# Digitalizador_RPi.net
KiCad netlist of a schematic drawn in Altium Designer
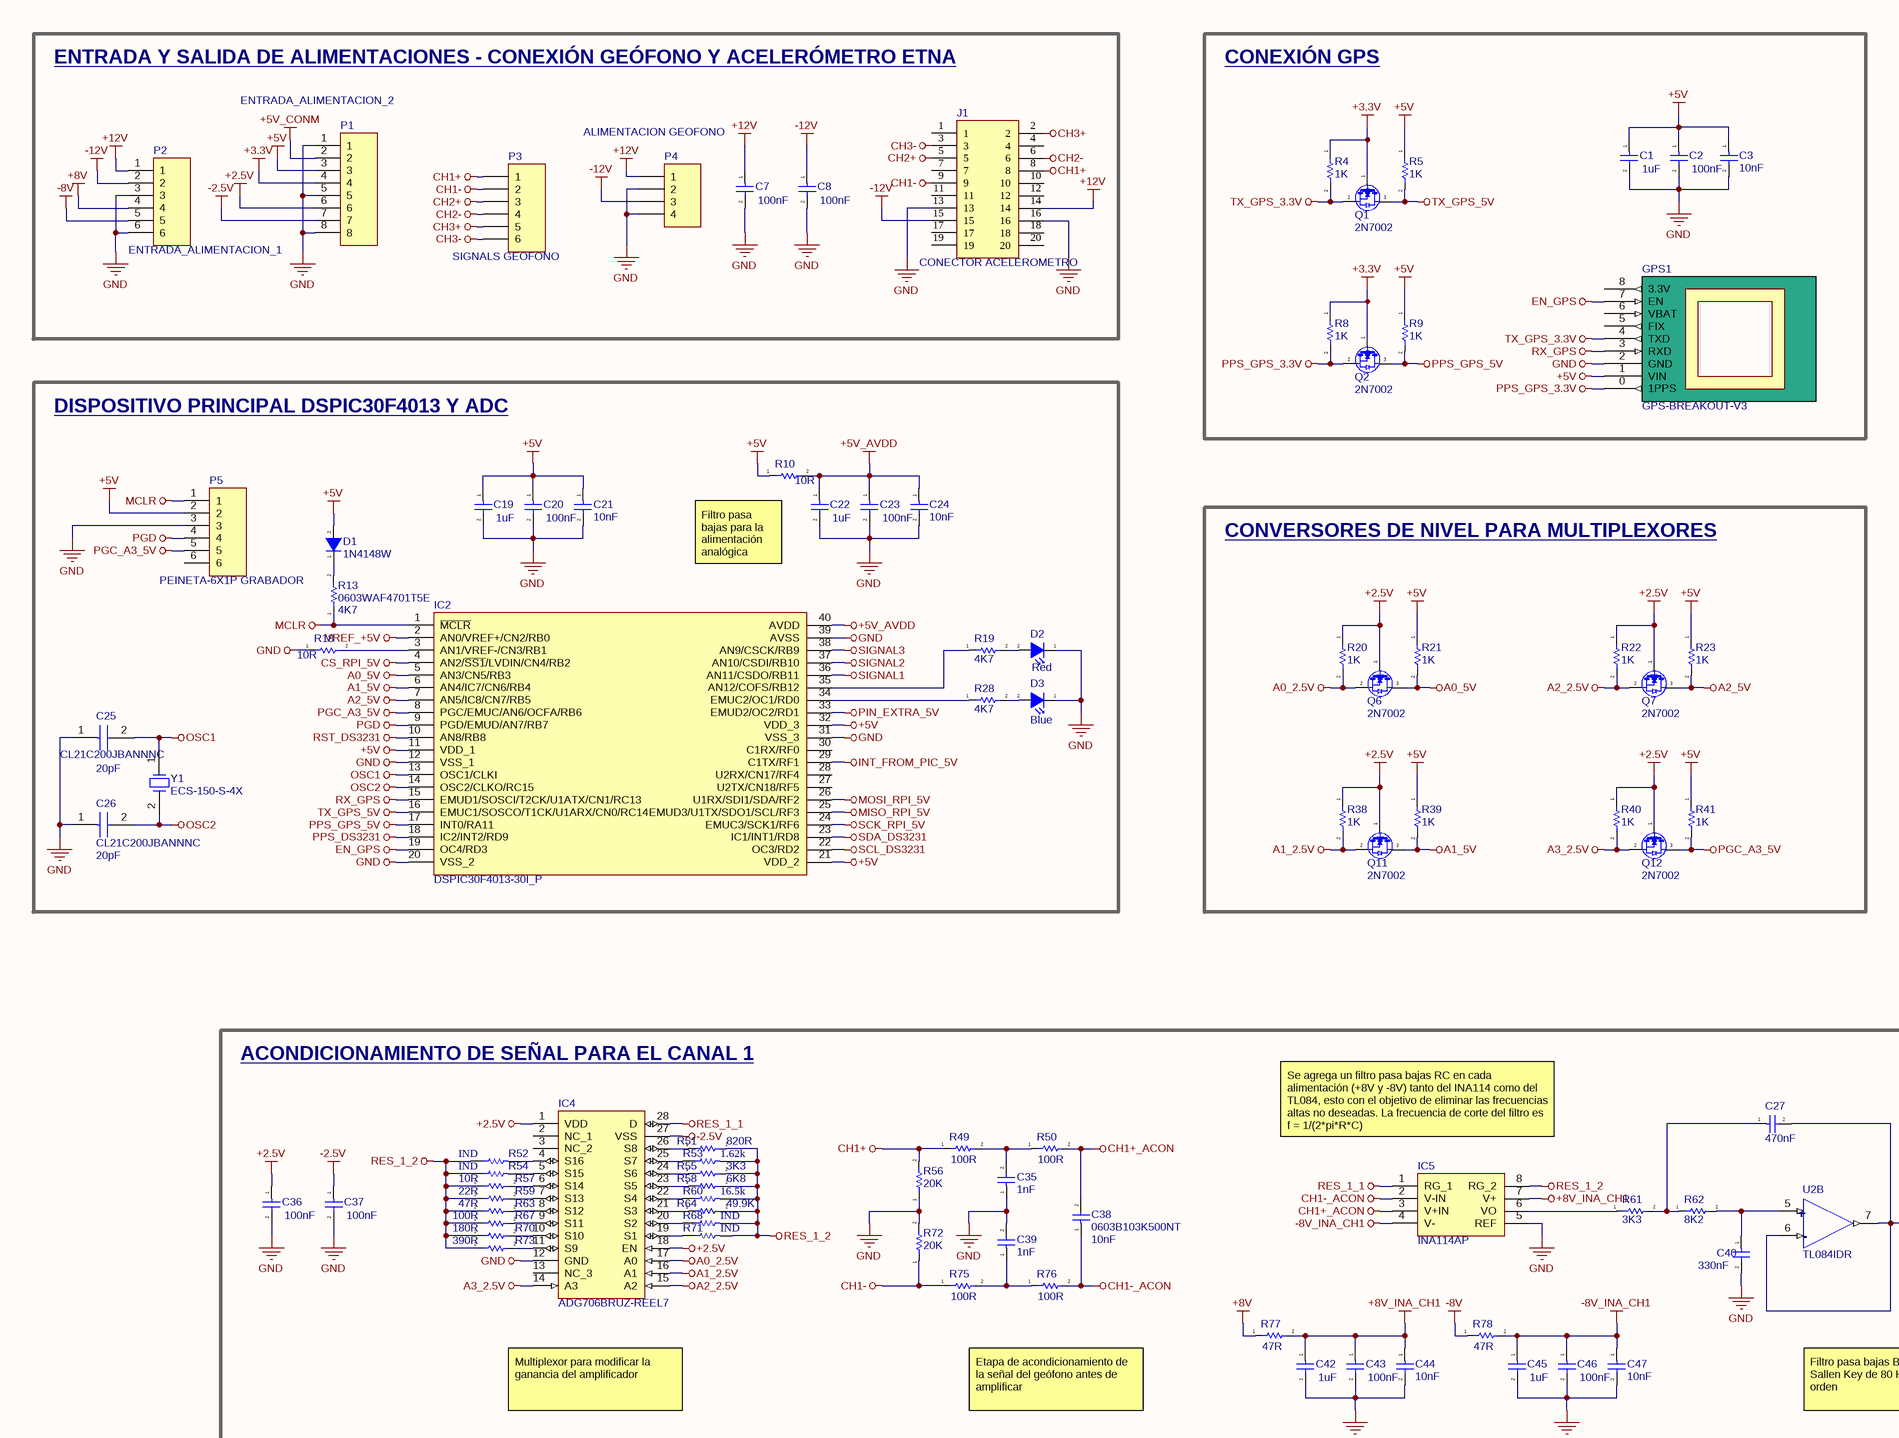
[diagram p0: Digitalizador_RPi.SchDoc, top left]
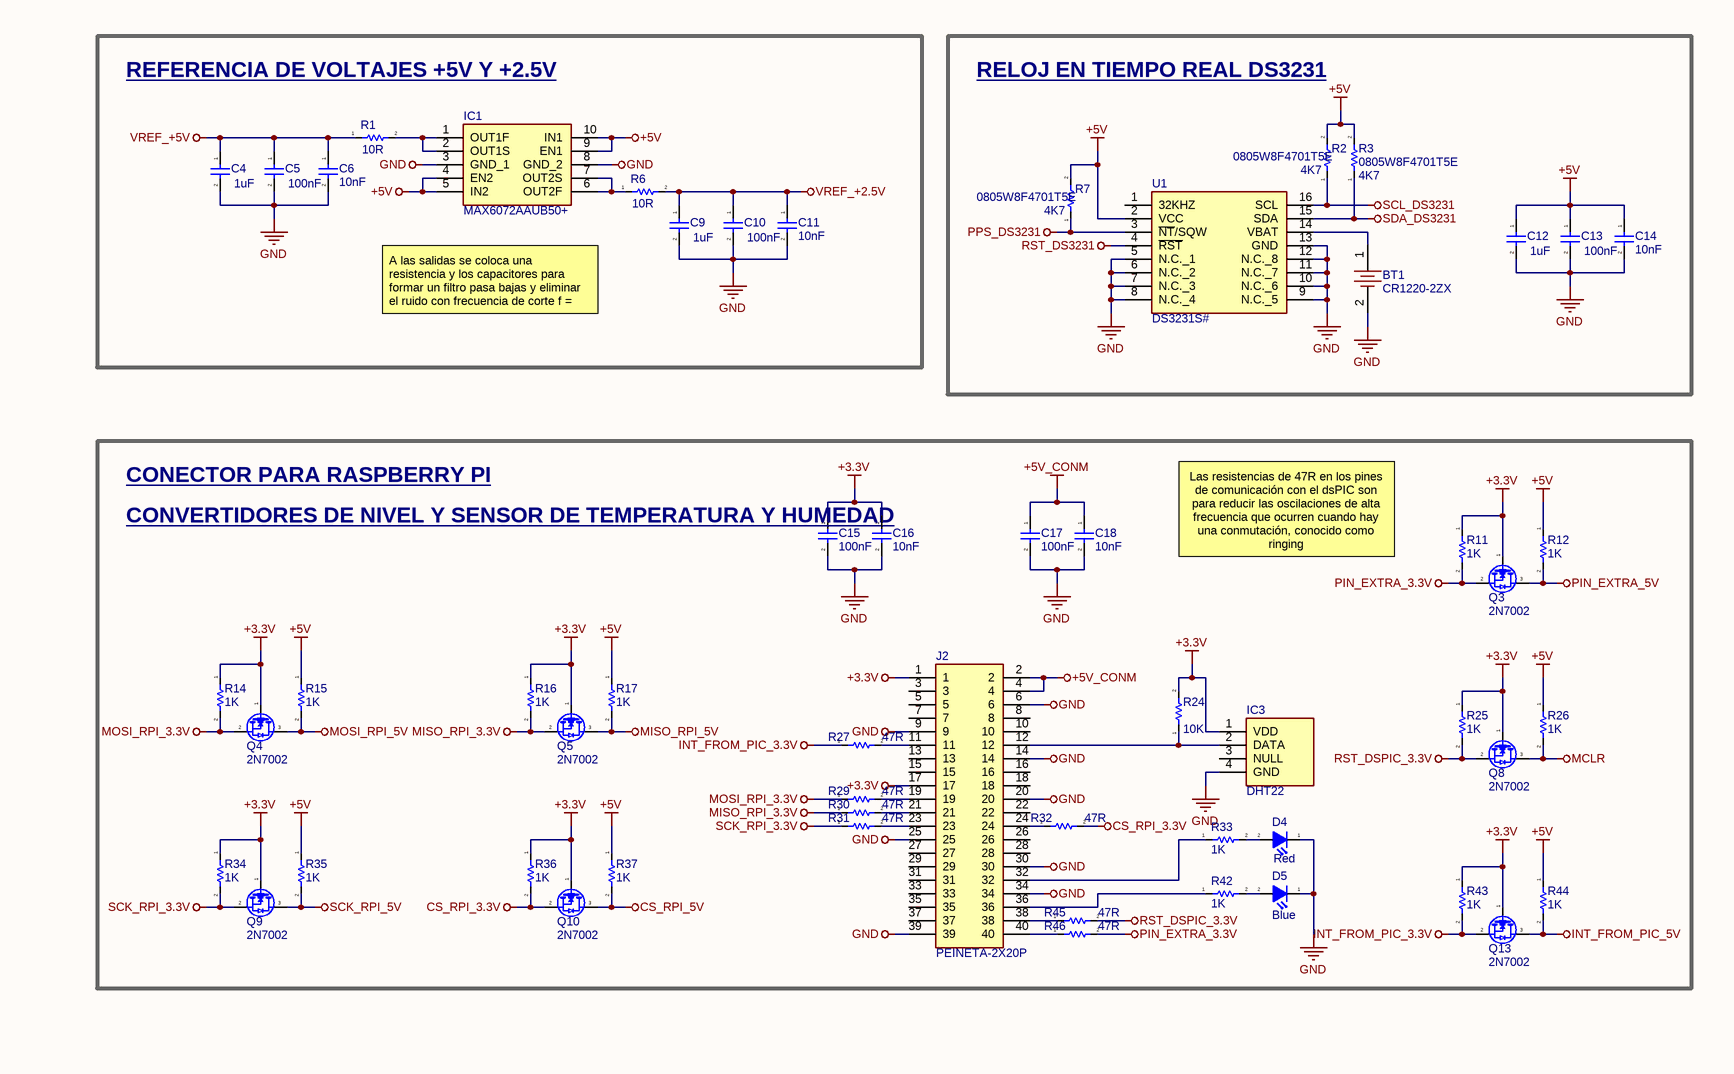
[diagram p1: Digitalizador_RPi.SchDoc, top right]
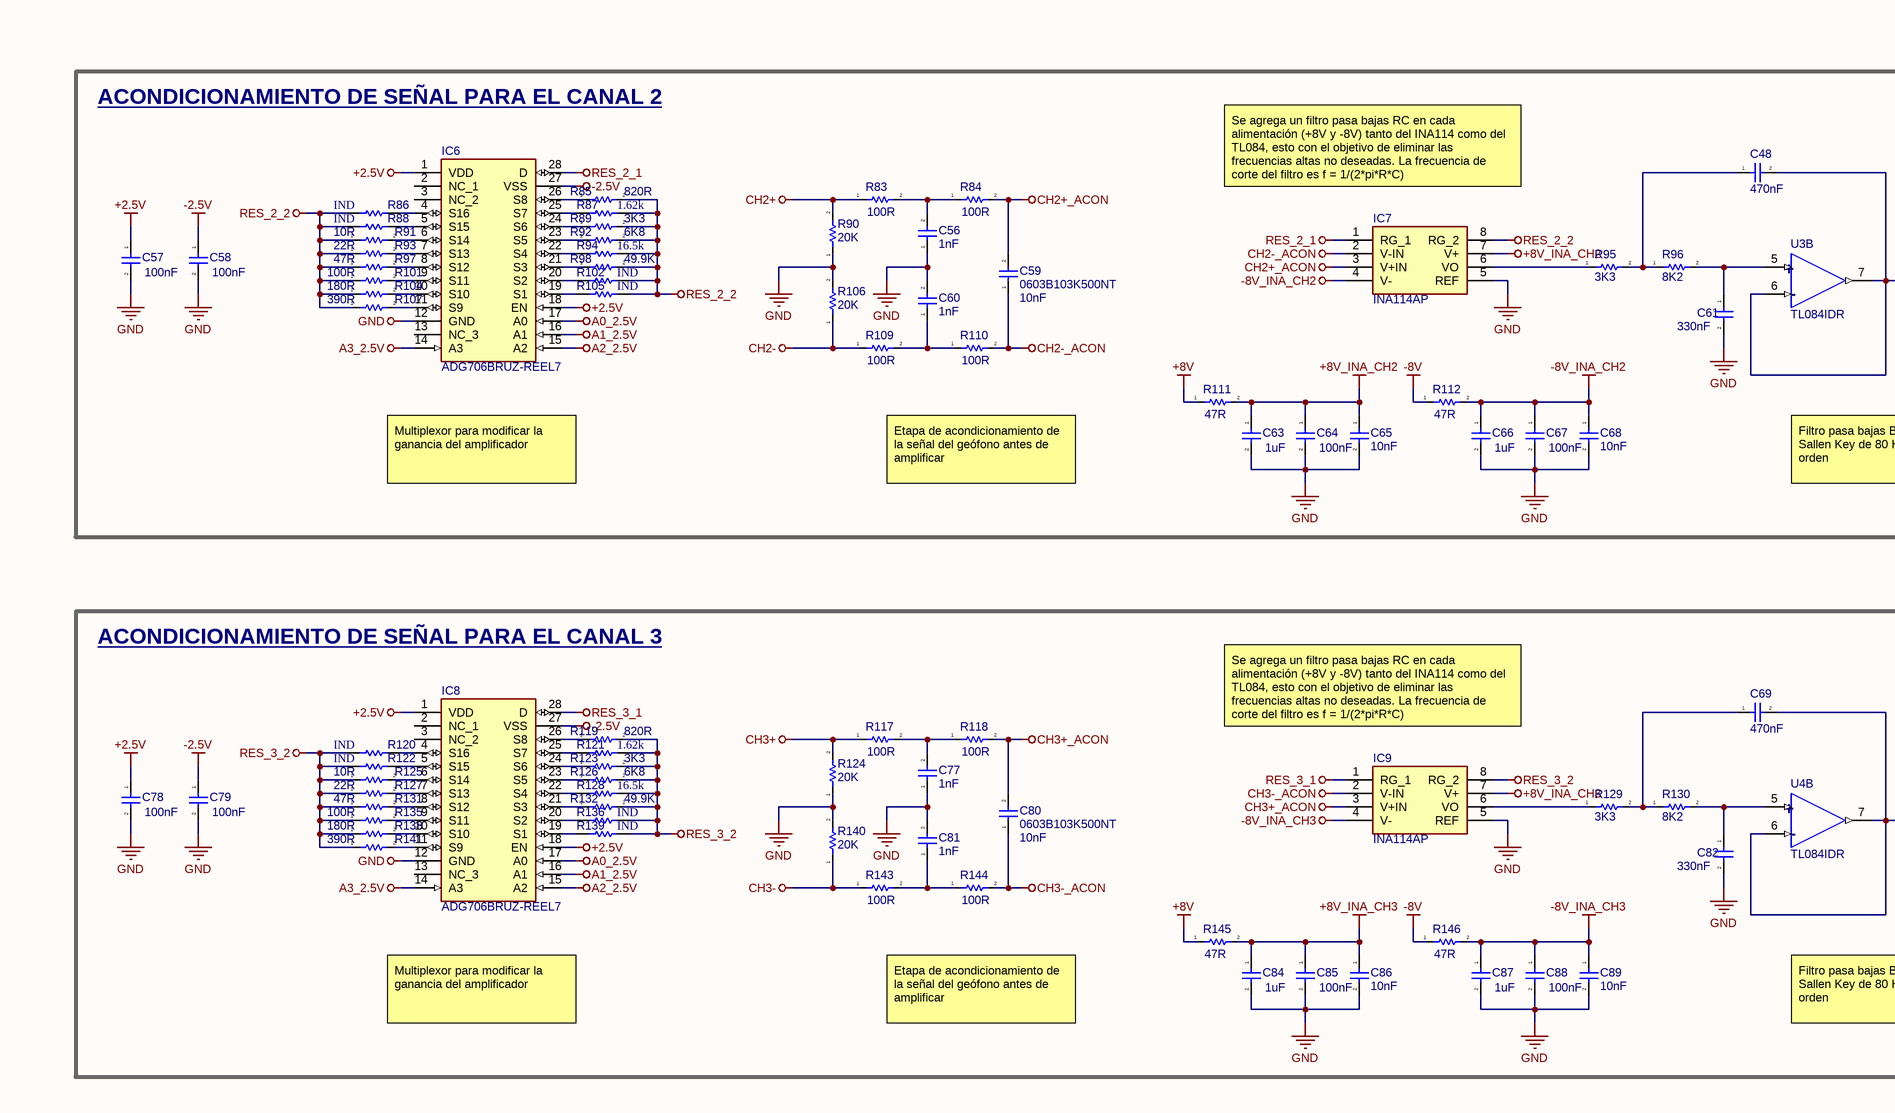
[diagram p2: Digitalizador_RPi.SchDoc, bottom left]
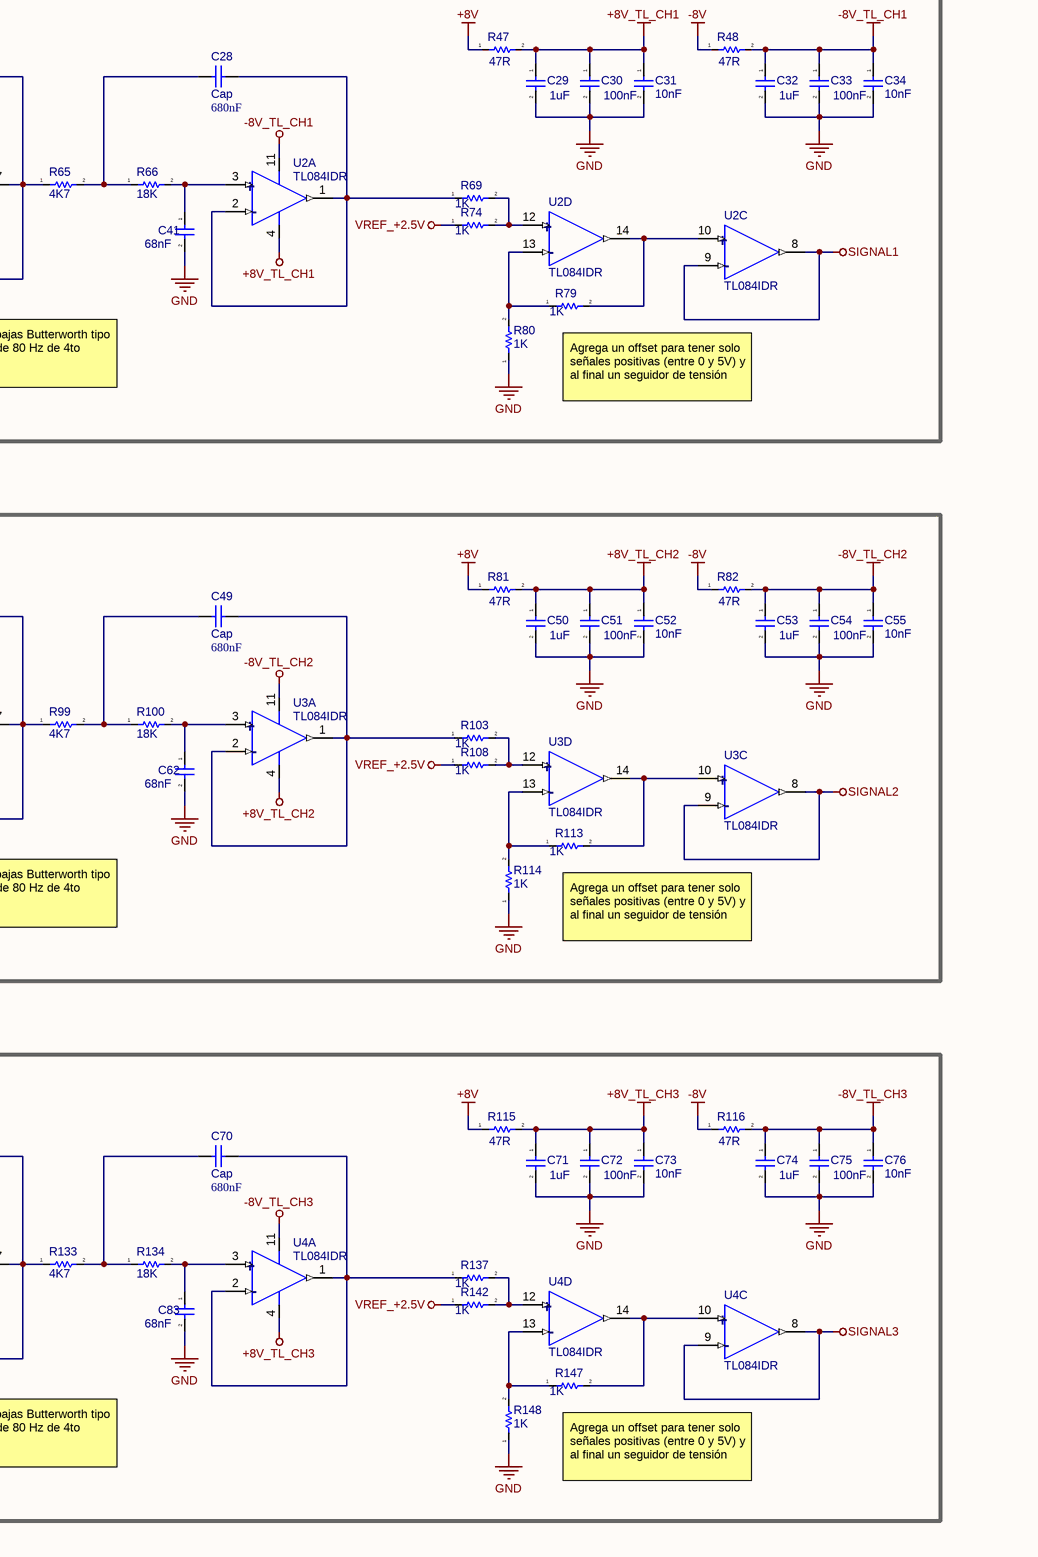
[diagram p3: Digitalizador_RPi.SchDoc, bottom right]

(export (version "E")
  (design (tool "Eeschema 10.0.6"))
  (components
    (comp (ref "BT1")
      (value "CR1220-2ZX")
      (footprint "CR12202ZX")
      (description "Battery Holder")
      (fields (field (name "JLCPCB PART #") "C969906"))
      (libsource (lib "AltiumLL") (part "CR1220-2ZX"))
    )
    (comp (ref "C1")
      (value "1uF")
      (footprint "CAPC1608X90N")
      (description "Capacitor")
      (fields
        (field (name "MANUFACTURER_PART_NUMBER") "CL10A105KB8NNNC")
        (field (name "MOUSER PART NUMBER") "187-CL10A105KB8NNNC")
      )
      (libsource (lib "AltiumLL") (part "CL10A105KB8NNNC"))
    )
    (comp (ref "C2")
      (value "100nF")
      (footprint "CAPC1608X90N")
      (description "Capacitor")
      (fields
        (field (name "MANUFACTURER_PART_NUMBER") "CC0603KRX7R9BB104")
        (field (name "MOUSER PART NUMBER") "603-CC603KRX7R9BB104")
      )
      (libsource (lib "AltiumLL") (part "CC0603KRX7R9BB104"))
    )
    (comp (ref "C3")
      (value "10nF")
      (footprint "CAPC1608X90N")
      (description "Capacitor")
      (fields
        (field (name "MANUFACTURER_PART_NUMBER") "0603B103K500NT")
        (field (name "JLCPCB PART #") "C57112")
      )
      (libsource (lib "AltiumLL") (part "0603B103K500NT"))
    )
    (comp (ref "C4")
      (value "1uF")
      (footprint "CAPC1608X90N")
      (description "Capacitor")
      (fields
        (field (name "MANUFACTURER_PART_NUMBER") "CL10A105KB8NNNC")
        (field (name "MOUSER PART NUMBER") "187-CL10A105KB8NNNC")
      )
      (libsource (lib "AltiumLL") (part "CL10A105KB8NNNC"))
    )
    (comp (ref "C5")
      (value "100nF")
      (footprint "CAPC1608X90N")
      (description "Capacitor")
      (fields
        (field (name "MANUFACTURER_PART_NUMBER") "CC0603KRX7R9BB104")
        (field (name "MOUSER PART NUMBER") "603-CC603KRX7R9BB104")
      )
      (libsource (lib "AltiumLL") (part "CC0603KRX7R9BB104"))
    )
    (comp (ref "C6")
      (value "10nF")
      (footprint "CAPC1608X90N")
      (description "Capacitor")
      (fields
        (field (name "MANUFACTURER_PART_NUMBER") "0603B103K500NT")
        (field (name "JLCPCB PART #") "C57112")
      )
      (libsource (lib "AltiumLL") (part "0603B103K500NT"))
    )
    (comp (ref "C7")
      (value "100nF")
      (footprint "CAPC1608X90N")
      (description "Capacitor")
      (fields
        (field (name "MANUFACTURER_PART_NUMBER") "CC0603KRX7R9BB104")
        (field (name "MOUSER PART NUMBER") "603-CC603KRX7R9BB104")
      )
      (libsource (lib "AltiumLL") (part "CC0603KRX7R9BB104"))
    )
    (comp (ref "C8")
      (value "100nF")
      (footprint "CAPC1608X90N")
      (description "Capacitor")
      (fields
        (field (name "MANUFACTURER_PART_NUMBER") "CC0603KRX7R9BB104")
        (field (name "MOUSER PART NUMBER") "603-CC603KRX7R9BB104")
      )
      (libsource (lib "AltiumLL") (part "CC0603KRX7R9BB104"))
    )
    (comp (ref "C9")
      (value "1uF")
      (footprint "CAPC1608X90N")
      (description "Capacitor")
      (fields
        (field (name "MANUFACTURER_PART_NUMBER") "CL10A105KB8NNNC")
        (field (name "MOUSER PART NUMBER") "187-CL10A105KB8NNNC")
      )
      (libsource (lib "AltiumLL") (part "CL10A105KB8NNNC"))
    )
    (comp (ref "C10")
      (value "100nF")
      (footprint "CAPC1608X90N")
      (description "Capacitor")
      (fields
        (field (name "MANUFACTURER_PART_NUMBER") "CC0603KRX7R9BB104")
        (field (name "MOUSER PART NUMBER") "603-CC603KRX7R9BB104")
      )
      (libsource (lib "AltiumLL") (part "CC0603KRX7R9BB104"))
    )
    (comp (ref "C11")
      (value "10nF")
      (footprint "CAPC1608X90N")
      (description "Capacitor")
      (fields
        (field (name "MANUFACTURER_PART_NUMBER") "0603B103K500NT")
        (field (name "JLCPCB PART #") "C57112")
      )
      (libsource (lib "AltiumLL") (part "0603B103K500NT"))
    )
    (comp (ref "C12")
      (value "1uF")
      (footprint "CAPC1608X90N")
      (description "Capacitor")
      (fields
        (field (name "MANUFACTURER_PART_NUMBER") "CL10A105KB8NNNC")
        (field (name "MOUSER PART NUMBER") "187-CL10A105KB8NNNC")
      )
      (libsource (lib "AltiumLL") (part "CL10A105KB8NNNC"))
    )
    (comp (ref "C13")
      (value "100nF")
      (footprint "CAPC1608X90N")
      (description "Capacitor")
      (fields
        (field (name "MANUFACTURER_PART_NUMBER") "CC0603KRX7R9BB104")
        (field (name "MOUSER PART NUMBER") "603-CC603KRX7R9BB104")
      )
      (libsource (lib "AltiumLL") (part "CC0603KRX7R9BB104"))
    )
    (comp (ref "C14")
      (value "10nF")
      (footprint "CAPC1608X90N")
      (description "Capacitor")
      (fields
        (field (name "MANUFACTURER_PART_NUMBER") "0603B103K500NT")
        (field (name "JLCPCB PART #") "C57112")
      )
      (libsource (lib "AltiumLL") (part "0603B103K500NT"))
    )
    (comp (ref "C15")
      (value "100nF")
      (footprint "CAPC1608X90N")
      (description "Capacitor")
      (fields
        (field (name "MANUFACTURER_PART_NUMBER") "CC0603KRX7R9BB104")
        (field (name "MOUSER PART NUMBER") "603-CC603KRX7R9BB104")
      )
      (libsource (lib "AltiumLL") (part "CC0603KRX7R9BB104"))
    )
    (comp (ref "C16")
      (value "10nF")
      (footprint "CAPC1608X90N")
      (description "Capacitor")
      (fields
        (field (name "MANUFACTURER_PART_NUMBER") "0603B103K500NT")
        (field (name "JLCPCB PART #") "C57112")
      )
      (libsource (lib "AltiumLL") (part "0603B103K500NT"))
    )
    (comp (ref "C17")
      (value "100nF")
      (footprint "CAPC1608X90N")
      (description "Capacitor")
      (fields
        (field (name "MANUFACTURER_PART_NUMBER") "CC0603KRX7R9BB104")
        (field (name "MOUSER PART NUMBER") "603-CC603KRX7R9BB104")
      )
      (libsource (lib "AltiumLL") (part "CC0603KRX7R9BB104"))
    )
    (comp (ref "C18")
      (value "10nF")
      (footprint "CAPC1608X90N")
      (description "Capacitor")
      (fields
        (field (name "MANUFACTURER_PART_NUMBER") "0603B103K500NT")
        (field (name "JLCPCB PART #") "C57112")
      )
      (libsource (lib "AltiumLL") (part "0603B103K500NT"))
    )
    (comp (ref "C19")
      (value "1uF")
      (footprint "CAPC1608X90N")
      (description "Capacitor")
      (fields
        (field (name "MANUFACTURER_PART_NUMBER") "CL10A105KB8NNNC")
        (field (name "MOUSER PART NUMBER") "187-CL10A105KB8NNNC")
      )
      (libsource (lib "AltiumLL") (part "CL10A105KB8NNNC"))
    )
    (comp (ref "C20")
      (value "100nF")
      (footprint "CAPC1608X90N")
      (description "Capacitor")
      (fields
        (field (name "MANUFACTURER_PART_NUMBER") "CC0603KRX7R9BB104")
        (field (name "MOUSER PART NUMBER") "603-CC603KRX7R9BB104")
      )
      (libsource (lib "AltiumLL") (part "CC0603KRX7R9BB104"))
    )
    (comp (ref "C21")
      (value "10nF")
      (footprint "CAPC1608X90N")
      (description "Capacitor")
      (fields
        (field (name "MANUFACTURER_PART_NUMBER") "0603B103K500NT")
        (field (name "JLCPCB PART #") "C57112")
      )
      (libsource (lib "AltiumLL") (part "0603B103K500NT"))
    )
    (comp (ref "C22")
      (value "1uF")
      (footprint "CAPC1608X90N")
      (description "Capacitor")
      (fields
        (field (name "MANUFACTURER_PART_NUMBER") "CL10A105KB8NNNC")
        (field (name "MOUSER PART NUMBER") "187-CL10A105KB8NNNC")
      )
      (libsource (lib "AltiumLL") (part "CL10A105KB8NNNC"))
    )
    (comp (ref "C23")
      (value "100nF")
      (footprint "CAPC1608X90N")
      (description "Capacitor")
      (fields
        (field (name "MANUFACTURER_PART_NUMBER") "CC0603KRX7R9BB104")
        (field (name "MOUSER PART NUMBER") "603-CC603KRX7R9BB104")
      )
      (libsource (lib "AltiumLL") (part "CC0603KRX7R9BB104"))
    )
    (comp (ref "C24")
      (value "10nF")
      (footprint "CAPC1608X90N")
      (description "Capacitor")
      (fields
        (field (name "MANUFACTURER_PART_NUMBER") "0603B103K500NT")
        (field (name "JLCPCB PART #") "C57112")
      )
      (libsource (lib "AltiumLL") (part "0603B103K500NT"))
    )
    (comp (ref "C25")
      (value "CL21C200JBANNNC")
      (footprint "CAPC2012X75N")
      (description "Capacitor")
      (fields (field (name "JLCPCB PART #") "C1798") (field (name "ALTIUM_VALUE") "20pF"))
      (libsource (lib "AltiumLL") (part "CL21C200JBANNNC"))
    )
    (comp (ref "C26")
      (value "CL21C200JBANNNC")
      (footprint "CAPC2012X75N")
      (description "Capacitor")
      (fields (field (name "JLCPCB PART #") "C1798") (field (name "ALTIUM_VALUE") "20pF"))
      (libsource (lib "AltiumLL") (part "CL21C200JBANNNC"))
    )
    (comp (ref "C27")
      (value "470nF")
      (footprint "CAPC1608X90N")
      (description "Capacitor")
      (fields
        (field (name "MANUFACTURER_PART_NUMBER") "CL10B474KA8NNNC")
        (field (name "JLCPCB PART #") "C1623")
      )
      (libsource (lib "AltiumLL") (part "CL10B474KA8NNNC"))
    )
    (comp (ref "C28")
      (value "Cap")
      (footprint "CAPC1608X90N")
      (description "Capacitor")
      (fields (field (name "ALTIUM_VALUE") "680nF") (field (name "PUBLISHER") "Altium Limited"))
      (libsource (lib "Miscellaneous Devices") (part "Cap"))
    )
    (comp (ref "C29")
      (value "1uF")
      (footprint "CAPC1608X90N")
      (description "Capacitor")
      (fields
        (field (name "MANUFACTURER_PART_NUMBER") "CL10A105KB8NNNC")
        (field (name "MOUSER PART NUMBER") "187-CL10A105KB8NNNC")
      )
      (libsource (lib "AltiumLL") (part "CL10A105KB8NNNC"))
    )
    (comp (ref "C30")
      (value "100nF")
      (footprint "CAPC1608X90N")
      (description "Capacitor")
      (fields
        (field (name "MANUFACTURER_PART_NUMBER") "CC0603KRX7R9BB104")
        (field (name "MOUSER PART NUMBER") "603-CC603KRX7R9BB104")
      )
      (libsource (lib "AltiumLL") (part "CC0603KRX7R9BB104"))
    )
    (comp (ref "C31")
      (value "10nF")
      (footprint "CAPC1608X90N")
      (description "Capacitor")
      (fields
        (field (name "MANUFACTURER_PART_NUMBER") "0603B103K500NT")
        (field (name "JLCPCB PART #") "C57112")
      )
      (libsource (lib "AltiumLL") (part "0603B103K500NT"))
    )
    (comp (ref "C32")
      (value "1uF")
      (footprint "CAPC1608X90N")
      (description "Capacitor")
      (fields
        (field (name "MANUFACTURER_PART_NUMBER") "CL10A105KB8NNNC")
        (field (name "MOUSER PART NUMBER") "187-CL10A105KB8NNNC")
      )
      (libsource (lib "AltiumLL") (part "CL10A105KB8NNNC"))
    )
    (comp (ref "C33")
      (value "100nF")
      (footprint "CAPC1608X90N")
      (description "Capacitor")
      (fields
        (field (name "MANUFACTURER_PART_NUMBER") "CC0603KRX7R9BB104")
        (field (name "MOUSER PART NUMBER") "603-CC603KRX7R9BB104")
      )
      (libsource (lib "AltiumLL") (part "CC0603KRX7R9BB104"))
    )
    (comp (ref "C34")
      (value "10nF")
      (footprint "CAPC1608X90N")
      (description "Capacitor")
      (fields
        (field (name "MANUFACTURER_PART_NUMBER") "0603B103K500NT")
        (field (name "JLCPCB PART #") "C57112")
      )
      (libsource (lib "AltiumLL") (part "0603B103K500NT"))
    )
    (comp (ref "C35")
      (value "1nF")
      (footprint "CAPC1608X90N")
      (description "Capacitor")
      (fields
        (field (name "MANUFACTURER_PART_NUMBER") "CL10B102KB8NNNC")
        (field (name "MOUSER PART NUMBER") "187-CL10B102KB8NNNC")
      )
      (libsource (lib "AltiumLL") (part "CL10B102KB8NNNC"))
    )
    (comp (ref "C36")
      (value "100nF")
      (footprint "CAPC1608X90N")
      (description "Capacitor")
      (fields
        (field (name "MANUFACTURER_PART_NUMBER") "CC0603KRX7R9BB104")
        (field (name "MOUSER PART NUMBER") "603-CC603KRX7R9BB104")
      )
      (libsource (lib "AltiumLL") (part "CC0603KRX7R9BB104"))
    )
    (comp (ref "C37")
      (value "100nF")
      (footprint "CAPC1608X90N")
      (description "Capacitor")
      (fields
        (field (name "MANUFACTURER_PART_NUMBER") "CC0603KRX7R9BB104")
        (field (name "MOUSER PART NUMBER") "603-CC603KRX7R9BB104")
      )
      (libsource (lib "AltiumLL") (part "CC0603KRX7R9BB104"))
    )
    (comp (ref "C38")
      (value "0603B103K500NT")
      (footprint "CAPC1608X90N")
      (description "Capacitor")
      (fields (field (name "JLCPCB PART #") "C57112") (field (name "ALTIUM_VALUE") "10nF"))
      (libsource (lib "AltiumLL") (part "0603B103K500NT"))
    )
    (comp (ref "C39")
      (value "1nF")
      (footprint "CAPC1608X90N")
      (description "Capacitor")
      (fields
        (field (name "MANUFACTURER_PART_NUMBER") "CL10B102KB8NNNC")
        (field (name "MOUSER PART NUMBER") "187-CL10B102KB8NNNC")
      )
      (libsource (lib "AltiumLL") (part "CL10B102KB8NNNC"))
    )
    (comp (ref "C40")
      (value "330nF")
      (footprint "CAPC1608X90N")
      (description "Capacitor")
      (fields
        (field (name "MANUFACTURER_PART_NUMBER") "0603B334K250NT")
        (field (name "JLCPCB PART #") "C1615")
      )
      (libsource (lib "AltiumLL") (part "0603B334K250NT"))
    )
    (comp (ref "C41")
      (value "68nF")
      (footprint "CAPC1608X90N")
      (description "Capacitor")
      (fields
        (field (name "MANUFACTURER_PART_NUMBER") "CL10B683KB8NNNC")
        (field (name "JLCPCB PART #") "C31658")
      )
      (libsource (lib "AltiumLL") (part "CL10B683KB8NNNC"))
    )
    (comp (ref "C42")
      (value "1uF")
      (footprint "CAPC1608X90N")
      (description "Capacitor")
      (fields
        (field (name "MANUFACTURER_PART_NUMBER") "CL10A105KB8NNNC")
        (field (name "MOUSER PART NUMBER") "187-CL10A105KB8NNNC")
      )
      (libsource (lib "AltiumLL") (part "CL10A105KB8NNNC"))
    )
    (comp (ref "C43")
      (value "100nF")
      (footprint "CAPC1608X90N")
      (description "Capacitor")
      (fields
        (field (name "MANUFACTURER_PART_NUMBER") "CC0603KRX7R9BB104")
        (field (name "MOUSER PART NUMBER") "603-CC603KRX7R9BB104")
      )
      (libsource (lib "AltiumLL") (part "CC0603KRX7R9BB104"))
    )
    (comp (ref "C44")
      (value "10nF")
      (footprint "CAPC1608X90N")
      (description "Capacitor")
      (fields
        (field (name "MANUFACTURER_PART_NUMBER") "0603B103K500NT")
        (field (name "JLCPCB PART #") "C57112")
      )
      (libsource (lib "AltiumLL") (part "0603B103K500NT"))
    )
    (comp (ref "C45")
      (value "1uF")
      (footprint "CAPC1608X90N")
      (description "Capacitor")
      (fields
        (field (name "MANUFACTURER_PART_NUMBER") "CL10A105KB8NNNC")
        (field (name "MOUSER PART NUMBER") "187-CL10A105KB8NNNC")
      )
      (libsource (lib "AltiumLL") (part "CL10A105KB8NNNC"))
    )
    (comp (ref "C46")
      (value "100nF")
      (footprint "CAPC1608X90N")
      (description "Capacitor")
      (fields
        (field (name "MANUFACTURER_PART_NUMBER") "CC0603KRX7R9BB104")
        (field (name "MOUSER PART NUMBER") "603-CC603KRX7R9BB104")
      )
      (libsource (lib "AltiumLL") (part "CC0603KRX7R9BB104"))
    )
    (comp (ref "C47")
      (value "10nF")
      (footprint "CAPC1608X90N")
      (description "Capacitor")
      (fields
        (field (name "MANUFACTURER_PART_NUMBER") "0603B103K500NT")
        (field (name "JLCPCB PART #") "C57112")
      )
      (libsource (lib "AltiumLL") (part "0603B103K500NT"))
    )
    (comp (ref "C48")
      (value "470nF")
      (footprint "CAPC1608X90N")
      (description "Capacitor")
      (fields
        (field (name "MANUFACTURER_PART_NUMBER") "CL10B474KA8NNNC")
        (field (name "JLCPCB PART #") "C1623")
      )
      (libsource (lib "AltiumLL") (part "CL10B474KA8NNNC"))
    )
    (comp (ref "C49")
      (value "Cap")
      (footprint "CAPC1608X90N")
      (description "Capacitor")
      (fields (field (name "ALTIUM_VALUE") "680nF") (field (name "PUBLISHER") "Altium Limited"))
      (libsource (lib "Miscellaneous Devices") (part "Cap"))
    )
    (comp (ref "C50")
      (value "1uF")
      (footprint "CAPC1608X90N")
      (description "Capacitor")
      (fields
        (field (name "MANUFACTURER_PART_NUMBER") "CL10A105KB8NNNC")
        (field (name "MOUSER PART NUMBER") "187-CL10A105KB8NNNC")
      )
      (libsource (lib "AltiumLL") (part "CL10A105KB8NNNC"))
    )
    (comp (ref "C51")
      (value "100nF")
      (footprint "CAPC1608X90N")
      (description "Capacitor")
      (fields
        (field (name "MANUFACTURER_PART_NUMBER") "CC0603KRX7R9BB104")
        (field (name "MOUSER PART NUMBER") "603-CC603KRX7R9BB104")
      )
      (libsource (lib "AltiumLL") (part "CC0603KRX7R9BB104"))
    )
    (comp (ref "C52")
      (value "10nF")
      (footprint "CAPC1608X90N")
      (description "Capacitor")
      (fields
        (field (name "MANUFACTURER_PART_NUMBER") "0603B103K500NT")
        (field (name "JLCPCB PART #") "C57112")
      )
      (libsource (lib "AltiumLL") (part "0603B103K500NT"))
    )
    (comp (ref "C53")
      (value "1uF")
      (footprint "CAPC1608X90N")
      (description "Capacitor")
      (fields
        (field (name "MANUFACTURER_PART_NUMBER") "CL10A105KB8NNNC")
        (field (name "MOUSER PART NUMBER") "187-CL10A105KB8NNNC")
      )
      (libsource (lib "AltiumLL") (part "CL10A105KB8NNNC"))
    )
    (comp (ref "C54")
      (value "100nF")
      (footprint "CAPC1608X90N")
      (description "Capacitor")
      (fields
        (field (name "MANUFACTURER_PART_NUMBER") "CC0603KRX7R9BB104")
        (field (name "MOUSER PART NUMBER") "603-CC603KRX7R9BB104")
      )
      (libsource (lib "AltiumLL") (part "CC0603KRX7R9BB104"))
    )
    (comp (ref "C55")
      (value "10nF")
      (footprint "CAPC1608X90N")
      (description "Capacitor")
      (fields
        (field (name "MANUFACTURER_PART_NUMBER") "0603B103K500NT")
        (field (name "JLCPCB PART #") "C57112")
      )
      (libsource (lib "AltiumLL") (part "0603B103K500NT"))
    )
    (comp (ref "C56")
      (value "1nF")
      (footprint "CAPC1608X90N")
      (description "Capacitor")
      (fields
        (field (name "MANUFACTURER_PART_NUMBER") "CL10B102KB8NNNC")
        (field (name "MOUSER PART NUMBER") "187-CL10B102KB8NNNC")
      )
      (libsource (lib "AltiumLL") (part "CL10B102KB8NNNC"))
    )
    (comp (ref "C57")
      (value "100nF")
      (footprint "CAPC1608X90N")
      (description "Capacitor")
      (fields
        (field (name "MANUFACTURER_PART_NUMBER") "CC0603KRX7R9BB104")
        (field (name "MOUSER PART NUMBER") "603-CC603KRX7R9BB104")
      )
      (libsource (lib "AltiumLL") (part "CC0603KRX7R9BB104"))
    )
    (comp (ref "C58")
      (value "100nF")
      (footprint "CAPC1608X90N")
      (description "Capacitor")
      (fields
        (field (name "MANUFACTURER_PART_NUMBER") "CC0603KRX7R9BB104")
        (field (name "MOUSER PART NUMBER") "603-CC603KRX7R9BB104")
      )
      (libsource (lib "AltiumLL") (part "CC0603KRX7R9BB104"))
    )
    (comp (ref "C59")
      (value "0603B103K500NT")
      (footprint "CAPC1608X90N")
      (description "Capacitor")
      (fields (field (name "JLCPCB PART #") "C57112") (field (name "ALTIUM_VALUE") "10nF"))
      (libsource (lib "AltiumLL") (part "0603B103K500NT"))
    )
    (comp (ref "C60")
      (value "1nF")
      (footprint "CAPC1608X90N")
      (description "Capacitor")
      (fields
        (field (name "MANUFACTURER_PART_NUMBER") "CL10B102KB8NNNC")
        (field (name "MOUSER PART NUMBER") "187-CL10B102KB8NNNC")
      )
      (libsource (lib "AltiumLL") (part "CL10B102KB8NNNC"))
    )
    (comp (ref "C61")
      (value "330nF")
      (footprint "CAPC1608X90N")
      (description "Capacitor")
      (fields
        (field (name "MANUFACTURER_PART_NUMBER") "0603B334K250NT")
        (field (name "JLCPCB PART #") "C1615")
      )
      (libsource (lib "AltiumLL") (part "0603B334K250NT"))
    )
    (comp (ref "C62")
      (value "68nF")
      (footprint "CAPC1608X90N")
      (description "Capacitor")
      (fields
        (field (name "MANUFACTURER_PART_NUMBER") "CL10B683KB8NNNC")
        (field (name "JLCPCB PART #") "C31658")
      )
      (libsource (lib "AltiumLL") (part "CL10B683KB8NNNC"))
    )
    (comp (ref "C63")
      (value "1uF")
      (footprint "CAPC1608X90N")
      (description "Capacitor")
      (fields
        (field (name "MANUFACTURER_PART_NUMBER") "CL10A105KB8NNNC")
        (field (name "MOUSER PART NUMBER") "187-CL10A105KB8NNNC")
      )
      (libsource (lib "AltiumLL") (part "CL10A105KB8NNNC"))
    )
    (comp (ref "C64")
      (value "100nF")
      (footprint "CAPC1608X90N")
      (description "Capacitor")
      (fields
        (field (name "MANUFACTURER_PART_NUMBER") "CC0603KRX7R9BB104")
        (field (name "MOUSER PART NUMBER") "603-CC603KRX7R9BB104")
      )
      (libsource (lib "AltiumLL") (part "CC0603KRX7R9BB104"))
    )
    (comp (ref "C65")
      (value "10nF")
      (footprint "CAPC1608X90N")
      (description "Capacitor")
      (fields
        (field (name "MANUFACTURER_PART_NUMBER") "0603B103K500NT")
        (field (name "JLCPCB PART #") "C57112")
      )
      (libsource (lib "AltiumLL") (part "0603B103K500NT"))
    )
    (comp (ref "C66")
      (value "1uF")
      (footprint "CAPC1608X90N")
      (description "Capacitor")
      (fields
        (field (name "MANUFACTURER_PART_NUMBER") "CL10A105KB8NNNC")
        (field (name "MOUSER PART NUMBER") "187-CL10A105KB8NNNC")
      )
      (libsource (lib "AltiumLL") (part "CL10A105KB8NNNC"))
    )
    (comp (ref "C67")
      (value "100nF")
      (footprint "CAPC1608X90N")
      (description "Capacitor")
      (fields
        (field (name "MANUFACTURER_PART_NUMBER") "CC0603KRX7R9BB104")
        (field (name "MOUSER PART NUMBER") "603-CC603KRX7R9BB104")
      )
      (libsource (lib "AltiumLL") (part "CC0603KRX7R9BB104"))
    )
    (comp (ref "C68")
      (value "10nF")
      (footprint "CAPC1608X90N")
      (description "Capacitor")
      (fields
        (field (name "MANUFACTURER_PART_NUMBER") "0603B103K500NT")
        (field (name "JLCPCB PART #") "C57112")
      )
      (libsource (lib "AltiumLL") (part "0603B103K500NT"))
    )
    (comp (ref "C69")
      (value "470nF")
      (footprint "CAPC1608X90N")
      (description "Capacitor")
      (fields
        (field (name "MANUFACTURER_PART_NUMBER") "CL10B474KA8NNNC")
        (field (name "JLCPCB PART #") "C1623")
      )
      (libsource (lib "AltiumLL") (part "CL10B474KA8NNNC"))
    )
    (comp (ref "C70")
      (value "Cap")
      (footprint "CAPC1608X90N")
      (description "Capacitor")
      (fields (field (name "ALTIUM_VALUE") "680nF") (field (name "PUBLISHER") "Altium Limited"))
      (libsource (lib "Miscellaneous Devices") (part "Cap"))
    )
    (comp (ref "C71")
      (value "1uF")
      (footprint "CAPC1608X90N")
      (description "Capacitor")
      (fields
        (field (name "MANUFACTURER_PART_NUMBER") "CL10A105KB8NNNC")
        (field (name "MOUSER PART NUMBER") "187-CL10A105KB8NNNC")
      )
      (libsource (lib "AltiumLL") (part "CL10A105KB8NNNC"))
    )
    (comp (ref "C72")
      (value "100nF")
      (footprint "CAPC1608X90N")
      (description "Capacitor")
      (fields
        (field (name "MANUFACTURER_PART_NUMBER") "CC0603KRX7R9BB104")
        (field (name "MOUSER PART NUMBER") "603-CC603KRX7R9BB104")
      )
      (libsource (lib "AltiumLL") (part "CC0603KRX7R9BB104"))
    )
    (comp (ref "C73")
      (value "10nF")
      (footprint "CAPC1608X90N")
      (description "Capacitor")
      (fields
        (field (name "MANUFACTURER_PART_NUMBER") "0603B103K500NT")
        (field (name "JLCPCB PART #") "C57112")
      )
      (libsource (lib "AltiumLL") (part "0603B103K500NT"))
    )
    (comp (ref "C74")
      (value "1uF")
      (footprint "CAPC1608X90N")
      (description "Capacitor")
      (fields
        (field (name "MANUFACTURER_PART_NUMBER") "CL10A105KB8NNNC")
        (field (name "MOUSER PART NUMBER") "187-CL10A105KB8NNNC")
      )
      (libsource (lib "AltiumLL") (part "CL10A105KB8NNNC"))
    )
    (comp (ref "C75")
      (value "100nF")
      (footprint "CAPC1608X90N")
      (description "Capacitor")
      (fields
        (field (name "MANUFACTURER_PART_NUMBER") "CC0603KRX7R9BB104")
        (field (name "MOUSER PART NUMBER") "603-CC603KRX7R9BB104")
      )
      (libsource (lib "AltiumLL") (part "CC0603KRX7R9BB104"))
    )
    (comp (ref "C76")
      (value "10nF")
      (footprint "CAPC1608X90N")
      (description "Capacitor")
      (fields
        (field (name "MANUFACTURER_PART_NUMBER") "0603B103K500NT")
        (field (name "JLCPCB PART #") "C57112")
      )
      (libsource (lib "AltiumLL") (part "0603B103K500NT"))
    )
    (comp (ref "C77")
      (value "1nF")
      (footprint "CAPC1608X90N")
      (description "Capacitor")
      (fields
        (field (name "MANUFACTURER_PART_NUMBER") "CL10B102KB8NNNC")
        (field (name "MOUSER PART NUMBER") "187-CL10B102KB8NNNC")
      )
      (libsource (lib "AltiumLL") (part "CL10B102KB8NNNC"))
    )
    (comp (ref "C78")
      (value "100nF")
      (footprint "CAPC1608X90N")
      (description "Capacitor")
      (fields
        (field (name "MANUFACTURER_PART_NUMBER") "CC0603KRX7R9BB104")
        (field (name "MOUSER PART NUMBER") "603-CC603KRX7R9BB104")
      )
      (libsource (lib "AltiumLL") (part "CC0603KRX7R9BB104"))
    )
    (comp (ref "C79")
      (value "100nF")
      (footprint "CAPC1608X90N")
      (description "Capacitor")
      (fields
        (field (name "MANUFACTURER_PART_NUMBER") "CC0603KRX7R9BB104")
        (field (name "MOUSER PART NUMBER") "603-CC603KRX7R9BB104")
      )
      (libsource (lib "AltiumLL") (part "CC0603KRX7R9BB104"))
    )
    (comp (ref "C80")
      (value "0603B103K500NT")
      (footprint "CAPC1608X90N")
      (description "Capacitor")
      (fields (field (name "JLCPCB PART #") "C57112") (field (name "ALTIUM_VALUE") "10nF"))
      (libsource (lib "AltiumLL") (part "0603B103K500NT"))
    )
    (comp (ref "C81")
      (value "1nF")
      (footprint "CAPC1608X90N")
      (description "Capacitor")
      (fields
        (field (name "MANUFACTURER_PART_NUMBER") "CL10B102KB8NNNC")
        (field (name "MOUSER PART NUMBER") "187-CL10B102KB8NNNC")
      )
      (libsource (lib "AltiumLL") (part "CL10B102KB8NNNC"))
    )
    (comp (ref "C82")
      (value "330nF")
      (footprint "CAPC1608X90N")
      (description "Capacitor")
      (fields
        (field (name "MANUFACTURER_PART_NUMBER") "0603B334K250NT")
        (field (name "JLCPCB PART #") "C1615")
      )
      (libsource (lib "AltiumLL") (part "0603B334K250NT"))
    )
    (comp (ref "C83")
      (value "68nF")
      (footprint "CAPC1608X90N")
      (description "Capacitor")
      (fields
        (field (name "MANUFACTURER_PART_NUMBER") "CL10B683KB8NNNC")
        (field (name "JLCPCB PART #") "C31658")
      )
      (libsource (lib "AltiumLL") (part "CL10B683KB8NNNC"))
    )
    (comp (ref "C84")
      (value "1uF")
      (footprint "CAPC1608X90N")
      (description "Capacitor")
      (fields
        (field (name "MANUFACTURER_PART_NUMBER") "CL10A105KB8NNNC")
        (field (name "MOUSER PART NUMBER") "187-CL10A105KB8NNNC")
      )
      (libsource (lib "AltiumLL") (part "CL10A105KB8NNNC"))
    )
    (comp (ref "C85")
      (value "100nF")
      (footprint "CAPC1608X90N")
      (description "Capacitor")
      (fields
        (field (name "MANUFACTURER_PART_NUMBER") "CC0603KRX7R9BB104")
        (field (name "MOUSER PART NUMBER") "603-CC603KRX7R9BB104")
      )
      (libsource (lib "AltiumLL") (part "CC0603KRX7R9BB104"))
    )
    (comp (ref "C86")
      (value "10nF")
      (footprint "CAPC1608X90N")
      (description "Capacitor")
      (fields
        (field (name "MANUFACTURER_PART_NUMBER") "0603B103K500NT")
        (field (name "JLCPCB PART #") "C57112")
      )
      (libsource (lib "AltiumLL") (part "0603B103K500NT"))
    )
    (comp (ref "C87")
      (value "1uF")
      (footprint "CAPC1608X90N")
      (description "Capacitor")
      (fields
        (field (name "MANUFACTURER_PART_NUMBER") "CL10A105KB8NNNC")
        (field (name "MOUSER PART NUMBER") "187-CL10A105KB8NNNC")
      )
      (libsource (lib "AltiumLL") (part "CL10A105KB8NNNC"))
    )
    (comp (ref "C88")
      (value "100nF")
      (footprint "CAPC1608X90N")
      (description "Capacitor")
      (fields
        (field (name "MANUFACTURER_PART_NUMBER") "CC0603KRX7R9BB104")
        (field (name "MOUSER PART NUMBER") "603-CC603KRX7R9BB104")
      )
      (libsource (lib "AltiumLL") (part "CC0603KRX7R9BB104"))
    )
    (comp (ref "C89")
      (value "10nF")
      (footprint "CAPC1608X90N")
      (description "Capacitor")
      (fields
        (field (name "MANUFACTURER_PART_NUMBER") "0603B103K500NT")
        (field (name "JLCPCB PART #") "C57112")
      )
      (libsource (lib "AltiumLL") (part "0603B103K500NT"))
    )
    (comp (ref "D1")
      (value "1N4148W")
      (footprint "SOD3716X135N")
      (description "Diode")
      (fields
        (field (name "MANUFACTURER_PART_NUMBER") "MMSD4148T1G")
        (field (name "MOUSER PART NUMBER") "863-MMSD4148T1G")
      )
      (libsource (lib "AltiumLL") (part "1N4148W"))
    )
    (comp (ref "D2")
      (value "Red")
      (footprint "LED-0805-R-RFS")
      (description "LED")
      (fields
        (field (name "JLCPCB PART #") "C84256")
        (field (name "MANUFACTURER") "Foshan NationStar Optoelectronics")
      )
      (libsource (lib "AltiumLL") (part "NCD0805R1"))
    )
    (comp (ref "D3")
      (value "Blue")
      (footprint "LED-0805-B-RFS")
      (description "LED")
      (fields (field (name "JLCPCB PART #") "C2293") (field (name "MANUFACTURER") "Hubei KENTO Elec"))
      (libsource (lib "AltiumLL") (part "XL-0805QBC"))
    )
    (comp (ref "D4")
      (value "Red")
      (footprint "LED-0805-R-RFS")
      (description "LED")
      (fields
        (field (name "JLCPCB PART #") "C84256")
        (field (name "MANUFACTURER") "Foshan NationStar Optoelectronics")
      )
      (libsource (lib "AltiumLL") (part "NCD0805R1"))
    )
    (comp (ref "D5")
      (value "Blue")
      (footprint "LED-0805-B-RFS")
      (description "LED")
      (fields (field (name "JLCPCB PART #") "C2293") (field (name "MANUFACTURER") "Hubei KENTO Elec"))
      (libsource (lib "AltiumLL") (part "XL-0805QBC"))
    )
    (comp (ref "GPS1")
      (value "GPS-BREAKOUT-V3")
      (footprint "GPS-BREAKOUT-V3")
      (description "GPS")
      (libsource (lib "AltiumLL") (part "GPS-BREAKOUT-V3"))
    )
    (comp (ref "IC1")
      (value "MAX6072AAUB50+")
      (footprint "SOP50P490X110-10N")
      (description "Integrated Circuit")
      (fields (field (name "MOUSER PART NUMBER") "700-MAX6072AAUB50+"))
      (libsource (lib "AltiumLL") (part "MAX6072AAUB50+"))
    )
    (comp (ref "IC2")
      (value "DSPIC30F4013-30I_P")
      (footprint "DIP1543W58P254L5175H635Q40N")
      (description "Integrated Circuit")
      (fields
        (field (name "MANUFACTURER_PART_NUMBER") "DSPIC30F4013-30I/P")
        (field (name "MOUSER PART NUMBER") "579-DSPF401330IP")
      )
      (libsource (lib "AltiumLL") (part "DSPIC30F4013-30I_P"))
    )
    (comp (ref "IC3")
      (value "DHT22")
      (footprint "DHT22")
      (description "Integrated Circuit")
      (libsource (lib "AltiumLL") (part "DHT22"))
    )
    (comp (ref "IC4")
      (value "ADG706BRUZ-REEL7")
      (footprint "SOP65P640X120-28N")
      (description "Integrated Circuit")
      (fields
        (field (name "MOUSER PART NUMBER") "584-ADG706BRUZ-R7")
        (field (name "JLCPCB PART #") "C408400")
      )
      (libsource (lib "AltiumLL") (part "ADG706BRUZ-REEL7"))
    )
    (comp (ref "IC5")
      (value "INA114AP")
      (footprint "DIP794W53P254L959H508Q8N")
      (description "Integrated Circuit")
      (fields (field (name "MOUSER PART NUMBER") "595-INA114AP") (field (name "JLCPCB PART #") "C38890"))
      (libsource (lib "AltiumLL") (part "INA114AP"))
    )
    (comp (ref "IC6")
      (value "ADG706BRUZ-REEL7")
      (footprint "SOP65P640X120-28N")
      (description "Integrated Circuit")
      (fields
        (field (name "MOUSER PART NUMBER") "584-ADG706BRUZ-R7")
        (field (name "JLCPCB PART #") "C408400")
      )
      (libsource (lib "AltiumLL") (part "ADG706BRUZ-REEL7"))
    )
    (comp (ref "IC7")
      (value "INA114AP")
      (footprint "DIP794W53P254L959H508Q8N")
      (description "Integrated Circuit")
      (fields (field (name "MOUSER PART NUMBER") "595-INA114AP") (field (name "JLCPCB PART #") "C38890"))
      (libsource (lib "AltiumLL") (part "INA114AP"))
    )
    (comp (ref "IC8")
      (value "ADG706BRUZ-REEL7")
      (footprint "SOP65P640X120-28N")
      (description "Integrated Circuit")
      (fields
        (field (name "MOUSER PART NUMBER") "584-ADG706BRUZ-R7")
        (field (name "JLCPCB PART #") "C408400")
      )
      (libsource (lib "AltiumLL") (part "ADG706BRUZ-REEL7"))
    )
    (comp (ref "IC9")
      (value "INA114AP")
      (footprint "DIP794W53P254L959H508Q8N")
      (description "Integrated Circuit")
      (fields (field (name "MOUSER PART NUMBER") "595-INA114AP") (field (name "JLCPCB PART #") "C38890"))
      (libsource (lib "AltiumLL") (part "INA114AP"))
    )
    (comp (ref "J1")
      (value "CONECTOR ACELEROMETRO")
      (footprint "HDRV20W87P254_2X10_2553X508X864P")
      (description "Conector")
      (fields (field (name "MANUFACTURER_PART_NUMBER") "0010897200"))
      (libsource (lib "AltiumLL") (part "PEINETA-2x10P"))
    )
    (comp (ref "J2")
      (value "PEINETA-2X20P")
      (footprint "HDRV40W85P254_2X20_5080X500X860P")
      (description "Connector")
      (fields
        (field (name "MANUFACTURER_PART_NUMBER") "2-826656-0")
        (field (name "MOUSER PART NUMBER") "571-2-826656-0")
      )
      (libsource (lib "AltiumLL") (part "PEINETA-2X20P"))
    )
    (comp (ref "P1")
      (value "ENTRADA_ALIMENTACION_2")
      (footprint "SIP-8X1P-F-V")
      (description "Conector")
      (libsource (lib "AltiumLL") (part "PEINETA-8X1P"))
    )
    (comp (ref "P2")
      (value "ENTRADA_ALIMENTACION_1")
      (footprint "SIP-6X1P-F-V")
      (description "Conector")
      (libsource (lib "AltiumLL") (part "PEINETA-6X1P"))
    )
    (comp (ref "P3")
      (value "SIGNALS GEOFONO")
      (footprint "MOLEX-6P")
      (description "Conector")
      (libsource (lib "AltiumLL") (part "MOLEX-6P"))
    )
    (comp (ref "P4")
      (value "ALIMENTACION GEOFONO")
      (footprint "MOLEX-4P")
      (description "Conector")
      (libsource (lib "AltiumLL") (part "MOLEX-4P"))
    )
    (comp (ref "P5")
      (value "PEINETA-6X1P GRABADOR")
      (footprint "SIP-6X1P-M-V")
      (description "Conector")
      (libsource (lib "AltiumLL") (part "PEINETA-6X1P"))
    )
    (comp (ref "Q1")
      (value "2N7002")
      (footprint "SOT96P240X120-3N")
      (description "MOSFET (N-Channel)")
      (fields (field (name "MOUSER PART NUMBER") "781-2N7002") (field (name "JLCPCB PART #") "C8545"))
      (libsource (lib "AltiumLL") (part "2N7002"))
    )
    (comp (ref "Q2")
      (value "2N7002")
      (footprint "SOT96P240X120-3N")
      (description "MOSFET (N-Channel)")
      (fields (field (name "MOUSER PART NUMBER") "781-2N7002") (field (name "JLCPCB PART #") "C8545"))
      (libsource (lib "AltiumLL") (part "2N7002"))
    )
    (comp (ref "Q3")
      (value "2N7002")
      (footprint "SOT96P240X120-3N")
      (description "MOSFET (N-Channel)")
      (fields (field (name "MOUSER PART NUMBER") "781-2N7002") (field (name "JLCPCB PART #") "C8545"))
      (libsource (lib "AltiumLL") (part "2N7002"))
    )
    (comp (ref "Q4")
      (value "2N7002")
      (footprint "SOT96P240X120-3N")
      (description "MOSFET (N-Channel)")
      (fields (field (name "MOUSER PART NUMBER") "781-2N7002") (field (name "JLCPCB PART #") "C8545"))
      (libsource (lib "AltiumLL") (part "2N7002"))
    )
    (comp (ref "Q5")
      (value "2N7002")
      (footprint "SOT96P240X120-3N")
      (description "MOSFET (N-Channel)")
      (fields (field (name "MOUSER PART NUMBER") "781-2N7002") (field (name "JLCPCB PART #") "C8545"))
      (libsource (lib "AltiumLL") (part "2N7002"))
    )
    (comp (ref "Q6")
      (value "2N7002")
      (footprint "SOT96P240X120-3N")
      (description "MOSFET (N-Channel)")
      (fields (field (name "MOUSER PART NUMBER") "781-2N7002") (field (name "JLCPCB PART #") "C8545"))
      (libsource (lib "AltiumLL") (part "2N7002"))
    )
    (comp (ref "Q7")
      (value "2N7002")
      (footprint "SOT96P240X120-3N")
      (description "MOSFET (N-Channel)")
      (fields (field (name "MOUSER PART NUMBER") "781-2N7002") (field (name "JLCPCB PART #") "C8545"))
      (libsource (lib "AltiumLL") (part "2N7002"))
    )
    (comp (ref "Q8")
      (value "2N7002")
      (footprint "SOT96P240X120-3N")
      (description "MOSFET (N-Channel)")
      (fields (field (name "MOUSER PART NUMBER") "781-2N7002") (field (name "JLCPCB PART #") "C8545"))
      (libsource (lib "AltiumLL") (part "2N7002"))
    )
    (comp (ref "Q9")
      (value "2N7002")
      (footprint "SOT96P240X120-3N")
      (description "MOSFET (N-Channel)")
      (fields (field (name "MOUSER PART NUMBER") "781-2N7002") (field (name "JLCPCB PART #") "C8545"))
      (libsource (lib "AltiumLL") (part "2N7002"))
    )
    (comp (ref "Q10")
      (value "2N7002")
      (footprint "SOT96P240X120-3N")
      (description "MOSFET (N-Channel)")
      (fields (field (name "MOUSER PART NUMBER") "781-2N7002") (field (name "JLCPCB PART #") "C8545"))
      (libsource (lib "AltiumLL") (part "2N7002"))
    )
    (comp (ref "Q11")
      (value "2N7002")
      (footprint "SOT96P240X120-3N")
      (description "MOSFET (N-Channel)")
      (fields (field (name "MOUSER PART NUMBER") "781-2N7002") (field (name "JLCPCB PART #") "C8545"))
      (libsource (lib "AltiumLL") (part "2N7002"))
    )
    (comp (ref "Q12")
      (value "2N7002")
      (footprint "SOT96P240X120-3N")
      (description "MOSFET (N-Channel)")
      (fields (field (name "MOUSER PART NUMBER") "781-2N7002") (field (name "JLCPCB PART #") "C8545"))
      (libsource (lib "AltiumLL") (part "2N7002"))
    )
    (comp (ref "Q13")
      (value "2N7002")
      (footprint "SOT96P240X120-3N")
      (description "MOSFET (N-Channel)")
      (fields (field (name "MOUSER PART NUMBER") "781-2N7002") (field (name "JLCPCB PART #") "C8545"))
      (libsource (lib "AltiumLL") (part "2N7002"))
    )
    (comp (ref "R1")
      (value "10R")
      (footprint "RESC2013X65N")
      (description "Resistor")
      (fields
        (field (name "MANUFACTURER_PART_NUMBER") "0805W8F100JT5E")
        (field (name "JLCPCB PART #") "C17415")
      )
      (libsource (lib "AltiumLL") (part "0805W8F100JT5E"))
    )
    (comp (ref "R2")
      (value "0805W8F4701T5E")
      (footprint "RESC2012X50N")
      (description "Resistor")
      (fields (field (name "JLCPCB PART #") "C17673") (field (name "ALTIUM_VALUE") "4K7"))
      (libsource (lib "AltiumLL") (part "0805W8F4701T5E"))
    )
    (comp (ref "R3")
      (value "0805W8F4701T5E")
      (footprint "RESC2012X50N")
      (description "Resistor")
      (fields (field (name "JLCPCB PART #") "C17673") (field (name "ALTIUM_VALUE") "4K7"))
      (libsource (lib "AltiumLL") (part "0805W8F4701T5E"))
    )
    (comp (ref "R4")
      (value "1K")
      (footprint "RESC2012X50N")
      (description "Resistor")
      (fields
        (field (name "MANUFACTURER_PART_NUMBER") "0805W8F1001T5E")
        (field (name "JLCPCB PART #") "C17513")
      )
      (libsource (lib "AltiumLL") (part "0805W8F1001T5E"))
    )
    (comp (ref "R5")
      (value "1K")
      (footprint "RESC2012X50N")
      (description "Resistor")
      (fields
        (field (name "MANUFACTURER_PART_NUMBER") "0805W8F1001T5E")
        (field (name "JLCPCB PART #") "C17513")
      )
      (libsource (lib "AltiumLL") (part "0805W8F1001T5E"))
    )
    (comp (ref "R6")
      (value "10R")
      (footprint "RESC2013X65N")
      (description "Resistor")
      (fields
        (field (name "MANUFACTURER_PART_NUMBER") "0805W8F100JT5E")
        (field (name "JLCPCB PART #") "C17415")
      )
      (libsource (lib "AltiumLL") (part "0805W8F100JT5E"))
    )
    (comp (ref "R7")
      (value "0805W8F4701T5E")
      (footprint "RESC2012X50N")
      (description "Resistor")
      (fields (field (name "JLCPCB PART #") "C17673") (field (name "ALTIUM_VALUE") "4K7"))
      (libsource (lib "AltiumLL") (part "0805W8F4701T5E"))
    )
    (comp (ref "R8")
      (value "1K")
      (footprint "RESC2012X50N")
      (description "Resistor")
      (fields
        (field (name "MANUFACTURER_PART_NUMBER") "0805W8F1001T5E")
        (field (name "JLCPCB PART #") "C17513")
      )
      (libsource (lib "AltiumLL") (part "0805W8F1001T5E"))
    )
    (comp (ref "R9")
      (value "1K")
      (footprint "RESC2012X50N")
      (description "Resistor")
      (fields
        (field (name "MANUFACTURER_PART_NUMBER") "0805W8F1001T5E")
        (field (name "JLCPCB PART #") "C17513")
      )
      (libsource (lib "AltiumLL") (part "0805W8F1001T5E"))
    )
    (comp (ref "R10")
      (value "10R")
      (footprint "RESC2013X65N")
      (description "Resistor")
      (fields
        (field (name "MANUFACTURER_PART_NUMBER") "0805W8F100JT5E")
        (field (name "JLCPCB PART #") "C17415")
      )
      (libsource (lib "AltiumLL") (part "0805W8F100JT5E"))
    )
    (comp (ref "R11")
      (value "1K")
      (footprint "RESC2012X50N")
      (description "Resistor")
      (fields
        (field (name "MANUFACTURER_PART_NUMBER") "0805W8F1001T5E")
        (field (name "JLCPCB PART #") "C17513")
      )
      (libsource (lib "AltiumLL") (part "0805W8F1001T5E"))
    )
    (comp (ref "R12")
      (value "1K")
      (footprint "RESC2012X50N")
      (description "Resistor")
      (fields
        (field (name "MANUFACTURER_PART_NUMBER") "0805W8F1001T5E")
        (field (name "JLCPCB PART #") "C17513")
      )
      (libsource (lib "AltiumLL") (part "0805W8F1001T5E"))
    )
    (comp (ref "R13")
      (value "0603WAF4701T5E")
      (footprint "RES-0603-RFS")
      (description "Resistor")
      (fields
        (field (name "MANUFACTURER") "UNI-ROYAL(Uniroyal Elec)")
        (field (name "JLCPCB PART #") "C23162")
        (field (name "ALTIUM_VALUE") "4K7")
      )
      (libsource (lib "AltiumLL") (part "0603WAF4701T5E"))
    )
    (comp (ref "R14")
      (value "1K")
      (footprint "RESC2012X50N")
      (description "Resistor")
      (fields
        (field (name "MANUFACTURER_PART_NUMBER") "0805W8F1001T5E")
        (field (name "JLCPCB PART #") "C17513")
      )
      (libsource (lib "AltiumLL") (part "0805W8F1001T5E"))
    )
    (comp (ref "R15")
      (value "1K")
      (footprint "RESC2012X50N")
      (description "Resistor")
      (fields
        (field (name "MANUFACTURER_PART_NUMBER") "0805W8F1001T5E")
        (field (name "JLCPCB PART #") "C17513")
      )
      (libsource (lib "AltiumLL") (part "0805W8F1001T5E"))
    )
    (comp (ref "R16")
      (value "1K")
      (footprint "RESC2012X50N")
      (description "Resistor")
      (fields
        (field (name "MANUFACTURER_PART_NUMBER") "0805W8F1001T5E")
        (field (name "JLCPCB PART #") "C17513")
      )
      (libsource (lib "AltiumLL") (part "0805W8F1001T5E"))
    )
    (comp (ref "R17")
      (value "1K")
      (footprint "RESC2012X50N")
      (description "Resistor")
      (fields
        (field (name "MANUFACTURER_PART_NUMBER") "0805W8F1001T5E")
        (field (name "JLCPCB PART #") "C17513")
      )
      (libsource (lib "AltiumLL") (part "0805W8F1001T5E"))
    )
    (comp (ref "R18")
      (value "10R")
      (footprint "RESC2013X65N")
      (description "Resistor")
      (fields
        (field (name "MANUFACTURER_PART_NUMBER") "0805W8F100JT5E")
        (field (name "JLCPCB PART #") "C17415")
      )
      (libsource (lib "AltiumLL") (part "0805W8F100JT5E"))
    )
    (comp (ref "R19")
      (value "4K7")
      (footprint "RESC2012X50N")
      (description "Resistor")
      (fields
        (field (name "MANUFACTURER_PART_NUMBER") "0805W8F4701T5E")
        (field (name "JLCPCB PART #") "C17673")
      )
      (libsource (lib "AltiumLL") (part "0805W8F4701T5E"))
    )
    (comp (ref "R20")
      (value "1K")
      (footprint "RESC2012X50N")
      (description "Resistor")
      (fields
        (field (name "MANUFACTURER_PART_NUMBER") "0805W8F1001T5E")
        (field (name "JLCPCB PART #") "C17513")
      )
      (libsource (lib "AltiumLL") (part "0805W8F1001T5E"))
    )
    (comp (ref "R21")
      (value "1K")
      (footprint "RESC2012X50N")
      (description "Resistor")
      (fields
        (field (name "MANUFACTURER_PART_NUMBER") "0805W8F1001T5E")
        (field (name "JLCPCB PART #") "C17513")
      )
      (libsource (lib "AltiumLL") (part "0805W8F1001T5E"))
    )
    (comp (ref "R22")
      (value "1K")
      (footprint "RESC2012X50N")
      (description "Resistor")
      (fields
        (field (name "MANUFACTURER_PART_NUMBER") "0805W8F1001T5E")
        (field (name "JLCPCB PART #") "C17513")
      )
      (libsource (lib "AltiumLL") (part "0805W8F1001T5E"))
    )
    (comp (ref "R23")
      (value "1K")
      (footprint "RESC2012X50N")
      (description "Resistor")
      (fields
        (field (name "MANUFACTURER_PART_NUMBER") "0805W8F1001T5E")
        (field (name "JLCPCB PART #") "C17513")
      )
      (libsource (lib "AltiumLL") (part "0805W8F1001T5E"))
    )
    (comp (ref "R24")
      (value "10K")
      (footprint "RESC2012X50N")
      (description "Resistor")
      (fields
        (field (name "JLCPCB PART #") "C17414")
        (field (name "MANUFACTURER") "UNI-ROYAL(Uniroyal Elec)")
      )
      (libsource (lib "AltiumLL") (part "0805W8F1002T5E"))
    )
    (comp (ref "R25")
      (value "1K")
      (footprint "RESC2012X50N")
      (description "Resistor")
      (fields
        (field (name "MANUFACTURER_PART_NUMBER") "0805W8F1001T5E")
        (field (name "JLCPCB PART #") "C17513")
      )
      (libsource (lib "AltiumLL") (part "0805W8F1001T5E"))
    )
    (comp (ref "R26")
      (value "1K")
      (footprint "RESC2012X50N")
      (description "Resistor")
      (fields
        (field (name "MANUFACTURER_PART_NUMBER") "0805W8F1001T5E")
        (field (name "JLCPCB PART #") "C17513")
      )
      (libsource (lib "AltiumLL") (part "0805W8F1001T5E"))
    )
    (comp (ref "R27")
      (value "47R")
      (footprint "RESC2013X65N")
      (description "Resistor")
      (fields
        (field (name "MANUFACTURER_PART_NUMBER") "0805W8F470JT5E")
        (field (name "JLCPCB PART #") "C17714")
      )
      (libsource (lib "AltiumLL") (part "0805W8F470JT5E"))
    )
    (comp (ref "R28")
      (value "4K7")
      (footprint "RESC2012X50N")
      (description "Resistor")
      (fields
        (field (name "MANUFACTURER_PART_NUMBER") "0805W8F4701T5E")
        (field (name "JLCPCB PART #") "C17673")
      )
      (libsource (lib "AltiumLL") (part "0805W8F4701T5E"))
    )
    (comp (ref "R29")
      (value "47R")
      (footprint "RESC2013X65N")
      (description "Resistor")
      (fields
        (field (name "MANUFACTURER_PART_NUMBER") "0805W8F470JT5E")
        (field (name "JLCPCB PART #") "C17714")
      )
      (libsource (lib "AltiumLL") (part "0805W8F470JT5E"))
    )
    (comp (ref "R30")
      (value "47R")
      (footprint "RESC2013X65N")
      (description "Resistor")
      (fields
        (field (name "MANUFACTURER_PART_NUMBER") "0805W8F470JT5E")
        (field (name "JLCPCB PART #") "C17714")
      )
      (libsource (lib "AltiumLL") (part "0805W8F470JT5E"))
    )
    (comp (ref "R31")
      (value "47R")
      (footprint "RESC2013X65N")
      (description "Resistor")
      (fields
        (field (name "MANUFACTURER_PART_NUMBER") "0805W8F470JT5E")
        (field (name "JLCPCB PART #") "C17714")
      )
      (libsource (lib "AltiumLL") (part "0805W8F470JT5E"))
    )
    (comp (ref "R32")
      (value "47R")
      (footprint "RESC2013X65N")
      (description "Resistor")
      (fields
        (field (name "MANUFACTURER_PART_NUMBER") "0805W8F470JT5E")
        (field (name "JLCPCB PART #") "C17714")
      )
      (libsource (lib "AltiumLL") (part "0805W8F470JT5E"))
    )
    (comp (ref "R33")
      (value "1K")
      (footprint "RESC2012X50N")
      (description "Resistor")
      (fields
        (field (name "MANUFACTURER_PART_NUMBER") "0805W8F1001T5E")
        (field (name "JLCPCB PART #") "C17513")
      )
      (libsource (lib "") (part "0805W8F1001T5E_1"))
    )
    (comp (ref "R34")
      (value "1K")
      (footprint "RESC2012X50N")
      (description "Resistor")
      (fields
        (field (name "MANUFACTURER_PART_NUMBER") "0805W8F1001T5E")
        (field (name "JLCPCB PART #") "C17513")
      )
      (libsource (lib "AltiumLL") (part "0805W8F1001T5E"))
    )
    (comp (ref "R35")
      (value "1K")
      (footprint "RESC2012X50N")
      (description "Resistor")
      (fields
        (field (name "MANUFACTURER_PART_NUMBER") "0805W8F1001T5E")
        (field (name "JLCPCB PART #") "C17513")
      )
      (libsource (lib "AltiumLL") (part "0805W8F1001T5E"))
    )
    (comp (ref "R36")
      (value "1K")
      (footprint "RESC2012X50N")
      (description "Resistor")
      (fields
        (field (name "MANUFACTURER_PART_NUMBER") "0805W8F1001T5E")
        (field (name "JLCPCB PART #") "C17513")
      )
      (libsource (lib "AltiumLL") (part "0805W8F1001T5E"))
    )
    (comp (ref "R37")
      (value "1K")
      (footprint "RESC2012X50N")
      (description "Resistor")
      (fields
        (field (name "MANUFACTURER_PART_NUMBER") "0805W8F1001T5E")
        (field (name "JLCPCB PART #") "C17513")
      )
      (libsource (lib "AltiumLL") (part "0805W8F1001T5E"))
    )
    (comp (ref "R38")
      (value "1K")
      (footprint "RESC2012X50N")
      (description "Resistor")
      (fields
        (field (name "MANUFACTURER_PART_NUMBER") "0805W8F1001T5E")
        (field (name "JLCPCB PART #") "C17513")
      )
      (libsource (lib "AltiumLL") (part "0805W8F1001T5E"))
    )
    (comp (ref "R39")
      (value "1K")
      (footprint "RESC2012X50N")
      (description "Resistor")
      (fields
        (field (name "MANUFACTURER_PART_NUMBER") "0805W8F1001T5E")
        (field (name "JLCPCB PART #") "C17513")
      )
      (libsource (lib "AltiumLL") (part "0805W8F1001T5E"))
    )
    (comp (ref "R40")
      (value "1K")
      (footprint "RESC2012X50N")
      (description "Resistor")
      (fields
        (field (name "MANUFACTURER_PART_NUMBER") "0805W8F1001T5E")
        (field (name "JLCPCB PART #") "C17513")
      )
      (libsource (lib "AltiumLL") (part "0805W8F1001T5E"))
    )
    (comp (ref "R41")
      (value "1K")
      (footprint "RESC2012X50N")
      (description "Resistor")
      (fields
        (field (name "MANUFACTURER_PART_NUMBER") "0805W8F1001T5E")
        (field (name "JLCPCB PART #") "C17513")
      )
      (libsource (lib "AltiumLL") (part "0805W8F1001T5E"))
    )
    (comp (ref "R42")
      (value "1K")
      (footprint "RESC2012X50N")
      (description "Resistor")
      (fields
        (field (name "MANUFACTURER_PART_NUMBER") "0805W8F1001T5E")
        (field (name "JLCPCB PART #") "C17513")
      )
      (libsource (lib "") (part "0805W8F1001T5E_1"))
    )
    (comp (ref "R43")
      (value "1K")
      (footprint "RESC2012X50N")
      (description "Resistor")
      (fields
        (field (name "MANUFACTURER_PART_NUMBER") "0805W8F1001T5E")
        (field (name "JLCPCB PART #") "C17513")
      )
      (libsource (lib "AltiumLL") (part "0805W8F1001T5E"))
    )
    (comp (ref "R44")
      (value "1K")
      (footprint "RESC2012X50N")
      (description "Resistor")
      (fields
        (field (name "MANUFACTURER_PART_NUMBER") "0805W8F1001T5E")
        (field (name "JLCPCB PART #") "C17513")
      )
      (libsource (lib "AltiumLL") (part "0805W8F1001T5E"))
    )
    (comp (ref "R45")
      (value "47R")
      (footprint "RESC2013X65N")
      (description "Resistor")
      (fields
        (field (name "MANUFACTURER_PART_NUMBER") "0805W8F470JT5E")
        (field (name "JLCPCB PART #") "C17714")
      )
      (libsource (lib "AltiumLL") (part "0805W8F470JT5E"))
    )
    (comp (ref "R46")
      (value "47R")
      (footprint "RESC2013X65N")
      (description "Resistor")
      (fields
        (field (name "MANUFACTURER_PART_NUMBER") "0805W8F470JT5E")
        (field (name "JLCPCB PART #") "C17714")
      )
      (libsource (lib "AltiumLL") (part "0805W8F470JT5E"))
    )
    (comp (ref "R47")
      (value "47R")
      (footprint "RESC2013X65N")
      (description "Resistor")
      (fields
        (field (name "MANUFACTURER_PART_NUMBER") "0805W8F470JT5E")
        (field (name "JLCPCB PART #") "C17714")
      )
      (libsource (lib "AltiumLL") (part "0805W8F470JT5E"))
    )
    (comp (ref "R48")
      (value "47R")
      (footprint "RESC2013X65N")
      (description "Resistor")
      (fields
        (field (name "MANUFACTURER_PART_NUMBER") "0805W8F470JT5E")
        (field (name "JLCPCB PART #") "C17714")
      )
      (libsource (lib "AltiumLL") (part "0805W8F470JT5E"))
    )
    (comp (ref "R49")
      (value "100R")
      (footprint "RESC2013X65N")
      (description "Resistor")
      (fields
        (field (name "MANUFACTURER_PART_NUMBER") "0805W8F1000T5E")
        (field (name "JLCPCB PART #") "C17408")
      )
      (libsource (lib "AltiumLL") (part "0805W8F1000T5E"))
    )
    (comp (ref "R50")
      (value "100R")
      (footprint "RESC2013X65N")
      (description "Resistor")
      (fields
        (field (name "MANUFACTURER_PART_NUMBER") "0805W8F1000T5E")
        (field (name "JLCPCB PART #") "C17408")
      )
      (libsource (lib "AltiumLL") (part "0805W8F1000T5E"))
    )
    (comp (ref "R51")
      (value "820R")
      (footprint "RESC2013X65N")
      (description "Resistor")
      (fields
        (field (name "MANUFACTURER_PART_NUMBER") "0805W8F8200T5E")
        (field (name "JLCPCB PART #") "C17837")
      )
      (libsource (lib "AltiumLL") (part "0805W8F8200T5E"))
    )
    (comp (ref "R52")
      (value "IND")
      (footprint "6-0805_N")
      (description "Resistor")
      (fields (field (name "Comment") "Res1") (field (name "PUBLISHER") "Altium Limited"))
      (libsource (lib "Miscellaneous Devices") (part "Res1"))
    )
    (comp (ref "R53")
      (value "1.62k")
      (footprint "6-0805_N")
      (description "Resistor")
      (fields (field (name "Comment") "Res1") (field (name "PUBLISHER") "Altium Limited"))
      (libsource (lib "Miscellaneous Devices") (part "Res1"))
    )
    (comp (ref "R54")
      (value "IND")
      (footprint "6-0805_N")
      (description "Resistor")
      (fields (field (name "Comment") "Res1") (field (name "PUBLISHER") "Altium Limited"))
      (libsource (lib "Miscellaneous Devices") (part "Res1"))
    )
    (comp (ref "R55")
      (value "3K3")
      (footprint "RESC2013X65N")
      (description "Resistor")
      (fields
        (field (name "MANUFACTURER_PART_NUMBER") "0805W8F3301T5E")
        (field (name "JLCPCB PART #") "C26010")
      )
      (libsource (lib "AltiumLL") (part "0805W8F3301T5E"))
    )
    (comp (ref "R56")
      (value "20K")
      (footprint "RESC2012X50N")
      (description "Resistor")
      (fields
        (field (name "MANUFACTURER_PART_NUMBER") "0805W8F2002T5E")
        (field (name "JLCPCB PART #") "C4328")
      )
      (libsource (lib "AltiumLL") (part "0805W8F2002T5E"))
    )
    (comp (ref "R57")
      (value "10R")
      (footprint "RESC2013X65N")
      (description "Resistor")
      (fields
        (field (name "MANUFACTURER_PART_NUMBER") "0805W8F100JT5E")
        (field (name "JLCPCB PART #") "C17415")
      )
      (libsource (lib "AltiumLL") (part "0805W8F100JT5E"))
    )
    (comp (ref "R58")
      (value "6K8")
      (footprint "RESC2013X65N")
      (description "Resistor")
      (fields
        (field (name "MANUFACTURER_PART_NUMBER") "0805W8F6801T5E")
        (field (name "JLCPCB PART #") "C17772")
      )
      (libsource (lib "AltiumLL") (part "0805W8F6801T5E"))
    )
    (comp (ref "R59")
      (value "22R")
      (footprint "RESC2013X65N")
      (description "Resistor")
      (fields
        (field (name "MANUFACTURER_PART_NUMBER") "0805W8F220JT5E")
        (field (name "JLCPCB PART #") "C17561")
      )
      (libsource (lib "AltiumLL") (part "0805W8F220JT5E"))
    )
    (comp (ref "R60")
      (value "16.5k")
      (footprint "6-0805_N")
      (description "Resistor")
      (fields (field (name "Comment") "Res1") (field (name "PUBLISHER") "Altium Limited"))
      (libsource (lib "Miscellaneous Devices") (part "Res1"))
    )
    (comp (ref "R61")
      (value "3K3")
      (footprint "RESC2013X65N")
      (description "Resistor")
      (fields
        (field (name "MANUFACTURER_PART_NUMBER") "0805W8F3301T5E")
        (field (name "JLCPCB PART #") "C26010")
      )
      (libsource (lib "AltiumLL") (part "0805W8F3301T5E"))
    )
    (comp (ref "R62")
      (value "8K2")
      (footprint "RESC2013X65N")
      (description "Resistor")
      (fields
        (field (name "MANUFACTURER_PART_NUMBER") "0805W8F8201T5E")
        (field (name "JLCPCB PART #") "C17828")
      )
      (libsource (lib "AltiumLL") (part "0805W8F8201T5E"))
    )
    (comp (ref "R63")
      (value "47R")
      (footprint "RESC2013X65N")
      (description "Resistor")
      (fields
        (field (name "MANUFACTURER_PART_NUMBER") "0805W8F470JT5E")
        (field (name "JLCPCB PART #") "C17714")
      )
      (libsource (lib "AltiumLL") (part "0805W8F470JT5E"))
    )
    (comp (ref "R64")
      (value "49.9K")
      (footprint "RESC2013X65N")
      (description "Resistor")
      (fields
        (field (name "MANUFACTURER_PART_NUMBER") "0805W8F4992T5E")
        (field (name "JLCPCB PART #") "C17719")
      )
      (libsource (lib "AltiumLL") (part "0805W8F4992T5E"))
    )
    (comp (ref "R65")
      (value "4K7")
      (footprint "RESC2012X50N")
      (description "Resistor")
      (fields
        (field (name "MANUFACTURER_PART_NUMBER") "0805W8F4701T5E")
        (field (name "JLCPCB PART #") "C17673")
      )
      (libsource (lib "AltiumLL") (part "0805W8F4701T5E"))
    )
    (comp (ref "R66")
      (value "18K")
      (footprint "RESC2013X65N")
      (description "Resistor")
      (fields
        (field (name "MANUFACTURER_PART_NUMBER") "0805W8F1802T5E")
        (field (name "JLCPCB PART #") "C17506")
      )
      (libsource (lib "AltiumLL") (part "0805W8F1802T5E"))
    )
    (comp (ref "R67")
      (value "100R")
      (footprint "RESC2013X65N")
      (description "Resistor")
      (fields
        (field (name "MANUFACTURER_PART_NUMBER") "0805W8F1000T5E")
        (field (name "JLCPCB PART #") "C17408")
      )
      (libsource (lib "AltiumLL") (part "0805W8F1000T5E"))
    )
    (comp (ref "R68")
      (value "IND")
      (footprint "6-0805_N")
      (description "Resistor")
      (fields (field (name "Comment") "Res1") (field (name "PUBLISHER") "Altium Limited"))
      (libsource (lib "Miscellaneous Devices") (part "Res1"))
    )
    (comp (ref "R69")
      (value "1K")
      (footprint "RESC2012X50N")
      (description "Resistor")
      (fields
        (field (name "MANUFACTURER_PART_NUMBER") "0805W8F1001T5E")
        (field (name "JLCPCB PART #") "C17513")
      )
      (libsource (lib "") (part "0805W8F1001T5E_1"))
    )
    (comp (ref "R70")
      (value "180R")
      (footprint "RESC2013X65N")
      (description "Resistor")
      (fields
        (field (name "MANUFACTURER_PART_NUMBER") "0805W8F1800T5E")
        (field (name "JLCPCB PART #") "C25270")
      )
      (libsource (lib "AltiumLL") (part "0805W8F1800T5E"))
    )
    (comp (ref "R71")
      (value "IND")
      (footprint "6-0805_N")
      (description "Resistor")
      (fields (field (name "Comment") "Res1") (field (name "PUBLISHER") "Altium Limited"))
      (libsource (lib "Miscellaneous Devices") (part "Res1"))
    )
    (comp (ref "R72")
      (value "20K")
      (footprint "RESC2012X50N")
      (description "Resistor")
      (fields
        (field (name "MANUFACTURER_PART_NUMBER") "0805W8F2002T5E")
        (field (name "JLCPCB PART #") "C4328")
      )
      (libsource (lib "AltiumLL") (part "0805W8F2002T5E"))
    )
    (comp (ref "R73")
      (value "390R")
      (footprint "RESC2013X65N")
      (description "Resistor")
      (fields
        (field (name "MANUFACTURER_PART_NUMBER") "0805W8F3900T5E")
        (field (name "JLCPCB PART #") "C17655")
      )
      (libsource (lib "AltiumLL") (part "0805W8F3900T5E"))
    )
    (comp (ref "R74")
      (value "1K")
      (footprint "RESC2012X50N")
      (description "Resistor")
      (fields
        (field (name "MANUFACTURER_PART_NUMBER") "0805W8F1001T5E")
        (field (name "JLCPCB PART #") "C17513")
      )
      (libsource (lib "") (part "0805W8F1001T5E_1"))
    )
    (comp (ref "R75")
      (value "100R")
      (footprint "RESC2013X65N")
      (description "Resistor")
      (fields
        (field (name "MANUFACTURER_PART_NUMBER") "0805W8F1000T5E")
        (field (name "JLCPCB PART #") "C17408")
      )
      (libsource (lib "AltiumLL") (part "0805W8F1000T5E"))
    )
    (comp (ref "R76")
      (value "100R")
      (footprint "RESC2013X65N")
      (description "Resistor")
      (fields
        (field (name "MANUFACTURER_PART_NUMBER") "0805W8F1000T5E")
        (field (name "JLCPCB PART #") "C17408")
      )
      (libsource (lib "AltiumLL") (part "0805W8F1000T5E"))
    )
    (comp (ref "R77")
      (value "47R")
      (footprint "RESC2013X65N")
      (description "Resistor")
      (fields
        (field (name "MANUFACTURER_PART_NUMBER") "0805W8F470JT5E")
        (field (name "JLCPCB PART #") "C17714")
      )
      (libsource (lib "AltiumLL") (part "0805W8F470JT5E"))
    )
    (comp (ref "R78")
      (value "47R")
      (footprint "RESC2013X65N")
      (description "Resistor")
      (fields
        (field (name "MANUFACTURER_PART_NUMBER") "0805W8F470JT5E")
        (field (name "JLCPCB PART #") "C17714")
      )
      (libsource (lib "AltiumLL") (part "0805W8F470JT5E"))
    )
    (comp (ref "R79")
      (value "1K")
      (footprint "RESC2012X50N")
      (description "Resistor")
      (fields
        (field (name "MANUFACTURER_PART_NUMBER") "0805W8F1001T5E")
        (field (name "JLCPCB PART #") "C17513")
      )
      (libsource (lib "") (part "0805W8F1001T5E_1"))
    )
    (comp (ref "R80")
      (value "1K")
      (footprint "RESC2012X50N")
      (description "Resistor")
      (fields
        (field (name "MANUFACTURER_PART_NUMBER") "0805W8F1001T5E")
        (field (name "JLCPCB PART #") "C17513")
      )
      (libsource (lib "") (part "0805W8F1001T5E_2"))
    )
    (comp (ref "R81")
      (value "47R")
      (footprint "RESC2013X65N")
      (description "Resistor")
      (fields
        (field (name "MANUFACTURER_PART_NUMBER") "0805W8F470JT5E")
        (field (name "JLCPCB PART #") "C17714")
      )
      (libsource (lib "AltiumLL") (part "0805W8F470JT5E"))
    )
    (comp (ref "R82")
      (value "47R")
      (footprint "RESC2013X65N")
      (description "Resistor")
      (fields
        (field (name "MANUFACTURER_PART_NUMBER") "0805W8F470JT5E")
        (field (name "JLCPCB PART #") "C17714")
      )
      (libsource (lib "AltiumLL") (part "0805W8F470JT5E"))
    )
    (comp (ref "R83")
      (value "100R")
      (footprint "RESC2013X65N")
      (description "Resistor")
      (fields
        (field (name "MANUFACTURER_PART_NUMBER") "0805W8F1000T5E")
        (field (name "JLCPCB PART #") "C17408")
      )
      (libsource (lib "AltiumLL") (part "0805W8F1000T5E"))
    )
    (comp (ref "R84")
      (value "100R")
      (footprint "RESC2013X65N")
      (description "Resistor")
      (fields
        (field (name "MANUFACTURER_PART_NUMBER") "0805W8F1000T5E")
        (field (name "JLCPCB PART #") "C17408")
      )
      (libsource (lib "AltiumLL") (part "0805W8F1000T5E"))
    )
    (comp (ref "R85")
      (value "820R")
      (footprint "RESC2013X65N")
      (description "Resistor")
      (fields
        (field (name "MANUFACTURER_PART_NUMBER") "0805W8F8200T5E")
        (field (name "JLCPCB PART #") "C17837")
      )
      (libsource (lib "AltiumLL") (part "0805W8F8200T5E"))
    )
    (comp (ref "R86")
      (value "IND")
      (footprint "6-0805_N")
      (description "Resistor")
      (fields (field (name "Comment") "Res1") (field (name "PUBLISHER") "Altium Limited"))
      (libsource (lib "Miscellaneous Devices") (part "Res1"))
    )
    (comp (ref "R87")
      (value "1.62k")
      (footprint "6-0805_N")
      (description "Resistor")
      (fields (field (name "Comment") "Res1") (field (name "PUBLISHER") "Altium Limited"))
      (libsource (lib "Miscellaneous Devices") (part "Res1"))
    )
    (comp (ref "R88")
      (value "IND")
      (footprint "6-0805_N")
      (description "Resistor")
      (fields (field (name "Comment") "Res1") (field (name "PUBLISHER") "Altium Limited"))
      (libsource (lib "Miscellaneous Devices") (part "Res1"))
    )
    (comp (ref "R89")
      (value "3K3")
      (footprint "RESC2013X65N")
      (description "Resistor")
      (fields
        (field (name "MANUFACTURER_PART_NUMBER") "0805W8F3301T5E")
        (field (name "JLCPCB PART #") "C26010")
      )
      (libsource (lib "AltiumLL") (part "0805W8F3301T5E"))
    )
    (comp (ref "R90")
      (value "20K")
      (footprint "RESC2012X50N")
      (description "Resistor")
      (fields
        (field (name "MANUFACTURER_PART_NUMBER") "0805W8F2002T5E")
        (field (name "JLCPCB PART #") "C4328")
      )
      (libsource (lib "AltiumLL") (part "0805W8F2002T5E"))
    )
    (comp (ref "R91")
      (value "10R")
      (footprint "RESC2013X65N")
      (description "Resistor")
      (fields
        (field (name "MANUFACTURER_PART_NUMBER") "0805W8F100JT5E")
        (field (name "JLCPCB PART #") "C17415")
      )
      (libsource (lib "AltiumLL") (part "0805W8F100JT5E"))
    )
    (comp (ref "R92")
      (value "6K8")
      (footprint "RESC2013X65N")
      (description "Resistor")
      (fields
        (field (name "MANUFACTURER_PART_NUMBER") "0805W8F6801T5E")
        (field (name "JLCPCB PART #") "C17772")
      )
      (libsource (lib "AltiumLL") (part "0805W8F6801T5E"))
    )
    (comp (ref "R93")
      (value "22R")
      (footprint "RESC2013X65N")
      (description "Resistor")
      (fields
        (field (name "MANUFACTURER_PART_NUMBER") "0805W8F220JT5E")
        (field (name "JLCPCB PART #") "C17561")
      )
      (libsource (lib "AltiumLL") (part "0805W8F220JT5E"))
    )
    (comp (ref "R94")
      (value "16.5k")
      (footprint "6-0805_N")
      (description "Resistor")
      (fields (field (name "Comment") "Res1") (field (name "PUBLISHER") "Altium Limited"))
      (libsource (lib "Miscellaneous Devices") (part "Res1"))
    )
    (comp (ref "R95")
      (value "3K3")
      (footprint "RESC2013X65N")
      (description "Resistor")
      (fields
        (field (name "MANUFACTURER_PART_NUMBER") "0805W8F3301T5E")
        (field (name "JLCPCB PART #") "C26010")
      )
      (libsource (lib "AltiumLL") (part "0805W8F3301T5E"))
    )
    (comp (ref "R96")
      (value "8K2")
      (footprint "RESC2013X65N")
      (description "Resistor")
      (fields
        (field (name "MANUFACTURER_PART_NUMBER") "0805W8F8201T5E")
        (field (name "JLCPCB PART #") "C17828")
      )
      (libsource (lib "AltiumLL") (part "0805W8F8201T5E"))
    )
    (comp (ref "R97")
      (value "47R")
      (footprint "RESC2013X65N")
      (description "Resistor")
      (fields
        (field (name "MANUFACTURER_PART_NUMBER") "0805W8F470JT5E")
        (field (name "JLCPCB PART #") "C17714")
      )
      (libsource (lib "AltiumLL") (part "0805W8F470JT5E"))
    )
    (comp (ref "R98")
      (value "49.9K")
      (footprint "RESC2013X65N")
      (description "Resistor")
      (fields
        (field (name "MANUFACTURER_PART_NUMBER") "0805W8F4992T5E")
        (field (name "JLCPCB PART #") "C17719")
      )
      (libsource (lib "AltiumLL") (part "0805W8F4992T5E"))
    )
    (comp (ref "R99")
      (value "4K7")
      (footprint "RESC2012X50N")
      (description "Resistor")
      (fields
        (field (name "MANUFACTURER_PART_NUMBER") "0805W8F4701T5E")
        (field (name "JLCPCB PART #") "C17673")
      )
      (libsource (lib "AltiumLL") (part "0805W8F4701T5E"))
    )
    (comp (ref "R100")
      (value "18K")
      (footprint "RESC2013X65N")
      (description "Resistor")
      (fields
        (field (name "MANUFACTURER_PART_NUMBER") "0805W8F1802T5E")
        (field (name "JLCPCB PART #") "C17506")
      )
      (libsource (lib "AltiumLL") (part "0805W8F1802T5E"))
    )
    (comp (ref "R101")
      (value "100R")
      (footprint "RESC2013X65N")
      (description "Resistor")
      (fields
        (field (name "MANUFACTURER_PART_NUMBER") "0805W8F1000T5E")
        (field (name "JLCPCB PART #") "C17408")
      )
      (libsource (lib "AltiumLL") (part "0805W8F1000T5E"))
    )
    (comp (ref "R102")
      (value "IND")
      (footprint "6-0805_N")
      (description "Resistor")
      (fields (field (name "Comment") "Res1") (field (name "PUBLISHER") "Altium Limited"))
      (libsource (lib "Miscellaneous Devices") (part "Res1"))
    )
    (comp (ref "R103")
      (value "1K")
      (footprint "RESC2012X50N")
      (description "Resistor")
      (fields
        (field (name "MANUFACTURER_PART_NUMBER") "0805W8F1001T5E")
        (field (name "JLCPCB PART #") "C17513")
      )
      (libsource (lib "") (part "0805W8F1001T5E_1"))
    )
    (comp (ref "R104")
      (value "180R")
      (footprint "RESC2013X65N")
      (description "Resistor")
      (fields
        (field (name "MANUFACTURER_PART_NUMBER") "0805W8F1800T5E")
        (field (name "JLCPCB PART #") "C25270")
      )
      (libsource (lib "AltiumLL") (part "0805W8F1800T5E"))
    )
    (comp (ref "R105")
      (value "IND")
      (footprint "6-0805_N")
      (description "Resistor")
      (fields (field (name "Comment") "Res1") (field (name "PUBLISHER") "Altium Limited"))
      (libsource (lib "Miscellaneous Devices") (part "Res1"))
    )
    (comp (ref "R106")
      (value "20K")
      (footprint "RESC2012X50N")
      (description "Resistor")
      (fields
        (field (name "MANUFACTURER_PART_NUMBER") "0805W8F2002T5E")
        (field (name "JLCPCB PART #") "C4328")
      )
      (libsource (lib "AltiumLL") (part "0805W8F2002T5E"))
    )
    (comp (ref "R107")
      (value "390R")
      (footprint "RESC2013X65N")
      (description "Resistor")
      (fields
        (field (name "MANUFACTURER_PART_NUMBER") "0805W8F3900T5E")
        (field (name "JLCPCB PART #") "C17655")
      )
      (libsource (lib "AltiumLL") (part "0805W8F3900T5E"))
    )
    (comp (ref "R108")
      (value "1K")
      (footprint "RESC2012X50N")
      (description "Resistor")
      (fields
        (field (name "MANUFACTURER_PART_NUMBER") "0805W8F1001T5E")
        (field (name "JLCPCB PART #") "C17513")
      )
      (libsource (lib "") (part "0805W8F1001T5E_1"))
    )
    (comp (ref "R109")
      (value "100R")
      (footprint "RESC2013X65N")
      (description "Resistor")
      (fields
        (field (name "MANUFACTURER_PART_NUMBER") "0805W8F1000T5E")
        (field (name "JLCPCB PART #") "C17408")
      )
      (libsource (lib "AltiumLL") (part "0805W8F1000T5E"))
    )
    (comp (ref "R110")
      (value "100R")
      (footprint "RESC2013X65N")
      (description "Resistor")
      (fields
        (field (name "MANUFACTURER_PART_NUMBER") "0805W8F1000T5E")
        (field (name "JLCPCB PART #") "C17408")
      )
      (libsource (lib "AltiumLL") (part "0805W8F1000T5E"))
    )
    (comp (ref "R111")
      (value "47R")
      (footprint "RESC2013X65N")
      (description "Resistor")
      (fields
        (field (name "MANUFACTURER_PART_NUMBER") "0805W8F470JT5E")
        (field (name "JLCPCB PART #") "C17714")
      )
      (libsource (lib "AltiumLL") (part "0805W8F470JT5E"))
    )
    (comp (ref "R112")
      (value "47R")
      (footprint "RESC2013X65N")
      (description "Resistor")
      (fields
        (field (name "MANUFACTURER_PART_NUMBER") "0805W8F470JT5E")
        (field (name "JLCPCB PART #") "C17714")
      )
      (libsource (lib "AltiumLL") (part "0805W8F470JT5E"))
    )
    (comp (ref "R113")
      (value "1K")
      (footprint "RESC2012X50N")
      (description "Resistor")
      (fields
        (field (name "MANUFACTURER_PART_NUMBER") "0805W8F1001T5E")
        (field (name "JLCPCB PART #") "C17513")
      )
      (libsource (lib "") (part "0805W8F1001T5E_1"))
    )
    (comp (ref "R114")
      (value "1K")
      (footprint "RESC2012X50N")
      (description "Resistor")
      (fields
        (field (name "MANUFACTURER_PART_NUMBER") "0805W8F1001T5E")
        (field (name "JLCPCB PART #") "C17513")
      )
      (libsource (lib "") (part "0805W8F1001T5E_2"))
    )
    (comp (ref "R115")
      (value "47R")
      (footprint "RESC2013X65N")
      (description "Resistor")
      (fields
        (field (name "MANUFACTURER_PART_NUMBER") "0805W8F470JT5E")
        (field (name "JLCPCB PART #") "C17714")
      )
      (libsource (lib "AltiumLL") (part "0805W8F470JT5E"))
    )
    (comp (ref "R116")
      (value "47R")
      (footprint "RESC2013X65N")
      (description "Resistor")
      (fields
        (field (name "MANUFACTURER_PART_NUMBER") "0805W8F470JT5E")
        (field (name "JLCPCB PART #") "C17714")
      )
      (libsource (lib "AltiumLL") (part "0805W8F470JT5E"))
    )
    (comp (ref "R117")
      (value "100R")
      (footprint "RESC2013X65N")
      (description "Resistor")
      (fields
        (field (name "MANUFACTURER_PART_NUMBER") "0805W8F1000T5E")
        (field (name "JLCPCB PART #") "C17408")
      )
      (libsource (lib "AltiumLL") (part "0805W8F1000T5E"))
    )
    (comp (ref "R118")
      (value "100R")
      (footprint "RESC2013X65N")
      (description "Resistor")
      (fields
        (field (name "MANUFACTURER_PART_NUMBER") "0805W8F1000T5E")
        (field (name "JLCPCB PART #") "C17408")
      )
      (libsource (lib "AltiumLL") (part "0805W8F1000T5E"))
    )
    (comp (ref "R119")
      (value "820R")
      (footprint "RESC2013X65N")
      (description "Resistor")
      (fields
        (field (name "MANUFACTURER_PART_NUMBER") "0805W8F8200T5E")
        (field (name "JLCPCB PART #") "C17837")
      )
      (libsource (lib "AltiumLL") (part "0805W8F8200T5E"))
    )
    (comp (ref "R120")
      (value "IND")
      (footprint "6-0805_N")
      (description "Resistor")
      (fields (field (name "Comment") "Res1") (field (name "PUBLISHER") "Altium Limited"))
      (libsource (lib "Miscellaneous Devices") (part "Res1"))
    )
    (comp (ref "R121")
      (value "1.62k")
      (footprint "6-0805_N")
      (description "Resistor")
      (fields (field (name "Comment") "Res1") (field (name "PUBLISHER") "Altium Limited"))
      (libsource (lib "Miscellaneous Devices") (part "Res1"))
    )
    (comp (ref "R122")
      (value "IND")
      (footprint "6-0805_N")
      (description "Resistor")
      (fields (field (name "Comment") "Res1") (field (name "PUBLISHER") "Altium Limited"))
      (libsource (lib "Miscellaneous Devices") (part "Res1"))
    )
    (comp (ref "R123")
      (value "3K3")
      (footprint "RESC2013X65N")
      (description "Resistor")
      (fields
        (field (name "MANUFACTURER_PART_NUMBER") "0805W8F3301T5E")
        (field (name "JLCPCB PART #") "C26010")
      )
      (libsource (lib "AltiumLL") (part "0805W8F3301T5E"))
    )
    (comp (ref "R124")
      (value "20K")
      (footprint "RESC2012X50N")
      (description "Resistor")
      (fields
        (field (name "MANUFACTURER_PART_NUMBER") "0805W8F2002T5E")
        (field (name "JLCPCB PART #") "C4328")
      )
      (libsource (lib "AltiumLL") (part "0805W8F2002T5E"))
    )
    (comp (ref "R125")
      (value "10R")
      (footprint "RESC2013X65N")
      (description "Resistor")
      (fields
        (field (name "MANUFACTURER_PART_NUMBER") "0805W8F100JT5E")
        (field (name "JLCPCB PART #") "C17415")
      )
      (libsource (lib "AltiumLL") (part "0805W8F100JT5E"))
    )
    (comp (ref "R126")
      (value "6K8")
      (footprint "RESC2013X65N")
      (description "Resistor")
      (fields
        (field (name "MANUFACTURER_PART_NUMBER") "0805W8F6801T5E")
        (field (name "JLCPCB PART #") "C17772")
      )
      (libsource (lib "AltiumLL") (part "0805W8F6801T5E"))
    )
    (comp (ref "R127")
      (value "22R")
      (footprint "RESC2013X65N")
      (description "Resistor")
      (fields
        (field (name "MANUFACTURER_PART_NUMBER") "0805W8F220JT5E")
        (field (name "JLCPCB PART #") "C17561")
      )
      (libsource (lib "AltiumLL") (part "0805W8F220JT5E"))
    )
    (comp (ref "R128")
      (value "16.5k")
      (footprint "6-0805_N")
      (description "Resistor")
      (fields (field (name "Comment") "Res1") (field (name "PUBLISHER") "Altium Limited"))
      (libsource (lib "Miscellaneous Devices") (part "Res1"))
    )
    (comp (ref "R129")
      (value "3K3")
      (footprint "RESC2013X65N")
      (description "Resistor")
      (fields
        (field (name "MANUFACTURER_PART_NUMBER") "0805W8F3301T5E")
        (field (name "JLCPCB PART #") "C26010")
      )
      (libsource (lib "AltiumLL") (part "0805W8F3301T5E"))
    )
    (comp (ref "R130")
      (value "8K2")
      (footprint "RESC2013X65N")
      (description "Resistor")
      (fields
        (field (name "MANUFACTURER_PART_NUMBER") "0805W8F8201T5E")
        (field (name "JLCPCB PART #") "C17828")
      )
      (libsource (lib "AltiumLL") (part "0805W8F8201T5E"))
    )
    (comp (ref "R131")
      (value "47R")
      (footprint "RESC2013X65N")
      (description "Resistor")
      (fields
        (field (name "MANUFACTURER_PART_NUMBER") "0805W8F470JT5E")
        (field (name "JLCPCB PART #") "C17714")
      )
      (libsource (lib "AltiumLL") (part "0805W8F470JT5E"))
    )
    (comp (ref "R132")
      (value "49.9K")
      (footprint "RESC2013X65N")
      (description "Resistor")
      (fields
        (field (name "MANUFACTURER_PART_NUMBER") "0805W8F4992T5E")
        (field (name "JLCPCB PART #") "C17719")
      )
      (libsource (lib "AltiumLL") (part "0805W8F4992T5E"))
    )
    (comp (ref "R133")
      (value "4K7")
      (footprint "RESC2012X50N")
      (description "Resistor")
      (fields
        (field (name "MANUFACTURER_PART_NUMBER") "0805W8F4701T5E")
        (field (name "JLCPCB PART #") "C17673")
      )
      (libsource (lib "AltiumLL") (part "0805W8F4701T5E"))
    )
    (comp (ref "R134")
      (value "18K")
      (footprint "RESC2013X65N")
      (description "Resistor")
      (fields
        (field (name "MANUFACTURER_PART_NUMBER") "0805W8F1802T5E")
        (field (name "JLCPCB PART #") "C17506")
      )
      (libsource (lib "AltiumLL") (part "0805W8F1802T5E"))
    )
    (comp (ref "R135")
      (value "100R")
      (footprint "RESC2013X65N")
      (description "Resistor")
      (fields
        (field (name "MANUFACTURER_PART_NUMBER") "0805W8F1000T5E")
        (field (name "JLCPCB PART #") "C17408")
      )
      (libsource (lib "AltiumLL") (part "0805W8F1000T5E"))
    )
    (comp (ref "R136")
      (value "IND")
      (footprint "6-0805_N")
      (description "Resistor")
      (fields (field (name "Comment") "Res1") (field (name "PUBLISHER") "Altium Limited"))
      (libsource (lib "Miscellaneous Devices") (part "Res1"))
    )
    (comp (ref "R137")
      (value "1K")
      (footprint "RESC2012X50N")
      (description "Resistor")
      (fields
        (field (name "MANUFACTURER_PART_NUMBER") "0805W8F1001T5E")
        (field (name "JLCPCB PART #") "C17513")
      )
      (libsource (lib "") (part "0805W8F1001T5E_1"))
    )
    (comp (ref "R138")
      (value "180R")
      (footprint "RESC2013X65N")
      (description "Resistor")
      (fields
        (field (name "MANUFACTURER_PART_NUMBER") "0805W8F1800T5E")
        (field (name "JLCPCB PART #") "C25270")
      )
      (libsource (lib "AltiumLL") (part "0805W8F1800T5E"))
    )
    (comp (ref "R139")
      (value "IND")
      (footprint "6-0805_N")
      (description "Resistor")
      (fields (field (name "Comment") "Res1") (field (name "PUBLISHER") "Altium Limited"))
      (libsource (lib "Miscellaneous Devices") (part "Res1"))
    )
    (comp (ref "R140")
      (value "20K")
      (footprint "RESC2012X50N")
      (description "Resistor")
      (fields
        (field (name "MANUFACTURER_PART_NUMBER") "0805W8F2002T5E")
        (field (name "JLCPCB PART #") "C4328")
      )
      (libsource (lib "AltiumLL") (part "0805W8F2002T5E"))
    )
    (comp (ref "R141")
      (value "390R")
      (footprint "RESC2013X65N")
      (description "Resistor")
      (fields
        (field (name "MANUFACTURER_PART_NUMBER") "0805W8F3900T5E")
        (field (name "JLCPCB PART #") "C17655")
      )
      (libsource (lib "AltiumLL") (part "0805W8F3900T5E"))
    )
    (comp (ref "R142")
      (value "1K")
      (footprint "RESC2012X50N")
      (description "Resistor")
      (fields
        (field (name "MANUFACTURER_PART_NUMBER") "0805W8F1001T5E")
        (field (name "JLCPCB PART #") "C17513")
      )
      (libsource (lib "") (part "0805W8F1001T5E_1"))
    )
    (comp (ref "R143")
      (value "100R")
      (footprint "RESC2013X65N")
      (description "Resistor")
      (fields
        (field (name "MANUFACTURER_PART_NUMBER") "0805W8F1000T5E")
        (field (name "JLCPCB PART #") "C17408")
      )
      (libsource (lib "AltiumLL") (part "0805W8F1000T5E"))
    )
    (comp (ref "R144")
      (value "100R")
      (footprint "RESC2013X65N")
      (description "Resistor")
      (fields
        (field (name "MANUFACTURER_PART_NUMBER") "0805W8F1000T5E")
        (field (name "JLCPCB PART #") "C17408")
      )
      (libsource (lib "AltiumLL") (part "0805W8F1000T5E"))
    )
    (comp (ref "R145")
      (value "47R")
      (footprint "RESC2013X65N")
      (description "Resistor")
      (fields
        (field (name "MANUFACTURER_PART_NUMBER") "0805W8F470JT5E")
        (field (name "JLCPCB PART #") "C17714")
      )
      (libsource (lib "AltiumLL") (part "0805W8F470JT5E"))
    )
    (comp (ref "R146")
      (value "47R")
      (footprint "RESC2013X65N")
      (description "Resistor")
      (fields
        (field (name "MANUFACTURER_PART_NUMBER") "0805W8F470JT5E")
        (field (name "JLCPCB PART #") "C17714")
      )
      (libsource (lib "AltiumLL") (part "0805W8F470JT5E"))
    )
    (comp (ref "R147")
      (value "1K")
      (footprint "RESC2012X50N")
      (description "Resistor")
      (fields
        (field (name "MANUFACTURER_PART_NUMBER") "0805W8F1001T5E")
        (field (name "JLCPCB PART #") "C17513")
      )
      (libsource (lib "") (part "0805W8F1001T5E_1"))
    )
    (comp (ref "R148")
      (value "1K")
      (footprint "RESC2012X50N")
      (description "Resistor")
      (fields
        (field (name "MANUFACTURER_PART_NUMBER") "0805W8F1001T5E")
        (field (name "JLCPCB PART #") "C17513")
      )
      (libsource (lib "") (part "0805W8F1001T5E_2"))
    )
    (comp (ref "U1")
      (value "DS3231S#")
      (footprint "SOIC127P1032X265-16N")
      (description "Undefined or Miscellaneous")
      (fields (field (name "MOUSER PART NUMBER") "700-DS3231S#") (field (name "JLCPCB PART #") "C2651514"))
      (libsource (lib "AltiumLL") (part "DS3231S#"))
    )
    (comp (ref "U2")
      (value "TL084IDR")
      (footprint "SOIC127P600X175-14N")
      (description "Integrated Circuit Operational Amplifier")
      (fields (field (name "MOUSER PART NUMBER") "595-TL084IDR") (field (name "JLCPCB PART #") "C12601"))
      (libsource (lib "AltiumLL") (part "TL084IDR"))
    )
    (comp (ref "U3")
      (value "TL084IDR")
      (footprint "SOIC127P600X175-14N")
      (description "Integrated Circuit Operational Amplifier")
      (fields (field (name "MOUSER PART NUMBER") "595-TL084IDR") (field (name "JLCPCB PART #") "C12601"))
      (libsource (lib "AltiumLL") (part "TL084IDR"))
    )
    (comp (ref "U4")
      (value "TL084IDR")
      (footprint "SOIC127P600X175-14N")
      (description "Integrated Circuit Operational Amplifier")
      (fields (field (name "MOUSER PART NUMBER") "595-TL084IDR") (field (name "JLCPCB PART #") "C12601"))
      (libsource (lib "AltiumLL") (part "TL084IDR"))
    )
    (comp (ref "Y1")
      (value "ECS-150-S-4X")
      (footprint "ECS150S4X")
      (description "Crystal or Oscillator")
      (fields (field (name "MOUSER PART NUMBER") "520-HCU1500-SX"))
      (libsource (lib "AltiumLL") (part "ECS-150-S-4X"))
    )
  )
  (nets
    (net (code "1") (name "+2.5V") (class "Default")
      (node (ref "C36") (pin "1") (pinfunction "1_1") (pintype "passive"))
      (node (ref "C57") (pin "1") (pinfunction "1_1") (pintype "passive"))
      (node (ref "C78") (pin "1") (pinfunction "1_1") (pintype "passive"))
      (node (ref "IC4") (pin "1") (pinfunction "VDD_1") (pintype "power_in"))
      (node (ref "IC4") (pin "18") (pinfunction "EN_18") (pintype "input"))
      (node (ref "IC6") (pin "1") (pinfunction "VDD_1") (pintype "power_in"))
      (node (ref "IC6") (pin "18") (pinfunction "EN_18") (pintype "input"))
      (node (ref "IC8") (pin "1") (pinfunction "VDD_1") (pintype "power_in"))
      (node (ref "IC8") (pin "18") (pinfunction "EN_18") (pintype "input"))
      (node (ref "P1") (pin "6") (pinfunction "6_6") (pintype "passive"))
      (node (ref "Q11") (pin "1") (pinfunction "G_1") (pintype "passive"))
      (node (ref "Q12") (pin "1") (pinfunction "G_1") (pintype "passive"))
      (node (ref "Q6") (pin "1") (pinfunction "G_1") (pintype "passive"))
      (node (ref "Q7") (pin "1") (pinfunction "G_1") (pintype "passive"))
      (node (ref "R20") (pin "1") (pinfunction "1_1") (pintype "passive"))
      (node (ref "R22") (pin "1") (pinfunction "1_1") (pintype "passive"))
      (node (ref "R38") (pin "1") (pinfunction "1_1") (pintype "passive"))
      (node (ref "R40") (pin "1") (pinfunction "1_1") (pintype "passive"))
    )
    (net (code "2") (name "+3.3V") (class "Default")
      (node (ref "C15") (pin "1") (pinfunction "1_1") (pintype "passive"))
      (node (ref "C16") (pin "1") (pinfunction "1_1") (pintype "passive"))
      (node (ref "IC3") (pin "1") (pinfunction "VDD_1") (pintype "passive"))
      (node (ref "J2") (pin "1") (pinfunction "1_1") (pintype "passive"))
      (node (ref "J2") (pin "17") (pinfunction "17_17") (pintype "passive"))
      (node (ref "P1") (pin "4") (pinfunction "4_4") (pintype "passive"))
      (node (ref "Q1") (pin "1") (pinfunction "G_1") (pintype "passive"))
      (node (ref "Q10") (pin "1") (pinfunction "G_1") (pintype "passive"))
      (node (ref "Q13") (pin "1") (pinfunction "G_1") (pintype "passive"))
      (node (ref "Q2") (pin "1") (pinfunction "G_1") (pintype "passive"))
      (node (ref "Q3") (pin "1") (pinfunction "G_1") (pintype "passive"))
      (node (ref "Q4") (pin "1") (pinfunction "G_1") (pintype "passive"))
      (node (ref "Q5") (pin "1") (pinfunction "G_1") (pintype "passive"))
      (node (ref "Q8") (pin "1") (pinfunction "G_1") (pintype "passive"))
      (node (ref "Q9") (pin "1") (pinfunction "G_1") (pintype "passive"))
      (node (ref "R11") (pin "1") (pinfunction "1_1") (pintype "passive"))
      (node (ref "R14") (pin "1") (pinfunction "1_1") (pintype "passive"))
      (node (ref "R16") (pin "1") (pinfunction "1_1") (pintype "passive"))
      (node (ref "R24") (pin "2") (pinfunction "2_2") (pintype "passive"))
      (node (ref "R25") (pin "1") (pinfunction "1_1") (pintype "passive"))
      (node (ref "R34") (pin "1") (pinfunction "1_1") (pintype "passive"))
      (node (ref "R36") (pin "1") (pinfunction "1_1") (pintype "passive"))
      (node (ref "R4") (pin "1") (pinfunction "1_1") (pintype "passive"))
      (node (ref "R43") (pin "1") (pinfunction "1_1") (pintype "passive"))
      (node (ref "R8") (pin "1") (pinfunction "1_1") (pintype "passive"))
    )
    (net (code "3") (name "+5V") (class "Default")
      (node (ref "C1") (pin "1") (pinfunction "1_1") (pintype "passive"))
      (node (ref "C12") (pin "1") (pinfunction "1_1") (pintype "passive"))
      (node (ref "C13") (pin "1") (pinfunction "1_1") (pintype "passive"))
      (node (ref "C14") (pin "1") (pinfunction "1_1") (pintype "passive"))
      (node (ref "C19") (pin "1") (pinfunction "1_1") (pintype "passive"))
      (node (ref "C2") (pin "1") (pinfunction "1_1") (pintype "passive"))
      (node (ref "C20") (pin "1") (pinfunction "1_1") (pintype "passive"))
      (node (ref "C21") (pin "1") (pinfunction "1_1") (pintype "passive"))
      (node (ref "C3") (pin "1") (pinfunction "1_1") (pintype "passive"))
      (node (ref "D1") (pin "2") (pinfunction "A_2") (pintype "passive"))
      (node (ref "GPS1") (pin "1") (pinfunction "VIN_1") (pintype "power_in"))
      (node (ref "IC1") (pin "10") (pinfunction "IN1_10") (pintype "passive"))
      (node (ref "IC1") (pin "4") (pinfunction "EN2_4") (pintype "passive"))
      (node (ref "IC1") (pin "5") (pinfunction "IN2_5") (pintype "passive"))
      (node (ref "IC1") (pin "9") (pinfunction "EN1_9") (pintype "passive"))
      (node (ref "IC2") (pin "11") (pinfunction "VDD_1_11") (pintype "passive"))
      (node (ref "IC2") (pin "21") (pinfunction "VDD_2_21") (pintype "passive"))
      (node (ref "IC2") (pin "32") (pinfunction "VDD_3_32") (pintype "passive"))
      (node (ref "P1") (pin "3") (pinfunction "3_3") (pintype "passive"))
      (node (ref "P5") (pin "2") (pinfunction "2_2") (pintype "passive"))
      (node (ref "R10") (pin "1") (pinfunction "1_1") (pintype "passive"))
      (node (ref "R12") (pin "1") (pinfunction "1_1") (pintype "passive"))
      (node (ref "R15") (pin "1") (pinfunction "1_1") (pintype "passive"))
      (node (ref "R17") (pin "1") (pinfunction "1_1") (pintype "passive"))
      (node (ref "R2") (pin "2") (pinfunction "2_2") (pintype "passive"))
      (node (ref "R21") (pin "1") (pinfunction "1_1") (pintype "passive"))
      (node (ref "R23") (pin "1") (pinfunction "1_1") (pintype "passive"))
      (node (ref "R26") (pin "1") (pinfunction "1_1") (pintype "passive"))
      (node (ref "R3") (pin "2") (pinfunction "2_2") (pintype "passive"))
      (node (ref "R35") (pin "1") (pinfunction "1_1") (pintype "passive"))
      (node (ref "R37") (pin "1") (pinfunction "1_1") (pintype "passive"))
      (node (ref "R39") (pin "1") (pinfunction "1_1") (pintype "passive"))
      (node (ref "R41") (pin "1") (pinfunction "1_1") (pintype "passive"))
      (node (ref "R44") (pin "1") (pinfunction "1_1") (pintype "passive"))
      (node (ref "R5") (pin "1") (pinfunction "1_1") (pintype "passive"))
      (node (ref "R7") (pin "2") (pinfunction "2_2") (pintype "passive"))
      (node (ref "R9") (pin "1") (pinfunction "1_1") (pintype "passive"))
      (node (ref "U1") (pin "2") (pinfunction "VCC_2") (pintype "passive"))
    )
    (net (code "4") (name "+5V_AVDD") (class "Default")
      (node (ref "C22") (pin "1") (pinfunction "1_1") (pintype "passive"))
      (node (ref "C23") (pin "1") (pinfunction "1_1") (pintype "passive"))
      (node (ref "C24") (pin "1") (pinfunction "1_1") (pintype "passive"))
      (node (ref "IC2") (pin "40") (pinfunction "AVDD_40") (pintype "passive"))
      (node (ref "R10") (pin "2") (pinfunction "2_2") (pintype "passive"))
    )
    (net (code "5") (name "+5V_CONM") (class "Default")
      (node (ref "C17") (pin "1") (pinfunction "1_1") (pintype "passive"))
      (node (ref "C18") (pin "1") (pinfunction "1_1") (pintype "passive"))
      (node (ref "J2") (pin "2") (pinfunction "2_2") (pintype "passive"))
      (node (ref "J2") (pin "4") (pinfunction "4_4") (pintype "passive"))
      (node (ref "P1") (pin "2") (pinfunction "2_2") (pintype "passive"))
    )
    (net (code "6") (name "+8V") (class "Default")
      (node (ref "P2") (pin "4") (pinfunction "4_4") (pintype "passive"))
      (node (ref "R111") (pin "1") (pinfunction "1_1") (pintype "passive"))
      (node (ref "R115") (pin "1") (pinfunction "1_1") (pintype "passive"))
      (node (ref "R145") (pin "1") (pinfunction "1_1") (pintype "passive"))
      (node (ref "R47") (pin "1") (pinfunction "1_1") (pintype "passive"))
      (node (ref "R77") (pin "1") (pinfunction "1_1") (pintype "passive"))
      (node (ref "R81") (pin "1") (pinfunction "1_1") (pintype "passive"))
    )
    (net (code "7") (name "+8V_INA_CH1") (class "Default")
      (node (ref "C42") (pin "1") (pinfunction "1_1") (pintype "passive"))
      (node (ref "C43") (pin "1") (pinfunction "1_1") (pintype "passive"))
      (node (ref "C44") (pin "1") (pinfunction "1_1") (pintype "passive"))
      (node (ref "IC5") (pin "7") (pinfunction "V+_7") (pintype "passive"))
      (node (ref "R77") (pin "2") (pinfunction "2_2") (pintype "passive"))
    )
    (net (code "8") (name "+8V_INA_CH2") (class "Default")
      (node (ref "C63") (pin "1") (pinfunction "1_1") (pintype "passive"))
      (node (ref "C64") (pin "1") (pinfunction "1_1") (pintype "passive"))
      (node (ref "C65") (pin "1") (pinfunction "1_1") (pintype "passive"))
      (node (ref "IC7") (pin "7") (pinfunction "V+_7") (pintype "passive"))
      (node (ref "R111") (pin "2") (pinfunction "2_2") (pintype "passive"))
    )
    (net (code "9") (name "+8V_INA_CH3") (class "Default")
      (node (ref "C84") (pin "1") (pinfunction "1_1") (pintype "passive"))
      (node (ref "C85") (pin "1") (pinfunction "1_1") (pintype "passive"))
      (node (ref "C86") (pin "1") (pinfunction "1_1") (pintype "passive"))
      (node (ref "IC9") (pin "7") (pinfunction "V+_7") (pintype "passive"))
      (node (ref "R145") (pin "2") (pinfunction "2_2") (pintype "passive"))
    )
    (net (code "10") (name "+8V_TL_CH1") (class "Default")
      (node (ref "C29") (pin "1") (pinfunction "1_1") (pintype "passive"))
      (node (ref "C30") (pin "1") (pinfunction "1_1") (pintype "passive"))
      (node (ref "C31") (pin "1") (pinfunction "1_1") (pintype "passive"))
      (node (ref "R47") (pin "2") (pinfunction "2_2") (pintype "passive"))
      (node (ref "U2") (pin "4") (pinfunction "VCC+_4") (pintype "power_in"))
    )
    (net (code "11") (name "+8V_TL_CH2") (class "Default")
      (node (ref "C50") (pin "1") (pinfunction "1_1") (pintype "passive"))
      (node (ref "C51") (pin "1") (pinfunction "1_1") (pintype "passive"))
      (node (ref "C52") (pin "1") (pinfunction "1_1") (pintype "passive"))
      (node (ref "R81") (pin "2") (pinfunction "2_2") (pintype "passive"))
      (node (ref "U3") (pin "4") (pinfunction "VCC+_4") (pintype "power_in"))
    )
    (net (code "12") (name "+8V_TL_CH3") (class "Default")
      (node (ref "C71") (pin "1") (pinfunction "1_1") (pintype "passive"))
      (node (ref "C72") (pin "1") (pinfunction "1_1") (pintype "passive"))
      (node (ref "C73") (pin "1") (pinfunction "1_1") (pintype "passive"))
      (node (ref "R115") (pin "2") (pinfunction "2_2") (pintype "passive"))
      (node (ref "U4") (pin "4") (pinfunction "VCC+_4") (pintype "power_in"))
    )
    (net (code "13") (name "+12V") (class "Default")
      (node (ref "C7") (pin "1") (pinfunction "1_1") (pintype "passive"))
      (node (ref "J1") (pin "14") (pinfunction "14_14") (pintype "passive"))
      (node (ref "P2") (pin "1") (pinfunction "1_1") (pintype "passive"))
      (node (ref "P4") (pin "1") (pinfunction "1_1") (pintype "passive"))
    )
    (net (code "14") (name "-2.5V") (class "Default")
      (node (ref "C37") (pin "1") (pinfunction "1_1") (pintype "passive"))
      (node (ref "C58") (pin "1") (pinfunction "1_1") (pintype "passive"))
      (node (ref "C79") (pin "1") (pinfunction "1_1") (pintype "passive"))
      (node (ref "IC4") (pin "27") (pinfunction "VSS_27") (pintype "power_in"))
      (node (ref "IC6") (pin "27") (pinfunction "VSS_27") (pintype "power_in"))
      (node (ref "IC8") (pin "27") (pinfunction "VSS_27") (pintype "power_in"))
      (node (ref "P1") (pin "7") (pinfunction "7_7") (pintype "passive"))
    )
    (net (code "15") (name "-8V") (class "Default")
      (node (ref "P2") (pin "5") (pinfunction "5_5") (pintype "passive"))
      (node (ref "R112") (pin "1") (pinfunction "1_1") (pintype "passive"))
      (node (ref "R116") (pin "1") (pinfunction "1_1") (pintype "passive"))
      (node (ref "R146") (pin "1") (pinfunction "1_1") (pintype "passive"))
      (node (ref "R48") (pin "1") (pinfunction "1_1") (pintype "passive"))
      (node (ref "R78") (pin "1") (pinfunction "1_1") (pintype "passive"))
      (node (ref "R82") (pin "1") (pinfunction "1_1") (pintype "passive"))
    )
    (net (code "16") (name "-8V_INA_CH1") (class "Default")
      (node (ref "C45") (pin "1") (pinfunction "1_1") (pintype "passive"))
      (node (ref "C46") (pin "1") (pinfunction "1_1") (pintype "passive"))
      (node (ref "C47") (pin "1") (pinfunction "1_1") (pintype "passive"))
      (node (ref "IC5") (pin "4") (pinfunction "V-_4") (pintype "passive"))
      (node (ref "R78") (pin "2") (pinfunction "2_2") (pintype "passive"))
    )
    (net (code "17") (name "-8V_INA_CH2") (class "Default")
      (node (ref "C66") (pin "1") (pinfunction "1_1") (pintype "passive"))
      (node (ref "C67") (pin "1") (pinfunction "1_1") (pintype "passive"))
      (node (ref "C68") (pin "1") (pinfunction "1_1") (pintype "passive"))
      (node (ref "IC7") (pin "4") (pinfunction "V-_4") (pintype "passive"))
      (node (ref "R112") (pin "2") (pinfunction "2_2") (pintype "passive"))
    )
    (net (code "18") (name "-8V_INA_CH3") (class "Default")
      (node (ref "C87") (pin "1") (pinfunction "1_1") (pintype "passive"))
      (node (ref "C88") (pin "1") (pinfunction "1_1") (pintype "passive"))
      (node (ref "C89") (pin "1") (pinfunction "1_1") (pintype "passive"))
      (node (ref "IC9") (pin "4") (pinfunction "V-_4") (pintype "passive"))
      (node (ref "R146") (pin "2") (pinfunction "2_2") (pintype "passive"))
    )
    (net (code "19") (name "-8V_TL_CH1") (class "Default")
      (node (ref "C32") (pin "1") (pinfunction "1_1") (pintype "passive"))
      (node (ref "C33") (pin "1") (pinfunction "1_1") (pintype "passive"))
      (node (ref "C34") (pin "1") (pinfunction "1_1") (pintype "passive"))
      (node (ref "R48") (pin "2") (pinfunction "2_2") (pintype "passive"))
      (node (ref "U2") (pin "11") (pinfunction "VCC-_11") (pintype "power_in"))
    )
    (net (code "20") (name "-8V_TL_CH2") (class "Default")
      (node (ref "C53") (pin "1") (pinfunction "1_1") (pintype "passive"))
      (node (ref "C54") (pin "1") (pinfunction "1_1") (pintype "passive"))
      (node (ref "C55") (pin "1") (pinfunction "1_1") (pintype "passive"))
      (node (ref "R82") (pin "2") (pinfunction "2_2") (pintype "passive"))
      (node (ref "U3") (pin "11") (pinfunction "VCC-_11") (pintype "power_in"))
    )
    (net (code "21") (name "-8V_TL_CH3") (class "Default")
      (node (ref "C74") (pin "1") (pinfunction "1_1") (pintype "passive"))
      (node (ref "C75") (pin "1") (pinfunction "1_1") (pintype "passive"))
      (node (ref "C76") (pin "1") (pinfunction "1_1") (pintype "passive"))
      (node (ref "R116") (pin "2") (pinfunction "2_2") (pintype "passive"))
      (node (ref "U4") (pin "11") (pinfunction "VCC-_11") (pintype "power_in"))
    )
    (net (code "22") (name "-12V") (class "Default")
      (node (ref "C8") (pin "1") (pinfunction "1_1") (pintype "passive"))
      (node (ref "J1") (pin "15") (pinfunction "15_15") (pintype "passive"))
      (node (ref "P2") (pin "2") (pinfunction "2_2") (pintype "passive"))
      (node (ref "P4") (pin "3") (pinfunction "3_3") (pintype "passive"))
    )
    (net (code "23") (name "A0_2.5V") (class "Default")
      (node (ref "IC4") (pin "17") (pinfunction "A0_17") (pintype "input"))
      (node (ref "IC6") (pin "17") (pinfunction "A0_17") (pintype "input"))
      (node (ref "IC8") (pin "17") (pinfunction "A0_17") (pintype "input"))
      (node (ref "Q6") (pin "2") (pinfunction "S_2") (pintype "passive"))
      (node (ref "R20") (pin "2") (pinfunction "2_2") (pintype "passive"))
    )
    (net (code "24") (name "A0_5V") (class "Default")
      (node (ref "IC2") (pin "5") (pinfunction "AN3/CN5/RB3_5") (pintype "passive"))
      (node (ref "Q6") (pin "3") (pinfunction "D_3") (pintype "passive"))
      (node (ref "R21") (pin "2") (pinfunction "2_2") (pintype "passive"))
    )
    (net (code "25") (name "A1_2.5V") (class "Default")
      (node (ref "IC4") (pin "16") (pinfunction "A1_16") (pintype "input"))
      (node (ref "IC6") (pin "16") (pinfunction "A1_16") (pintype "input"))
      (node (ref "IC8") (pin "16") (pinfunction "A1_16") (pintype "input"))
      (node (ref "Q11") (pin "2") (pinfunction "S_2") (pintype "passive"))
      (node (ref "R38") (pin "2") (pinfunction "2_2") (pintype "passive"))
    )
    (net (code "26") (name "A1_5V") (class "Default")
      (node (ref "IC2") (pin "6") (pinfunction "AN4/IC7/CN6/RB4_6") (pintype "passive"))
      (node (ref "Q11") (pin "3") (pinfunction "D_3") (pintype "passive"))
      (node (ref "R39") (pin "2") (pinfunction "2_2") (pintype "passive"))
    )
    (net (code "27") (name "A2_2.5V") (class "Default")
      (node (ref "IC4") (pin "15") (pinfunction "A2_15") (pintype "input"))
      (node (ref "IC6") (pin "15") (pinfunction "A2_15") (pintype "input"))
      (node (ref "IC8") (pin "15") (pinfunction "A2_15") (pintype "input"))
      (node (ref "Q7") (pin "2") (pinfunction "S_2") (pintype "passive"))
      (node (ref "R22") (pin "2") (pinfunction "2_2") (pintype "passive"))
    )
    (net (code "28") (name "A2_5V") (class "Default")
      (node (ref "IC2") (pin "7") (pinfunction "AN5/IC8/CN7/RB5_7") (pintype "passive"))
      (node (ref "Q7") (pin "3") (pinfunction "D_3") (pintype "passive"))
      (node (ref "R23") (pin "2") (pinfunction "2_2") (pintype "passive"))
    )
    (net (code "29") (name "A3_2.5V") (class "Default")
      (node (ref "IC4") (pin "14") (pinfunction "A3_14") (pintype "input"))
      (node (ref "IC6") (pin "14") (pinfunction "A3_14") (pintype "input"))
      (node (ref "IC8") (pin "14") (pinfunction "A3_14") (pintype "input"))
      (node (ref "Q12") (pin "2") (pinfunction "S_2") (pintype "passive"))
      (node (ref "R40") (pin "2") (pinfunction "2_2") (pintype "passive"))
    )
    (net (code "30") (name "CH1+") (class "Default")
      (node (ref "J1") (pin "8") (pinfunction "8_8") (pintype "passive"))
      (node (ref "P3") (pin "1") (pinfunction "1_1") (pintype "passive"))
      (node (ref "R49") (pin "1") (pinfunction "1_1") (pintype "passive"))
      (node (ref "R56") (pin "2") (pinfunction "2_2") (pintype "passive"))
    )
    (net (code "31") (name "CH1+_ACON") (class "Default")
      (node (ref "C38") (pin "2") (pinfunction "2_2") (pintype "passive"))
      (node (ref "IC5") (pin "3") (pinfunction "V+IN_3") (pintype "passive"))
      (node (ref "R50") (pin "2") (pinfunction "2_2") (pintype "passive"))
    )
    (net (code "32") (name "CH1-") (class "Default")
      (node (ref "J1") (pin "9") (pinfunction "9_9") (pintype "passive"))
      (node (ref "P3") (pin "2") (pinfunction "2_2") (pintype "passive"))
      (node (ref "R72") (pin "1") (pinfunction "1_1") (pintype "passive"))
      (node (ref "R75") (pin "1") (pinfunction "1_1") (pintype "passive"))
    )
    (net (code "33") (name "CH1-_ACON") (class "Default")
      (node (ref "C38") (pin "1") (pinfunction "1_1") (pintype "passive"))
      (node (ref "IC5") (pin "2") (pinfunction "V-IN_2") (pintype "passive"))
      (node (ref "R76") (pin "2") (pinfunction "2_2") (pintype "passive"))
    )
    (net (code "34") (name "CH2+") (class "Default")
      (node (ref "J1") (pin "5") (pinfunction "5_5") (pintype "passive"))
      (node (ref "P3") (pin "3") (pinfunction "3_3") (pintype "passive"))
      (node (ref "R83") (pin "1") (pinfunction "1_1") (pintype "passive"))
      (node (ref "R90") (pin "2") (pinfunction "2_2") (pintype "passive"))
    )
    (net (code "35") (name "CH2+_ACON") (class "Default")
      (node (ref "C59") (pin "2") (pinfunction "2_2") (pintype "passive"))
      (node (ref "IC7") (pin "3") (pinfunction "V+IN_3") (pintype "passive"))
      (node (ref "R84") (pin "2") (pinfunction "2_2") (pintype "passive"))
    )
    (net (code "36") (name "CH2-") (class "Default")
      (node (ref "J1") (pin "6") (pinfunction "6_6") (pintype "passive"))
      (node (ref "P3") (pin "4") (pinfunction "4_4") (pintype "passive"))
      (node (ref "R106") (pin "1") (pinfunction "1_1") (pintype "passive"))
      (node (ref "R109") (pin "1") (pinfunction "1_1") (pintype "passive"))
    )
    (net (code "37") (name "CH2-_ACON") (class "Default")
      (node (ref "C59") (pin "1") (pinfunction "1_1") (pintype "passive"))
      (node (ref "IC7") (pin "2") (pinfunction "V-IN_2") (pintype "passive"))
      (node (ref "R110") (pin "2") (pinfunction "2_2") (pintype "passive"))
    )
    (net (code "38") (name "CH3+") (class "Default")
      (node (ref "J1") (pin "2") (pinfunction "2_2") (pintype "passive"))
      (node (ref "P3") (pin "5") (pinfunction "5_5") (pintype "passive"))
      (node (ref "R117") (pin "1") (pinfunction "1_1") (pintype "passive"))
      (node (ref "R124") (pin "2") (pinfunction "2_2") (pintype "passive"))
    )
    (net (code "39") (name "CH3+_ACON") (class "Default")
      (node (ref "C80") (pin "2") (pinfunction "2_2") (pintype "passive"))
      (node (ref "IC9") (pin "3") (pinfunction "V+IN_3") (pintype "passive"))
      (node (ref "R118") (pin "2") (pinfunction "2_2") (pintype "passive"))
    )
    (net (code "40") (name "CH3-") (class "Default")
      (node (ref "J1") (pin "3") (pinfunction "3_3") (pintype "passive"))
      (node (ref "P3") (pin "6") (pinfunction "6_6") (pintype "passive"))
      (node (ref "R140") (pin "1") (pinfunction "1_1") (pintype "passive"))
      (node (ref "R143") (pin "1") (pinfunction "1_1") (pintype "passive"))
    )
    (net (code "41") (name "CH3-_ACON") (class "Default")
      (node (ref "C80") (pin "1") (pinfunction "1_1") (pintype "passive"))
      (node (ref "IC9") (pin "2") (pinfunction "V-IN_2") (pintype "passive"))
      (node (ref "R144") (pin "2") (pinfunction "2_2") (pintype "passive"))
    )
    (net (code "42") (name "CS_RPI_3.3V") (class "Default")
      (node (ref "Q10") (pin "2") (pinfunction "S_2") (pintype "passive"))
      (node (ref "R32") (pin "2") (pinfunction "2_2") (pintype "passive"))
      (node (ref "R36") (pin "2") (pinfunction "2_2") (pintype "passive"))
    )
    (net (code "43") (name "CS_RPI_5V") (class "Default")
      (node (ref "IC2") (pin "4") (pinfunction "AN2/~{SS1}/LVDIN/CN4/RB2_4") (pintype "passive"))
      (node (ref "Q10") (pin "3") (pinfunction "D_3") (pintype "passive"))
      (node (ref "R37") (pin "2") (pinfunction "2_2") (pintype "passive"))
    )
    (net (code "44") (name "EN_GPS") (class "Default")
      (node (ref "GPS1") (pin "7") (pinfunction "EN_7") (pintype "input"))
      (node (ref "IC2") (pin "19") (pinfunction "OC4/RD3_19") (pintype "passive"))
    )
    (net (code "45") (name "GND") (class "Default")
      (node (ref "BT1") (pin "2") (pinfunction "2_2") (pintype "passive"))
      (node (ref "C1") (pin "2") (pinfunction "2_2") (pintype "passive"))
      (node (ref "C10") (pin "2") (pinfunction "2_2") (pintype "passive"))
      (node (ref "C11") (pin "2") (pinfunction "2_2") (pintype "passive"))
      (node (ref "C12") (pin "2") (pinfunction "2_2") (pintype "passive"))
      (node (ref "C13") (pin "2") (pinfunction "2_2") (pintype "passive"))
      (node (ref "C14") (pin "2") (pinfunction "2_2") (pintype "passive"))
      (node (ref "C15") (pin "2") (pinfunction "2_2") (pintype "passive"))
      (node (ref "C16") (pin "2") (pinfunction "2_2") (pintype "passive"))
      (node (ref "C17") (pin "2") (pinfunction "2_2") (pintype "passive"))
      (node (ref "C18") (pin "2") (pinfunction "2_2") (pintype "passive"))
      (node (ref "C19") (pin "2") (pinfunction "2_2") (pintype "passive"))
      (node (ref "C2") (pin "2") (pinfunction "2_2") (pintype "passive"))
      (node (ref "C20") (pin "2") (pinfunction "2_2") (pintype "passive"))
      (node (ref "C21") (pin "2") (pinfunction "2_2") (pintype "passive"))
      (node (ref "C22") (pin "2") (pinfunction "2_2") (pintype "passive"))
      (node (ref "C23") (pin "2") (pinfunction "2_2") (pintype "passive"))
      (node (ref "C24") (pin "2") (pinfunction "2_2") (pintype "passive"))
      (node (ref "C25") (pin "1") (pinfunction "1_1") (pintype "passive"))
      (node (ref "C26") (pin "1") (pinfunction "1_1") (pintype "passive"))
      (node (ref "C29") (pin "2") (pinfunction "2_2") (pintype "passive"))
      (node (ref "C3") (pin "2") (pinfunction "2_2") (pintype "passive"))
      (node (ref "C30") (pin "2") (pinfunction "2_2") (pintype "passive"))
      (node (ref "C31") (pin "2") (pinfunction "2_2") (pintype "passive"))
      (node (ref "C32") (pin "2") (pinfunction "2_2") (pintype "passive"))
      (node (ref "C33") (pin "2") (pinfunction "2_2") (pintype "passive"))
      (node (ref "C34") (pin "2") (pinfunction "2_2") (pintype "passive"))
      (node (ref "C35") (pin "1") (pinfunction "1_1") (pintype "passive"))
      (node (ref "C36") (pin "2") (pinfunction "2_2") (pintype "passive"))
      (node (ref "C37") (pin "2") (pinfunction "2_2") (pintype "passive"))
      (node (ref "C39") (pin "2") (pinfunction "2_2") (pintype "passive"))
      (node (ref "C4") (pin "2") (pinfunction "2_2") (pintype "passive"))
      (node (ref "C40") (pin "2") (pinfunction "2_2") (pintype "passive"))
      (node (ref "C41") (pin "2") (pinfunction "2_2") (pintype "passive"))
      (node (ref "C42") (pin "2") (pinfunction "2_2") (pintype "passive"))
      (node (ref "C43") (pin "2") (pinfunction "2_2") (pintype "passive"))
      (node (ref "C44") (pin "2") (pinfunction "2_2") (pintype "passive"))
      (node (ref "C45") (pin "2") (pinfunction "2_2") (pintype "passive"))
      (node (ref "C46") (pin "2") (pinfunction "2_2") (pintype "passive"))
      (node (ref "C47") (pin "2") (pinfunction "2_2") (pintype "passive"))
      (node (ref "C5") (pin "2") (pinfunction "2_2") (pintype "passive"))
      (node (ref "C50") (pin "2") (pinfunction "2_2") (pintype "passive"))
      (node (ref "C51") (pin "2") (pinfunction "2_2") (pintype "passive"))
      (node (ref "C52") (pin "2") (pinfunction "2_2") (pintype "passive"))
      (node (ref "C53") (pin "2") (pinfunction "2_2") (pintype "passive"))
      (node (ref "C54") (pin "2") (pinfunction "2_2") (pintype "passive"))
      (node (ref "C55") (pin "2") (pinfunction "2_2") (pintype "passive"))
      (node (ref "C56") (pin "1") (pinfunction "1_1") (pintype "passive"))
      (node (ref "C57") (pin "2") (pinfunction "2_2") (pintype "passive"))
      (node (ref "C58") (pin "2") (pinfunction "2_2") (pintype "passive"))
      (node (ref "C6") (pin "2") (pinfunction "2_2") (pintype "passive"))
      (node (ref "C60") (pin "2") (pinfunction "2_2") (pintype "passive"))
      (node (ref "C61") (pin "2") (pinfunction "2_2") (pintype "passive"))
      (node (ref "C62") (pin "2") (pinfunction "2_2") (pintype "passive"))
      (node (ref "C63") (pin "2") (pinfunction "2_2") (pintype "passive"))
      (node (ref "C64") (pin "2") (pinfunction "2_2") (pintype "passive"))
      (node (ref "C65") (pin "2") (pinfunction "2_2") (pintype "passive"))
      (node (ref "C66") (pin "2") (pinfunction "2_2") (pintype "passive"))
      (node (ref "C67") (pin "2") (pinfunction "2_2") (pintype "passive"))
      (node (ref "C68") (pin "2") (pinfunction "2_2") (pintype "passive"))
      (node (ref "C7") (pin "2") (pinfunction "2_2") (pintype "passive"))
      (node (ref "C71") (pin "2") (pinfunction "2_2") (pintype "passive"))
      (node (ref "C72") (pin "2") (pinfunction "2_2") (pintype "passive"))
      (node (ref "C73") (pin "2") (pinfunction "2_2") (pintype "passive"))
      (node (ref "C74") (pin "2") (pinfunction "2_2") (pintype "passive"))
      (node (ref "C75") (pin "2") (pinfunction "2_2") (pintype "passive"))
      (node (ref "C76") (pin "2") (pinfunction "2_2") (pintype "passive"))
      (node (ref "C77") (pin "1") (pinfunction "1_1") (pintype "passive"))
      (node (ref "C78") (pin "2") (pinfunction "2_2") (pintype "passive"))
      (node (ref "C79") (pin "2") (pinfunction "2_2") (pintype "passive"))
      (node (ref "C8") (pin "2") (pinfunction "2_2") (pintype "passive"))
      (node (ref "C81") (pin "2") (pinfunction "2_2") (pintype "passive"))
      (node (ref "C82") (pin "2") (pinfunction "2_2") (pintype "passive"))
      (node (ref "C83") (pin "2") (pinfunction "2_2") (pintype "passive"))
      (node (ref "C84") (pin "2") (pinfunction "2_2") (pintype "passive"))
      (node (ref "C85") (pin "2") (pinfunction "2_2") (pintype "passive"))
      (node (ref "C86") (pin "2") (pinfunction "2_2") (pintype "passive"))
      (node (ref "C87") (pin "2") (pinfunction "2_2") (pintype "passive"))
      (node (ref "C88") (pin "2") (pinfunction "2_2") (pintype "passive"))
      (node (ref "C89") (pin "2") (pinfunction "2_2") (pintype "passive"))
      (node (ref "C9") (pin "2") (pinfunction "2_2") (pintype "passive"))
      (node (ref "D2") (pin "1") (pinfunction "K_1") (pintype "passive"))
      (node (ref "D3") (pin "1") (pinfunction "K_1") (pintype "passive"))
      (node (ref "D4") (pin "1") (pinfunction "K_1") (pintype "passive"))
      (node (ref "D5") (pin "1") (pinfunction "K_1") (pintype "passive"))
      (node (ref "GPS1") (pin "2") (pinfunction "GND_2") (pintype "power_in"))
      (node (ref "IC1") (pin "3") (pinfunction "GND_1_3") (pintype "passive"))
      (node (ref "IC1") (pin "8") (pinfunction "GND_2_8") (pintype "passive"))
      (node (ref "IC2") (pin "12") (pinfunction "VSS_1_12") (pintype "passive"))
      (node (ref "IC2") (pin "20") (pinfunction "VSS_2_20") (pintype "passive"))
      (node (ref "IC2") (pin "31") (pinfunction "VSS_3_31") (pintype "passive"))
      (node (ref "IC2") (pin "39") (pinfunction "AVSS_39") (pintype "passive"))
      (node (ref "IC3") (pin "4") (pinfunction "GND_4") (pintype "passive"))
      (node (ref "IC4") (pin "12") (pinfunction "GND_12") (pintype "power_in"))
      (node (ref "IC5") (pin "5") (pinfunction "REF_5") (pintype "passive"))
      (node (ref "IC6") (pin "12") (pinfunction "GND_12") (pintype "power_in"))
      (node (ref "IC7") (pin "5") (pinfunction "REF_5") (pintype "passive"))
      (node (ref "IC8") (pin "12") (pinfunction "GND_12") (pintype "power_in"))
      (node (ref "IC9") (pin "5") (pinfunction "REF_5") (pintype "passive"))
      (node (ref "J1") (pin "13") (pinfunction "13_13") (pintype "passive"))
      (node (ref "J1") (pin "16") (pinfunction "16_16") (pintype "passive"))
      (node (ref "J2") (pin "14") (pinfunction "14_14") (pintype "passive"))
      (node (ref "J2") (pin "20") (pinfunction "20_20") (pintype "passive"))
      (node (ref "J2") (pin "25") (pinfunction "25_25") (pintype "passive"))
      (node (ref "J2") (pin "30") (pinfunction "30_30") (pintype "passive"))
      (node (ref "J2") (pin "34") (pinfunction "34_34") (pintype "passive"))
      (node (ref "J2") (pin "39") (pinfunction "39_39") (pintype "passive"))
      (node (ref "J2") (pin "6") (pinfunction "6_6") (pintype "passive"))
      (node (ref "J2") (pin "9") (pinfunction "9_9") (pintype "passive"))
      (node (ref "P1") (pin "1") (pinfunction "1_1") (pintype "passive"))
      (node (ref "P1") (pin "5") (pinfunction "5_5") (pintype "passive"))
      (node (ref "P1") (pin "8") (pinfunction "8_8") (pintype "passive"))
      (node (ref "P2") (pin "3") (pinfunction "3_3") (pintype "passive"))
      (node (ref "P2") (pin "6") (pinfunction "6_6") (pintype "passive"))
      (node (ref "P4") (pin "2") (pinfunction "2_2") (pintype "passive"))
      (node (ref "P4") (pin "4") (pinfunction "4_4") (pintype "passive"))
      (node (ref "P5") (pin "3") (pinfunction "3_3") (pintype "passive"))
      (node (ref "R106") (pin "2") (pinfunction "2_2") (pintype "passive"))
      (node (ref "R114") (pin "1") (pinfunction "1_1") (pintype "passive"))
      (node (ref "R124") (pin "1") (pinfunction "1_1") (pintype "passive"))
      (node (ref "R140") (pin "2") (pinfunction "2_2") (pintype "passive"))
      (node (ref "R148") (pin "1") (pinfunction "1_1") (pintype "passive"))
      (node (ref "R18") (pin "1") (pinfunction "1_1") (pintype "passive"))
      (node (ref "R56") (pin "1") (pinfunction "1_1") (pintype "passive"))
      (node (ref "R72") (pin "2") (pinfunction "2_2") (pintype "passive"))
      (node (ref "R80") (pin "1") (pinfunction "1_1") (pintype "passive"))
      (node (ref "R90") (pin "1") (pinfunction "1_1") (pintype "passive"))
      (node (ref "U1") (pin "10") (pinfunction "N.C._6_10") (pintype "passive"))
      (node (ref "U1") (pin "11") (pinfunction "N.C._7_11") (pintype "passive"))
      (node (ref "U1") (pin "12") (pinfunction "N.C._8_12") (pintype "passive"))
      (node (ref "U1") (pin "13") (pinfunction "GND_13") (pintype "passive"))
      (node (ref "U1") (pin "5") (pinfunction "N.C._1_5") (pintype "passive"))
      (node (ref "U1") (pin "6") (pinfunction "N.C._2_6") (pintype "passive"))
      (node (ref "U1") (pin "7") (pinfunction "N.C._3_7") (pintype "passive"))
      (node (ref "U1") (pin "8") (pinfunction "N.C._4_8") (pintype "passive"))
      (node (ref "U1") (pin "9") (pinfunction "N.C._5_9") (pintype "passive"))
    )
    (net (code "46") (name "INT_FROM_PIC_3.3V") (class "Default")
      (node (ref "Q13") (pin "2") (pinfunction "S_2") (pintype "passive"))
      (node (ref "R27") (pin "1") (pinfunction "1_1") (pintype "passive"))
      (node (ref "R43") (pin "2") (pinfunction "2_2") (pintype "passive"))
    )
    (net (code "47") (name "INT_FROM_PIC_5V") (class "Default")
      (node (ref "IC2") (pin "29") (pinfunction "C1TX/RF1_29") (pintype "passive"))
      (node (ref "Q13") (pin "3") (pinfunction "D_3") (pintype "passive"))
      (node (ref "R44") (pin "2") (pinfunction "2_2") (pintype "passive"))
    )
    (net (code "48") (name "MCLR") (class "Default")
      (node (ref "IC2") (pin "1") (pinfunction "~{MCLR}_1") (pintype "passive"))
      (node (ref "P5") (pin "1") (pinfunction "1_1") (pintype "passive"))
      (node (ref "Q8") (pin "3") (pinfunction "D_3") (pintype "passive"))
      (node (ref "R13") (pin "1") (pinfunction "1_1") (pintype "passive"))
      (node (ref "R26") (pin "2") (pinfunction "2_2") (pintype "passive"))
    )
    (net (code "49") (name "MISO_RPI_3.3V") (class "Default")
      (node (ref "Q5") (pin "2") (pinfunction "S_2") (pintype "passive"))
      (node (ref "R16") (pin "2") (pinfunction "2_2") (pintype "passive"))
      (node (ref "R30") (pin "1") (pinfunction "1_1") (pintype "passive"))
    )
    (net (code "50") (name "MISO_RPI_5V") (class "Default")
      (node (ref "IC2") (pin "25") (pinfunction "EMUD3/U1TX/SDO1/SCL/RF3_25") (pintype "passive"))
      (node (ref "Q5") (pin "3") (pinfunction "D_3") (pintype "passive"))
      (node (ref "R17") (pin "2") (pinfunction "2_2") (pintype "passive"))
    )
    (net (code "51") (name "MOSI_RPI_3.3V") (class "Default")
      (node (ref "Q4") (pin "2") (pinfunction "S_2") (pintype "passive"))
      (node (ref "R14") (pin "2") (pinfunction "2_2") (pintype "passive"))
      (node (ref "R29") (pin "1") (pinfunction "1_1") (pintype "passive"))
    )
    (net (code "52") (name "MOSI_RPI_5V") (class "Default")
      (node (ref "IC2") (pin "26") (pinfunction "U1RX/SDI1/SDA/RF2_26") (pintype "passive"))
      (node (ref "Q4") (pin "3") (pinfunction "D_3") (pintype "passive"))
      (node (ref "R15") (pin "2") (pinfunction "2_2") (pintype "passive"))
    )
    (net (code "53") (name "Net-(C27-Pad1)") (class "Default")
      (node (ref "C27") (pin "1") (pinfunction "1_1") (pintype "passive"))
      (node (ref "R61") (pin "2") (pinfunction "2_2") (pintype "passive"))
      (node (ref "R62") (pin "1") (pinfunction "1_1") (pintype "passive"))
    )
    (net (code "54") (name "Net-(C28-Pad1)") (class "Default")
      (node (ref "C28") (pin "1") (pinfunction "1_1") (pintype "passive"))
      (node (ref "R65") (pin "2") (pinfunction "2_2") (pintype "passive"))
      (node (ref "R66") (pin "1") (pinfunction "1_1") (pintype "passive"))
    )
    (net (code "55") (name "Net-(C35-Pad2)") (class "Default")
      (node (ref "C35") (pin "2") (pinfunction "2_2") (pintype "passive"))
      (node (ref "R49") (pin "2") (pinfunction "2_2") (pintype "passive"))
      (node (ref "R50") (pin "1") (pinfunction "1_1") (pintype "passive"))
    )
    (net (code "56") (name "Net-(C39-Pad1)") (class "Default")
      (node (ref "C39") (pin "1") (pinfunction "1_1") (pintype "passive"))
      (node (ref "R75") (pin "2") (pinfunction "2_2") (pintype "passive"))
      (node (ref "R76") (pin "1") (pinfunction "1_1") (pintype "passive"))
    )
    (net (code "57") (name "Net-(C48-Pad1)") (class "Default")
      (node (ref "C48") (pin "1") (pinfunction "1_1") (pintype "passive"))
      (node (ref "R95") (pin "2") (pinfunction "2_2") (pintype "passive"))
      (node (ref "R96") (pin "1") (pinfunction "1_1") (pintype "passive"))
    )
    (net (code "58") (name "Net-(C49-Pad1)") (class "Default")
      (node (ref "C49") (pin "1") (pinfunction "1_1") (pintype "passive"))
      (node (ref "R100") (pin "1") (pinfunction "1_1") (pintype "passive"))
      (node (ref "R99") (pin "2") (pinfunction "2_2") (pintype "passive"))
    )
    (net (code "59") (name "Net-(C56-Pad2)") (class "Default")
      (node (ref "C56") (pin "2") (pinfunction "2_2") (pintype "passive"))
      (node (ref "R83") (pin "2") (pinfunction "2_2") (pintype "passive"))
      (node (ref "R84") (pin "1") (pinfunction "1_1") (pintype "passive"))
    )
    (net (code "60") (name "Net-(C60-Pad1)") (class "Default")
      (node (ref "C60") (pin "1") (pinfunction "1_1") (pintype "passive"))
      (node (ref "R109") (pin "2") (pinfunction "2_2") (pintype "passive"))
      (node (ref "R110") (pin "1") (pinfunction "1_1") (pintype "passive"))
    )
    (net (code "61") (name "Net-(C69-Pad1)") (class "Default")
      (node (ref "C69") (pin "1") (pinfunction "1_1") (pintype "passive"))
      (node (ref "R129") (pin "2") (pinfunction "2_2") (pintype "passive"))
      (node (ref "R130") (pin "1") (pinfunction "1_1") (pintype "passive"))
    )
    (net (code "62") (name "Net-(C70-Pad1)") (class "Default")
      (node (ref "C70") (pin "1") (pinfunction "1_1") (pintype "passive"))
      (node (ref "R133") (pin "2") (pinfunction "2_2") (pintype "passive"))
      (node (ref "R134") (pin "1") (pinfunction "1_1") (pintype "passive"))
    )
    (net (code "63") (name "Net-(C77-Pad2)") (class "Default")
      (node (ref "C77") (pin "2") (pinfunction "2_2") (pintype "passive"))
      (node (ref "R117") (pin "2") (pinfunction "2_2") (pintype "passive"))
      (node (ref "R118") (pin "1") (pinfunction "1_1") (pintype "passive"))
    )
    (net (code "64") (name "Net-(C81-Pad1)") (class "Default")
      (node (ref "C81") (pin "1") (pinfunction "1_1") (pintype "passive"))
      (node (ref "R143") (pin "2") (pinfunction "2_2") (pintype "passive"))
      (node (ref "R144") (pin "1") (pinfunction "1_1") (pintype "passive"))
    )
    (net (code "65") (name "Net-(D1-K)") (class "Default")
      (node (ref "D1") (pin "1") (pinfunction "K_1") (pintype "passive"))
      (node (ref "R13") (pin "2") (pinfunction "2_2") (pintype "passive"))
    )
    (net (code "66") (name "Net-(D2-A)") (class "Default")
      (node (ref "D2") (pin "2") (pinfunction "A_2") (pintype "passive"))
      (node (ref "R19") (pin "2") (pinfunction "2_2") (pintype "passive"))
    )
    (net (code "67") (name "Net-(D3-A)") (class "Default")
      (node (ref "D3") (pin "2") (pinfunction "A_2") (pintype "passive"))
      (node (ref "R28") (pin "2") (pinfunction "2_2") (pintype "passive"))
    )
    (net (code "68") (name "Net-(D4-A)") (class "Default")
      (node (ref "D4") (pin "2") (pinfunction "A_2") (pintype "passive"))
      (node (ref "R33") (pin "2") (pinfunction "2_2") (pintype "passive"))
    )
    (net (code "69") (name "Net-(D5-A)") (class "Default")
      (node (ref "D5") (pin "2") (pinfunction "A_2") (pintype "passive"))
      (node (ref "R42") (pin "2") (pinfunction "2_2") (pintype "passive"))
    )
    (net (code "70") (name "Net-(IC1-OUT1F)") (class "Default")
      (node (ref "IC1") (pin "1") (pinfunction "OUT1F_1") (pintype "passive"))
      (node (ref "IC1") (pin "2") (pinfunction "OUT1S_2") (pintype "passive"))
      (node (ref "R1") (pin "2") (pinfunction "2_2") (pintype "passive"))
    )
    (net (code "71") (name "Net-(IC1-OUT2F)") (class "Default")
      (node (ref "IC1") (pin "6") (pinfunction "OUT2F_6") (pintype "passive"))
      (node (ref "IC1") (pin "7") (pinfunction "OUT2S_7") (pintype "passive"))
      (node (ref "R6") (pin "1") (pinfunction "1_1") (pintype "passive"))
    )
    (net (code "72") (name "Net-(IC2-AN1{slash}VREF-{slash}CN3{slash}RB1)") (class "Default")
      (node (ref "IC2") (pin "3") (pinfunction "AN1/VREF-/CN3/RB1_3") (pintype "passive"))
      (node (ref "R18") (pin "2") (pinfunction "2_2") (pintype "passive"))
    )
    (net (code "73") (name "Net-(IC2-AN12{slash}COFS{slash}RB12)") (class "Default")
      (node (ref "IC2") (pin "35") (pinfunction "AN12/COFS/RB12_35") (pintype "passive"))
      (node (ref "R19") (pin "1") (pinfunction "1_1") (pintype "passive"))
    )
    (net (code "74") (name "Net-(IC2-EMUC2{slash}OC1{slash}RD0)") (class "Default")
      (node (ref "IC2") (pin "34") (pinfunction "EMUC2/OC1/RD0_34") (pintype "passive"))
      (node (ref "R28") (pin "1") (pinfunction "1_1") (pintype "passive"))
    )
    (net (code "75") (name "Net-(IC3-DATA)") (class "Default")
      (node (ref "IC3") (pin "2") (pinfunction "DATA_2") (pintype "passive"))
      (node (ref "J2") (pin "12") (pinfunction "12_12") (pintype "passive"))
      (node (ref "R24") (pin "1") (pinfunction "1_1") (pintype "passive"))
    )
    (net (code "76") (name "Net-(IC4-S1)") (class "Default")
      (node (ref "IC4") (pin "19") (pinfunction "S1_19") (pintype "bidirectional"))
      (node (ref "R71") (pin "1") (pinfunction "1_1") (pintype "passive"))
    )
    (net (code "77") (name "Net-(IC4-S2)") (class "Default")
      (node (ref "IC4") (pin "20") (pinfunction "S2_20") (pintype "bidirectional"))
      (node (ref "R68") (pin "1") (pinfunction "1_1") (pintype "passive"))
    )
    (net (code "78") (name "Net-(IC4-S3)") (class "Default")
      (node (ref "IC4") (pin "21") (pinfunction "S3_21") (pintype "bidirectional"))
      (node (ref "R64") (pin "1") (pinfunction "1_1") (pintype "passive"))
    )
    (net (code "79") (name "Net-(IC4-S4)") (class "Default")
      (node (ref "IC4") (pin "22") (pinfunction "S4_22") (pintype "bidirectional"))
      (node (ref "R60") (pin "1") (pinfunction "1_1") (pintype "passive"))
    )
    (net (code "80") (name "Net-(IC4-S5)") (class "Default")
      (node (ref "IC4") (pin "23") (pinfunction "S5_23") (pintype "bidirectional"))
      (node (ref "R58") (pin "1") (pinfunction "1_1") (pintype "passive"))
    )
    (net (code "81") (name "Net-(IC4-S6)") (class "Default")
      (node (ref "IC4") (pin "24") (pinfunction "S6_24") (pintype "bidirectional"))
      (node (ref "R55") (pin "1") (pinfunction "1_1") (pintype "passive"))
    )
    (net (code "82") (name "Net-(IC4-S7)") (class "Default")
      (node (ref "IC4") (pin "25") (pinfunction "S7_25") (pintype "bidirectional"))
      (node (ref "R53") (pin "1") (pinfunction "1_1") (pintype "passive"))
    )
    (net (code "83") (name "Net-(IC4-S8)") (class "Default")
      (node (ref "IC4") (pin "26") (pinfunction "S8_26") (pintype "bidirectional"))
      (node (ref "R51") (pin "1") (pinfunction "1_1") (pintype "passive"))
    )
    (net (code "84") (name "Net-(IC4-S9)") (class "Default")
      (node (ref "IC4") (pin "11") (pinfunction "S9_11") (pintype "bidirectional"))
      (node (ref "R73") (pin "2") (pinfunction "2_2") (pintype "passive"))
    )
    (net (code "85") (name "Net-(IC4-S10)") (class "Default")
      (node (ref "IC4") (pin "10") (pinfunction "S10_10") (pintype "bidirectional"))
      (node (ref "R70") (pin "2") (pinfunction "2_2") (pintype "passive"))
    )
    (net (code "86") (name "Net-(IC4-S11)") (class "Default")
      (node (ref "IC4") (pin "9") (pinfunction "S11_9") (pintype "bidirectional"))
      (node (ref "R67") (pin "2") (pinfunction "2_2") (pintype "passive"))
    )
    (net (code "87") (name "Net-(IC4-S12)") (class "Default")
      (node (ref "IC4") (pin "8") (pinfunction "S12_8") (pintype "bidirectional"))
      (node (ref "R63") (pin "2") (pinfunction "2_2") (pintype "passive"))
    )
    (net (code "88") (name "Net-(IC4-S13)") (class "Default")
      (node (ref "IC4") (pin "7") (pinfunction "S13_7") (pintype "bidirectional"))
      (node (ref "R59") (pin "2") (pinfunction "2_2") (pintype "passive"))
    )
    (net (code "89") (name "Net-(IC4-S14)") (class "Default")
      (node (ref "IC4") (pin "6") (pinfunction "S14_6") (pintype "bidirectional"))
      (node (ref "R57") (pin "2") (pinfunction "2_2") (pintype "passive"))
    )
    (net (code "90") (name "Net-(IC4-S15)") (class "Default")
      (node (ref "IC4") (pin "5") (pinfunction "S15_5") (pintype "bidirectional"))
      (node (ref "R54") (pin "2") (pinfunction "2_2") (pintype "passive"))
    )
    (net (code "91") (name "Net-(IC4-S16)") (class "Default")
      (node (ref "IC4") (pin "4") (pinfunction "S16_4") (pintype "bidirectional"))
      (node (ref "R52") (pin "2") (pinfunction "2_2") (pintype "passive"))
    )
    (net (code "92") (name "Net-(IC5-VO)") (class "Default")
      (node (ref "IC5") (pin "6") (pinfunction "VO_6") (pintype "passive"))
      (node (ref "R61") (pin "1") (pinfunction "1_1") (pintype "passive"))
    )
    (net (code "93") (name "Net-(IC6-S1)") (class "Default")
      (node (ref "IC6") (pin "19") (pinfunction "S1_19") (pintype "bidirectional"))
      (node (ref "R105") (pin "1") (pinfunction "1_1") (pintype "passive"))
    )
    (net (code "94") (name "Net-(IC6-S2)") (class "Default")
      (node (ref "IC6") (pin "20") (pinfunction "S2_20") (pintype "bidirectional"))
      (node (ref "R102") (pin "1") (pinfunction "1_1") (pintype "passive"))
    )
    (net (code "95") (name "Net-(IC6-S3)") (class "Default")
      (node (ref "IC6") (pin "21") (pinfunction "S3_21") (pintype "bidirectional"))
      (node (ref "R98") (pin "1") (pinfunction "1_1") (pintype "passive"))
    )
    (net (code "96") (name "Net-(IC6-S4)") (class "Default")
      (node (ref "IC6") (pin "22") (pinfunction "S4_22") (pintype "bidirectional"))
      (node (ref "R94") (pin "1") (pinfunction "1_1") (pintype "passive"))
    )
    (net (code "97") (name "Net-(IC6-S5)") (class "Default")
      (node (ref "IC6") (pin "23") (pinfunction "S5_23") (pintype "bidirectional"))
      (node (ref "R92") (pin "1") (pinfunction "1_1") (pintype "passive"))
    )
    (net (code "98") (name "Net-(IC6-S6)") (class "Default")
      (node (ref "IC6") (pin "24") (pinfunction "S6_24") (pintype "bidirectional"))
      (node (ref "R89") (pin "1") (pinfunction "1_1") (pintype "passive"))
    )
    (net (code "99") (name "Net-(IC6-S7)") (class "Default")
      (node (ref "IC6") (pin "25") (pinfunction "S7_25") (pintype "bidirectional"))
      (node (ref "R87") (pin "1") (pinfunction "1_1") (pintype "passive"))
    )
    (net (code "100") (name "Net-(IC6-S8)") (class "Default")
      (node (ref "IC6") (pin "26") (pinfunction "S8_26") (pintype "bidirectional"))
      (node (ref "R85") (pin "1") (pinfunction "1_1") (pintype "passive"))
    )
    (net (code "101") (name "Net-(IC6-S9)") (class "Default")
      (node (ref "IC6") (pin "11") (pinfunction "S9_11") (pintype "bidirectional"))
      (node (ref "R107") (pin "2") (pinfunction "2_2") (pintype "passive"))
    )
    (net (code "102") (name "Net-(IC6-S10)") (class "Default")
      (node (ref "IC6") (pin "10") (pinfunction "S10_10") (pintype "bidirectional"))
      (node (ref "R104") (pin "2") (pinfunction "2_2") (pintype "passive"))
    )
    (net (code "103") (name "Net-(IC6-S11)") (class "Default")
      (node (ref "IC6") (pin "9") (pinfunction "S11_9") (pintype "bidirectional"))
      (node (ref "R101") (pin "2") (pinfunction "2_2") (pintype "passive"))
    )
    (net (code "104") (name "Net-(IC6-S12)") (class "Default")
      (node (ref "IC6") (pin "8") (pinfunction "S12_8") (pintype "bidirectional"))
      (node (ref "R97") (pin "2") (pinfunction "2_2") (pintype "passive"))
    )
    (net (code "105") (name "Net-(IC6-S13)") (class "Default")
      (node (ref "IC6") (pin "7") (pinfunction "S13_7") (pintype "bidirectional"))
      (node (ref "R93") (pin "2") (pinfunction "2_2") (pintype "passive"))
    )
    (net (code "106") (name "Net-(IC6-S14)") (class "Default")
      (node (ref "IC6") (pin "6") (pinfunction "S14_6") (pintype "bidirectional"))
      (node (ref "R91") (pin "2") (pinfunction "2_2") (pintype "passive"))
    )
    (net (code "107") (name "Net-(IC6-S15)") (class "Default")
      (node (ref "IC6") (pin "5") (pinfunction "S15_5") (pintype "bidirectional"))
      (node (ref "R88") (pin "2") (pinfunction "2_2") (pintype "passive"))
    )
    (net (code "108") (name "Net-(IC6-S16)") (class "Default")
      (node (ref "IC6") (pin "4") (pinfunction "S16_4") (pintype "bidirectional"))
      (node (ref "R86") (pin "2") (pinfunction "2_2") (pintype "passive"))
    )
    (net (code "109") (name "Net-(IC7-VO)") (class "Default")
      (node (ref "IC7") (pin "6") (pinfunction "VO_6") (pintype "passive"))
      (node (ref "R95") (pin "1") (pinfunction "1_1") (pintype "passive"))
    )
    (net (code "110") (name "Net-(IC8-S1)") (class "Default")
      (node (ref "IC8") (pin "19") (pinfunction "S1_19") (pintype "bidirectional"))
      (node (ref "R139") (pin "1") (pinfunction "1_1") (pintype "passive"))
    )
    (net (code "111") (name "Net-(IC8-S2)") (class "Default")
      (node (ref "IC8") (pin "20") (pinfunction "S2_20") (pintype "bidirectional"))
      (node (ref "R136") (pin "1") (pinfunction "1_1") (pintype "passive"))
    )
    (net (code "112") (name "Net-(IC8-S3)") (class "Default")
      (node (ref "IC8") (pin "21") (pinfunction "S3_21") (pintype "bidirectional"))
      (node (ref "R132") (pin "1") (pinfunction "1_1") (pintype "passive"))
    )
    (net (code "113") (name "Net-(IC8-S4)") (class "Default")
      (node (ref "IC8") (pin "22") (pinfunction "S4_22") (pintype "bidirectional"))
      (node (ref "R128") (pin "1") (pinfunction "1_1") (pintype "passive"))
    )
    (net (code "114") (name "Net-(IC8-S5)") (class "Default")
      (node (ref "IC8") (pin "23") (pinfunction "S5_23") (pintype "bidirectional"))
      (node (ref "R126") (pin "1") (pinfunction "1_1") (pintype "passive"))
    )
    (net (code "115") (name "Net-(IC8-S6)") (class "Default")
      (node (ref "IC8") (pin "24") (pinfunction "S6_24") (pintype "bidirectional"))
      (node (ref "R123") (pin "1") (pinfunction "1_1") (pintype "passive"))
    )
    (net (code "116") (name "Net-(IC8-S7)") (class "Default")
      (node (ref "IC8") (pin "25") (pinfunction "S7_25") (pintype "bidirectional"))
      (node (ref "R121") (pin "1") (pinfunction "1_1") (pintype "passive"))
    )
    (net (code "117") (name "Net-(IC8-S8)") (class "Default")
      (node (ref "IC8") (pin "26") (pinfunction "S8_26") (pintype "bidirectional"))
      (node (ref "R119") (pin "1") (pinfunction "1_1") (pintype "passive"))
    )
    (net (code "118") (name "Net-(IC8-S9)") (class "Default")
      (node (ref "IC8") (pin "11") (pinfunction "S9_11") (pintype "bidirectional"))
      (node (ref "R141") (pin "2") (pinfunction "2_2") (pintype "passive"))
    )
    (net (code "119") (name "Net-(IC8-S10)") (class "Default")
      (node (ref "IC8") (pin "10") (pinfunction "S10_10") (pintype "bidirectional"))
      (node (ref "R138") (pin "2") (pinfunction "2_2") (pintype "passive"))
    )
    (net (code "120") (name "Net-(IC8-S11)") (class "Default")
      (node (ref "IC8") (pin "9") (pinfunction "S11_9") (pintype "bidirectional"))
      (node (ref "R135") (pin "2") (pinfunction "2_2") (pintype "passive"))
    )
    (net (code "121") (name "Net-(IC8-S12)") (class "Default")
      (node (ref "IC8") (pin "8") (pinfunction "S12_8") (pintype "bidirectional"))
      (node (ref "R131") (pin "2") (pinfunction "2_2") (pintype "passive"))
    )
    (net (code "122") (name "Net-(IC8-S13)") (class "Default")
      (node (ref "IC8") (pin "7") (pinfunction "S13_7") (pintype "bidirectional"))
      (node (ref "R127") (pin "2") (pinfunction "2_2") (pintype "passive"))
    )
    (net (code "123") (name "Net-(IC8-S14)") (class "Default")
      (node (ref "IC8") (pin "6") (pinfunction "S14_6") (pintype "bidirectional"))
      (node (ref "R125") (pin "2") (pinfunction "2_2") (pintype "passive"))
    )
    (net (code "124") (name "Net-(IC8-S15)") (class "Default")
      (node (ref "IC8") (pin "5") (pinfunction "S15_5") (pintype "bidirectional"))
      (node (ref "R122") (pin "2") (pinfunction "2_2") (pintype "passive"))
    )
    (net (code "125") (name "Net-(IC8-S16)") (class "Default")
      (node (ref "IC8") (pin "4") (pinfunction "S16_4") (pintype "bidirectional"))
      (node (ref "R120") (pin "2") (pinfunction "2_2") (pintype "passive"))
    )
    (net (code "126") (name "Net-(IC9-VO)") (class "Default")
      (node (ref "IC9") (pin "6") (pinfunction "VO_6") (pintype "passive"))
      (node (ref "R129") (pin "1") (pinfunction "1_1") (pintype "passive"))
    )
    (net (code "127") (name "Net-(J2-Pad11)") (class "Default")
      (node (ref "J2") (pin "11") (pinfunction "11_11") (pintype "passive"))
      (node (ref "R27") (pin "2") (pinfunction "2_2") (pintype "passive"))
    )
    (net (code "128") (name "Net-(J2-Pad19)") (class "Default")
      (node (ref "J2") (pin "19") (pinfunction "19_19") (pintype "passive"))
      (node (ref "R29") (pin "2") (pinfunction "2_2") (pintype "passive"))
    )
    (net (code "129") (name "Net-(J2-Pad21)") (class "Default")
      (node (ref "J2") (pin "21") (pinfunction "21_21") (pintype "passive"))
      (node (ref "R30") (pin "2") (pinfunction "2_2") (pintype "passive"))
    )
    (net (code "130") (name "Net-(J2-Pad23)") (class "Default")
      (node (ref "J2") (pin "23") (pinfunction "23_23") (pintype "passive"))
      (node (ref "R31") (pin "2") (pinfunction "2_2") (pintype "passive"))
    )
    (net (code "131") (name "Net-(J2-Pad24)") (class "Default")
      (node (ref "J2") (pin "24") (pinfunction "24_24") (pintype "passive"))
      (node (ref "R32") (pin "1") (pinfunction "1_1") (pintype "passive"))
    )
    (net (code "132") (name "Net-(J2-Pad32)") (class "Default")
      (node (ref "J2") (pin "32") (pinfunction "32_32") (pintype "passive"))
      (node (ref "R33") (pin "1") (pinfunction "1_1") (pintype "passive"))
    )
    (net (code "133") (name "Net-(J2-Pad36)") (class "Default")
      (node (ref "J2") (pin "36") (pinfunction "36_36") (pintype "passive"))
      (node (ref "R42") (pin "1") (pinfunction "1_1") (pintype "passive"))
    )
    (net (code "134") (name "Net-(J2-Pad38)") (class "Default")
      (node (ref "J2") (pin "38") (pinfunction "38_38") (pintype "passive"))
      (node (ref "R45") (pin "1") (pinfunction "1_1") (pintype "passive"))
    )
    (net (code "135") (name "Net-(J2-Pad40)") (class "Default")
      (node (ref "J2") (pin "40") (pinfunction "40_40") (pintype "passive"))
      (node (ref "R46") (pin "1") (pinfunction "1_1") (pintype "passive"))
    )
    (net (code "136") (name "Net-(U1-VBAT)") (class "Default")
      (node (ref "BT1") (pin "1") (pinfunction "1_1") (pintype "passive"))
      (node (ref "U1") (pin "14") (pinfunction "VBAT_14") (pintype "passive"))
    )
    (net (code "137") (name "Net-(U2A-1IN+)") (class "Default")
      (node (ref "C41") (pin "1") (pinfunction "1_1") (pintype "passive"))
      (node (ref "R66") (pin "2") (pinfunction "2_2") (pintype "passive"))
      (node (ref "U2") (pin "3") (pinfunction "1IN+_3") (pintype "input"))
    )
    (net (code "138") (name "Net-(U2A-1IN-)") (class "Default")
      (node (ref "C28") (pin "2") (pinfunction "2_2") (pintype "passive"))
      (node (ref "R69") (pin "1") (pinfunction "1_1") (pintype "passive"))
      (node (ref "U2") (pin "1") (pinfunction "1OUT_1") (pintype "output"))
      (node (ref "U2") (pin "2") (pinfunction "1IN-_2") (pintype "input"))
    )
    (net (code "139") (name "Net-(U2B-2IN+)") (class "Default")
      (node (ref "C40") (pin "1") (pinfunction "1_1") (pintype "passive"))
      (node (ref "R62") (pin "2") (pinfunction "2_2") (pintype "passive"))
      (node (ref "U2") (pin "5") (pinfunction "2IN+_5") (pintype "input"))
    )
    (net (code "140") (name "Net-(U2B-2IN-)") (class "Default")
      (node (ref "C27") (pin "2") (pinfunction "2_2") (pintype "passive"))
      (node (ref "R65") (pin "1") (pinfunction "1_1") (pintype "passive"))
      (node (ref "U2") (pin "6") (pinfunction "2IN-_6") (pintype "input"))
      (node (ref "U2") (pin "7") (pinfunction "2OUT_7") (pintype "output"))
    )
    (net (code "141") (name "Net-(U2C-3IN+)") (class "Default")
      (node (ref "R79") (pin "2") (pinfunction "2_2") (pintype "passive"))
      (node (ref "U2") (pin "10") (pinfunction "3IN+_10") (pintype "input"))
      (node (ref "U2") (pin "14") (pinfunction "4OUT_14") (pintype "output"))
    )
    (net (code "142") (name "Net-(U2D-4IN+)") (class "Default")
      (node (ref "R69") (pin "2") (pinfunction "2_2") (pintype "passive"))
      (node (ref "R74") (pin "2") (pinfunction "2_2") (pintype "passive"))
      (node (ref "U2") (pin "12") (pinfunction "4IN+_12") (pintype "input"))
    )
    (net (code "143") (name "Net-(U2D-4IN-)") (class "Default")
      (node (ref "R79") (pin "1") (pinfunction "1_1") (pintype "passive"))
      (node (ref "R80") (pin "2") (pinfunction "2_2") (pintype "passive"))
      (node (ref "U2") (pin "13") (pinfunction "4IN-_13") (pintype "input"))
    )
    (net (code "144") (name "Net-(U3A-1IN+)") (class "Default")
      (node (ref "C62") (pin "1") (pinfunction "1_1") (pintype "passive"))
      (node (ref "R100") (pin "2") (pinfunction "2_2") (pintype "passive"))
      (node (ref "U3") (pin "3") (pinfunction "1IN+_3") (pintype "input"))
    )
    (net (code "145") (name "Net-(U3A-1IN-)") (class "Default")
      (node (ref "C49") (pin "2") (pinfunction "2_2") (pintype "passive"))
      (node (ref "R103") (pin "1") (pinfunction "1_1") (pintype "passive"))
      (node (ref "U3") (pin "1") (pinfunction "1OUT_1") (pintype "output"))
      (node (ref "U3") (pin "2") (pinfunction "1IN-_2") (pintype "input"))
    )
    (net (code "146") (name "Net-(U3B-2IN+)") (class "Default")
      (node (ref "C61") (pin "1") (pinfunction "1_1") (pintype "passive"))
      (node (ref "R96") (pin "2") (pinfunction "2_2") (pintype "passive"))
      (node (ref "U3") (pin "5") (pinfunction "2IN+_5") (pintype "input"))
    )
    (net (code "147") (name "Net-(U3B-2IN-)") (class "Default")
      (node (ref "C48") (pin "2") (pinfunction "2_2") (pintype "passive"))
      (node (ref "R99") (pin "1") (pinfunction "1_1") (pintype "passive"))
      (node (ref "U3") (pin "6") (pinfunction "2IN-_6") (pintype "input"))
      (node (ref "U3") (pin "7") (pinfunction "2OUT_7") (pintype "output"))
    )
    (net (code "148") (name "Net-(U3C-3IN+)") (class "Default")
      (node (ref "R113") (pin "2") (pinfunction "2_2") (pintype "passive"))
      (node (ref "U3") (pin "10") (pinfunction "3IN+_10") (pintype "input"))
      (node (ref "U3") (pin "14") (pinfunction "4OUT_14") (pintype "output"))
    )
    (net (code "149") (name "Net-(U3D-4IN+)") (class "Default")
      (node (ref "R103") (pin "2") (pinfunction "2_2") (pintype "passive"))
      (node (ref "R108") (pin "2") (pinfunction "2_2") (pintype "passive"))
      (node (ref "U3") (pin "12") (pinfunction "4IN+_12") (pintype "input"))
    )
    (net (code "150") (name "Net-(U3D-4IN-)") (class "Default")
      (node (ref "R113") (pin "1") (pinfunction "1_1") (pintype "passive"))
      (node (ref "R114") (pin "2") (pinfunction "2_2") (pintype "passive"))
      (node (ref "U3") (pin "13") (pinfunction "4IN-_13") (pintype "input"))
    )
    (net (code "151") (name "Net-(U4A-1IN+)") (class "Default")
      (node (ref "C83") (pin "1") (pinfunction "1_1") (pintype "passive"))
      (node (ref "R134") (pin "2") (pinfunction "2_2") (pintype "passive"))
      (node (ref "U4") (pin "3") (pinfunction "1IN+_3") (pintype "input"))
    )
    (net (code "152") (name "Net-(U4A-1IN-)") (class "Default")
      (node (ref "C70") (pin "2") (pinfunction "2_2") (pintype "passive"))
      (node (ref "R137") (pin "1") (pinfunction "1_1") (pintype "passive"))
      (node (ref "U4") (pin "1") (pinfunction "1OUT_1") (pintype "output"))
      (node (ref "U4") (pin "2") (pinfunction "1IN-_2") (pintype "input"))
    )
    (net (code "153") (name "Net-(U4B-2IN+)") (class "Default")
      (node (ref "C82") (pin "1") (pinfunction "1_1") (pintype "passive"))
      (node (ref "R130") (pin "2") (pinfunction "2_2") (pintype "passive"))
      (node (ref "U4") (pin "5") (pinfunction "2IN+_5") (pintype "input"))
    )
    (net (code "154") (name "Net-(U4B-2IN-)") (class "Default")
      (node (ref "C69") (pin "2") (pinfunction "2_2") (pintype "passive"))
      (node (ref "R133") (pin "1") (pinfunction "1_1") (pintype "passive"))
      (node (ref "U4") (pin "6") (pinfunction "2IN-_6") (pintype "input"))
      (node (ref "U4") (pin "7") (pinfunction "2OUT_7") (pintype "output"))
    )
    (net (code "155") (name "Net-(U4C-3IN+)") (class "Default")
      (node (ref "R147") (pin "2") (pinfunction "2_2") (pintype "passive"))
      (node (ref "U4") (pin "10") (pinfunction "3IN+_10") (pintype "input"))
      (node (ref "U4") (pin "14") (pinfunction "4OUT_14") (pintype "output"))
    )
    (net (code "156") (name "Net-(U4D-4IN+)") (class "Default")
      (node (ref "R137") (pin "2") (pinfunction "2_2") (pintype "passive"))
      (node (ref "R142") (pin "2") (pinfunction "2_2") (pintype "passive"))
      (node (ref "U4") (pin "12") (pinfunction "4IN+_12") (pintype "input"))
    )
    (net (code "157") (name "Net-(U4D-4IN-)") (class "Default")
      (node (ref "R147") (pin "1") (pinfunction "1_1") (pintype "passive"))
      (node (ref "R148") (pin "2") (pinfunction "2_2") (pintype "passive"))
      (node (ref "U4") (pin "13") (pinfunction "4IN-_13") (pintype "input"))
    )
    (net (code "158") (name "OSC1") (class "Default")
      (node (ref "C25") (pin "2") (pinfunction "2_2") (pintype "passive"))
      (node (ref "IC2") (pin "13") (pinfunction "OSC1/CLKI_13") (pintype "passive"))
      (node (ref "Y1") (pin "1") (pinfunction "CRYSTAL_1_1") (pintype "passive"))
    )
    (net (code "159") (name "OSC2") (class "Default")
      (node (ref "C26") (pin "2") (pinfunction "2_2") (pintype "passive"))
      (node (ref "IC2") (pin "14") (pinfunction "OSC2/CLKO/RC15_14") (pintype "passive"))
      (node (ref "Y1") (pin "2") (pinfunction "CRYSTAL_2_2") (pintype "passive"))
    )
    (net (code "160") (name "PGC_A3_5V") (class "Default")
      (node (ref "IC2") (pin "8") (pinfunction "PGC/EMUC/AN6/OCFA/RB6_8") (pintype "passive"))
      (node (ref "P5") (pin "5") (pinfunction "5_5") (pintype "passive"))
      (node (ref "Q12") (pin "3") (pinfunction "D_3") (pintype "passive"))
      (node (ref "R41") (pin "2") (pinfunction "2_2") (pintype "passive"))
    )
    (net (code "161") (name "PGD") (class "Default")
      (node (ref "IC2") (pin "9") (pinfunction "PGD/EMUD/AN7/RB7_9") (pintype "passive"))
      (node (ref "P5") (pin "4") (pinfunction "4_4") (pintype "passive"))
    )
    (net (code "162") (name "PIN_EXTRA_3.3V") (class "Default")
      (node (ref "Q3") (pin "2") (pinfunction "S_2") (pintype "passive"))
      (node (ref "R11") (pin "2") (pinfunction "2_2") (pintype "passive"))
      (node (ref "R46") (pin "2") (pinfunction "2_2") (pintype "passive"))
    )
    (net (code "163") (name "PIN_EXTRA_5V") (class "Default")
      (node (ref "IC2") (pin "33") (pinfunction "EMUD2/OC2/RD1_33") (pintype "passive"))
      (node (ref "Q3") (pin "3") (pinfunction "D_3") (pintype "passive"))
      (node (ref "R12") (pin "2") (pinfunction "2_2") (pintype "passive"))
    )
    (net (code "164") (name "PPS_DS3231") (class "Default")
      (node (ref "IC2") (pin "18") (pinfunction "IC2/INT2/RD9_18") (pintype "passive"))
      (node (ref "R7") (pin "1") (pinfunction "1_1") (pintype "passive"))
      (node (ref "U1") (pin "3") (pinfunction "~{NT}/SQW_3") (pintype "passive"))
    )
    (net (code "165") (name "PPS_GPS_3.3V") (class "Default")
      (node (ref "GPS1") (pin "0") (pinfunction "1PPS_0") (pintype "output"))
      (node (ref "Q2") (pin "2") (pinfunction "S_2") (pintype "passive"))
      (node (ref "R8") (pin "2") (pinfunction "2_2") (pintype "passive"))
    )
    (net (code "166") (name "PPS_GPS_5V") (class "Default")
      (node (ref "IC2") (pin "17") (pinfunction "INT0/RA11_17") (pintype "passive"))
      (node (ref "Q2") (pin "3") (pinfunction "D_3") (pintype "passive"))
      (node (ref "R9") (pin "2") (pinfunction "2_2") (pintype "passive"))
    )
    (net (code "167") (name "RES_1_1") (class "Default")
      (node (ref "IC4") (pin "28") (pinfunction "D_28") (pintype "bidirectional"))
      (node (ref "IC5") (pin "1") (pinfunction "RG_1_1") (pintype "passive"))
    )
    (net (code "168") (name "RES_1_2") (class "Default")
      (node (ref "IC5") (pin "8") (pinfunction "RG_2_8") (pintype "passive"))
      (node (ref "R51") (pin "2") (pinfunction "2_2") (pintype "passive"))
      (node (ref "R52") (pin "1") (pinfunction "1_1") (pintype "passive"))
      (node (ref "R53") (pin "2") (pinfunction "2_2") (pintype "passive"))
      (node (ref "R54") (pin "1") (pinfunction "1_1") (pintype "passive"))
      (node (ref "R55") (pin "2") (pinfunction "2_2") (pintype "passive"))
      (node (ref "R57") (pin "1") (pinfunction "1_1") (pintype "passive"))
      (node (ref "R58") (pin "2") (pinfunction "2_2") (pintype "passive"))
      (node (ref "R59") (pin "1") (pinfunction "1_1") (pintype "passive"))
      (node (ref "R60") (pin "2") (pinfunction "2_2") (pintype "passive"))
      (node (ref "R63") (pin "1") (pinfunction "1_1") (pintype "passive"))
      (node (ref "R64") (pin "2") (pinfunction "2_2") (pintype "passive"))
      (node (ref "R67") (pin "1") (pinfunction "1_1") (pintype "passive"))
      (node (ref "R68") (pin "2") (pinfunction "2_2") (pintype "passive"))
      (node (ref "R70") (pin "1") (pinfunction "1_1") (pintype "passive"))
      (node (ref "R71") (pin "2") (pinfunction "2_2") (pintype "passive"))
      (node (ref "R73") (pin "1") (pinfunction "1_1") (pintype "passive"))
    )
    (net (code "169") (name "RES_2_1") (class "Default")
      (node (ref "IC6") (pin "28") (pinfunction "D_28") (pintype "bidirectional"))
      (node (ref "IC7") (pin "1") (pinfunction "RG_1_1") (pintype "passive"))
    )
    (net (code "170") (name "RES_2_2") (class "Default")
      (node (ref "IC7") (pin "8") (pinfunction "RG_2_8") (pintype "passive"))
      (node (ref "R101") (pin "1") (pinfunction "1_1") (pintype "passive"))
      (node (ref "R102") (pin "2") (pinfunction "2_2") (pintype "passive"))
      (node (ref "R104") (pin "1") (pinfunction "1_1") (pintype "passive"))
      (node (ref "R105") (pin "2") (pinfunction "2_2") (pintype "passive"))
      (node (ref "R107") (pin "1") (pinfunction "1_1") (pintype "passive"))
      (node (ref "R85") (pin "2") (pinfunction "2_2") (pintype "passive"))
      (node (ref "R86") (pin "1") (pinfunction "1_1") (pintype "passive"))
      (node (ref "R87") (pin "2") (pinfunction "2_2") (pintype "passive"))
      (node (ref "R88") (pin "1") (pinfunction "1_1") (pintype "passive"))
      (node (ref "R89") (pin "2") (pinfunction "2_2") (pintype "passive"))
      (node (ref "R91") (pin "1") (pinfunction "1_1") (pintype "passive"))
      (node (ref "R92") (pin "2") (pinfunction "2_2") (pintype "passive"))
      (node (ref "R93") (pin "1") (pinfunction "1_1") (pintype "passive"))
      (node (ref "R94") (pin "2") (pinfunction "2_2") (pintype "passive"))
      (node (ref "R97") (pin "1") (pinfunction "1_1") (pintype "passive"))
      (node (ref "R98") (pin "2") (pinfunction "2_2") (pintype "passive"))
    )
    (net (code "171") (name "RES_3_1") (class "Default")
      (node (ref "IC8") (pin "28") (pinfunction "D_28") (pintype "bidirectional"))
      (node (ref "IC9") (pin "1") (pinfunction "RG_1_1") (pintype "passive"))
    )
    (net (code "172") (name "RES_3_2") (class "Default")
      (node (ref "IC9") (pin "8") (pinfunction "RG_2_8") (pintype "passive"))
      (node (ref "R119") (pin "2") (pinfunction "2_2") (pintype "passive"))
      (node (ref "R120") (pin "1") (pinfunction "1_1") (pintype "passive"))
      (node (ref "R121") (pin "2") (pinfunction "2_2") (pintype "passive"))
      (node (ref "R122") (pin "1") (pinfunction "1_1") (pintype "passive"))
      (node (ref "R123") (pin "2") (pinfunction "2_2") (pintype "passive"))
      (node (ref "R125") (pin "1") (pinfunction "1_1") (pintype "passive"))
      (node (ref "R126") (pin "2") (pinfunction "2_2") (pintype "passive"))
      (node (ref "R127") (pin "1") (pinfunction "1_1") (pintype "passive"))
      (node (ref "R128") (pin "2") (pinfunction "2_2") (pintype "passive"))
      (node (ref "R131") (pin "1") (pinfunction "1_1") (pintype "passive"))
      (node (ref "R132") (pin "2") (pinfunction "2_2") (pintype "passive"))
      (node (ref "R135") (pin "1") (pinfunction "1_1") (pintype "passive"))
      (node (ref "R136") (pin "2") (pinfunction "2_2") (pintype "passive"))
      (node (ref "R138") (pin "1") (pinfunction "1_1") (pintype "passive"))
      (node (ref "R139") (pin "2") (pinfunction "2_2") (pintype "passive"))
      (node (ref "R141") (pin "1") (pinfunction "1_1") (pintype "passive"))
    )
    (net (code "173") (name "RST_DS3231") (class "Default")
      (node (ref "IC2") (pin "10") (pinfunction "AN8/RB8_10") (pintype "passive"))
      (node (ref "U1") (pin "4") (pinfunction "~{RST}_4") (pintype "passive"))
    )
    (net (code "174") (name "RST_DSPIC_3.3V") (class "Default")
      (node (ref "Q8") (pin "2") (pinfunction "S_2") (pintype "passive"))
      (node (ref "R25") (pin "2") (pinfunction "2_2") (pintype "passive"))
      (node (ref "R45") (pin "2") (pinfunction "2_2") (pintype "passive"))
    )
    (net (code "175") (name "RX_GPS") (class "Default")
      (node (ref "GPS1") (pin "3") (pinfunction "RXD_3") (pintype "input"))
      (node (ref "IC2") (pin "15") (pinfunction "EMUD1/SOSCI/T2CK/U1ATX/CN1/RC13_15") (pintype "passive"))
    )
    (net (code "176") (name "SCK_RPI_3.3V") (class "Default")
      (node (ref "Q9") (pin "2") (pinfunction "S_2") (pintype "passive"))
      (node (ref "R31") (pin "1") (pinfunction "1_1") (pintype "passive"))
      (node (ref "R34") (pin "2") (pinfunction "2_2") (pintype "passive"))
    )
    (net (code "177") (name "SCK_RPI_5V") (class "Default")
      (node (ref "IC2") (pin "24") (pinfunction "EMUC3/SCK1/RF6_24") (pintype "passive"))
      (node (ref "Q9") (pin "3") (pinfunction "D_3") (pintype "passive"))
      (node (ref "R35") (pin "2") (pinfunction "2_2") (pintype "passive"))
    )
    (net (code "178") (name "SCL_DS3231") (class "Default")
      (node (ref "IC2") (pin "22") (pinfunction "OC3/RD2_22") (pintype "passive"))
      (node (ref "R2") (pin "1") (pinfunction "1_1") (pintype "passive"))
      (node (ref "U1") (pin "16") (pinfunction "SCL_16") (pintype "passive"))
    )
    (net (code "179") (name "SDA_DS3231") (class "Default")
      (node (ref "IC2") (pin "23") (pinfunction "IC1/INT1/RD8_23") (pintype "passive"))
      (node (ref "R3") (pin "1") (pinfunction "1_1") (pintype "passive"))
      (node (ref "U1") (pin "15") (pinfunction "SDA_15") (pintype "passive"))
    )
    (net (code "180") (name "SIGNAL1") (class "Default")
      (node (ref "IC2") (pin "36") (pinfunction "AN11/CSDO/RB11_36") (pintype "passive"))
      (node (ref "U2") (pin "8") (pinfunction "3OUT_8") (pintype "output"))
      (node (ref "U2") (pin "9") (pinfunction "3IN-_9") (pintype "input"))
    )
    (net (code "181") (name "SIGNAL2") (class "Default")
      (node (ref "IC2") (pin "37") (pinfunction "AN10/CSDI/RB10_37") (pintype "passive"))
      (node (ref "U3") (pin "8") (pinfunction "3OUT_8") (pintype "output"))
      (node (ref "U3") (pin "9") (pinfunction "3IN-_9") (pintype "input"))
    )
    (net (code "182") (name "SIGNAL3") (class "Default")
      (node (ref "IC2") (pin "38") (pinfunction "AN9/CSCK/RB9_38") (pintype "passive"))
      (node (ref "U4") (pin "8") (pinfunction "3OUT_8") (pintype "output"))
      (node (ref "U4") (pin "9") (pinfunction "3IN-_9") (pintype "input"))
    )
    (net (code "183") (name "TX_GPS_3.3V") (class "Default")
      (node (ref "GPS1") (pin "4") (pinfunction "TXD_4") (pintype "output"))
      (node (ref "Q1") (pin "2") (pinfunction "S_2") (pintype "passive"))
      (node (ref "R4") (pin "2") (pinfunction "2_2") (pintype "passive"))
    )
    (net (code "184") (name "TX_GPS_5V") (class "Default")
      (node (ref "IC2") (pin "16") (pinfunction "EMUC1/SOSCO/T1CK/U1ARX/CN0/RC14_16") (pintype "passive"))
      (node (ref "Q1") (pin "3") (pinfunction "D_3") (pintype "passive"))
      (node (ref "R5") (pin "2") (pinfunction "2_2") (pintype "passive"))
    )
    (net (code "185") (name "VREF_+2.5V") (class "Default")
      (node (ref "C10") (pin "1") (pinfunction "1_1") (pintype "passive"))
      (node (ref "C11") (pin "1") (pinfunction "1_1") (pintype "passive"))
      (node (ref "C9") (pin "1") (pinfunction "1_1") (pintype "passive"))
      (node (ref "R108") (pin "1") (pinfunction "1_1") (pintype "passive"))
      (node (ref "R142") (pin "1") (pinfunction "1_1") (pintype "passive"))
      (node (ref "R6") (pin "2") (pinfunction "2_2") (pintype "passive"))
      (node (ref "R74") (pin "1") (pinfunction "1_1") (pintype "passive"))
    )
    (net (code "186") (name "VREF_+5V") (class "Default")
      (node (ref "C4") (pin "1") (pinfunction "1_1") (pintype "passive"))
      (node (ref "C5") (pin "1") (pinfunction "1_1") (pintype "passive"))
      (node (ref "C6") (pin "1") (pinfunction "1_1") (pintype "passive"))
      (node (ref "IC2") (pin "2") (pinfunction "AN0/VREF+/CN2/RB0_2") (pintype "passive"))
      (node (ref "R1") (pin "1") (pinfunction "1_1") (pintype "passive"))
    )
    (net (code "187") (name "unconnected-(GPS1-3.3V-Pad8)") (class "Default")
      (node (ref "GPS1") (pin "8") (pinfunction "3.3V_8") (pintype "output"))
    )
    (net (code "188") (name "unconnected-(GPS1-FIX-Pad5)") (class "Default")
      (node (ref "GPS1") (pin "5") (pinfunction "FIX_5") (pintype "output"))
    )
    (net (code "189") (name "unconnected-(GPS1-VBAT-Pad6)") (class "Default")
      (node (ref "GPS1") (pin "6") (pinfunction "VBAT_6") (pintype "input"))
    )
    (net (code "190") (name "unconnected-(IC2-C1RX{slash}RF0-Pad30)") (class "Default")
      (node (ref "IC2") (pin "30") (pinfunction "C1RX/RF0_30") (pintype "passive"))
    )
    (net (code "191") (name "unconnected-(IC2-U2RX{slash}CN17{slash}RF4-Pad28)") (class "Default")
      (node (ref "IC2") (pin "28") (pinfunction "U2RX/CN17/RF4_28") (pintype "passive"))
    )
    (net (code "192") (name "unconnected-(IC2-U2TX{slash}CN18{slash}RF5-Pad27)") (class "Default")
      (node (ref "IC2") (pin "27") (pinfunction "U2TX/CN18/RF5_27") (pintype "passive"))
    )
    (net (code "193") (name "unconnected-(IC3-NULL-Pad3)") (class "Default")
      (node (ref "IC3") (pin "3") (pinfunction "NULL_3") (pintype "passive"))
    )
    (net (code "194") (name "unconnected-(IC4-NC_1-Pad2)") (class "Default")
      (node (ref "IC4") (pin "2") (pinfunction "NC_1_2") (pintype "passive"))
    )
    (net (code "195") (name "unconnected-(IC4-NC_2-Pad3)") (class "Default")
      (node (ref "IC4") (pin "3") (pinfunction "NC_2_3") (pintype "passive"))
    )
    (net (code "196") (name "unconnected-(IC4-NC_3-Pad13)") (class "Default")
      (node (ref "IC4") (pin "13") (pinfunction "NC_3_13") (pintype "passive"))
    )
    (net (code "197") (name "unconnected-(IC6-NC_1-Pad2)") (class "Default")
      (node (ref "IC6") (pin "2") (pinfunction "NC_1_2") (pintype "passive"))
    )
    (net (code "198") (name "unconnected-(IC6-NC_2-Pad3)") (class "Default")
      (node (ref "IC6") (pin "3") (pinfunction "NC_2_3") (pintype "passive"))
    )
    (net (code "199") (name "unconnected-(IC6-NC_3-Pad13)") (class "Default")
      (node (ref "IC6") (pin "13") (pinfunction "NC_3_13") (pintype "passive"))
    )
    (net (code "200") (name "unconnected-(IC8-NC_1-Pad2)") (class "Default")
      (node (ref "IC8") (pin "2") (pinfunction "NC_1_2") (pintype "passive"))
    )
    (net (code "201") (name "unconnected-(IC8-NC_2-Pad3)") (class "Default")
      (node (ref "IC8") (pin "3") (pinfunction "NC_2_3") (pintype "passive"))
    )
    (net (code "202") (name "unconnected-(IC8-NC_3-Pad13)") (class "Default")
      (node (ref "IC8") (pin "13") (pinfunction "NC_3_13") (pintype "passive"))
    )
    (net (code "203") (name "unconnected-(J1-Pad1)") (class "Default")
      (node (ref "J1") (pin "1") (pinfunction "1_1") (pintype "passive"))
    )
    (net (code "204") (name "unconnected-(J1-Pad4)") (class "Default")
      (node (ref "J1") (pin "4") (pinfunction "4_4") (pintype "passive"))
    )
    (net (code "205") (name "unconnected-(J1-Pad7)") (class "Default")
      (node (ref "J1") (pin "7") (pinfunction "7_7") (pintype "passive"))
    )
    (net (code "206") (name "unconnected-(J1-Pad10)") (class "Default")
      (node (ref "J1") (pin "10") (pinfunction "10_10") (pintype "passive"))
    )
    (net (code "207") (name "unconnected-(J1-Pad11)") (class "Default")
      (node (ref "J1") (pin "11") (pinfunction "11_11") (pintype "passive"))
    )
    (net (code "208") (name "unconnected-(J1-Pad12)") (class "Default")
      (node (ref "J1") (pin "12") (pinfunction "12_12") (pintype "passive"))
    )
    (net (code "209") (name "unconnected-(J1-Pad17)") (class "Default")
      (node (ref "J1") (pin "17") (pinfunction "17_17") (pintype "passive"))
    )
    (net (code "210") (name "unconnected-(J1-Pad18)") (class "Default")
      (node (ref "J1") (pin "18") (pinfunction "18_18") (pintype "passive"))
    )
    (net (code "211") (name "unconnected-(J1-Pad19)") (class "Default")
      (node (ref "J1") (pin "19") (pinfunction "19_19") (pintype "passive"))
    )
    (net (code "212") (name "unconnected-(J1-Pad20)") (class "Default")
      (node (ref "J1") (pin "20") (pinfunction "20_20") (pintype "passive"))
    )
    (net (code "213") (name "unconnected-(J2-Pad3)") (class "Default")
      (node (ref "J2") (pin "3") (pinfunction "3_3") (pintype "passive"))
    )
    (net (code "214") (name "unconnected-(J2-Pad5)") (class "Default")
      (node (ref "J2") (pin "5") (pinfunction "5_5") (pintype "passive"))
    )
    (net (code "215") (name "unconnected-(J2-Pad7)") (class "Default")
      (node (ref "J2") (pin "7") (pinfunction "7_7") (pintype "passive"))
    )
    (net (code "216") (name "unconnected-(J2-Pad8)") (class "Default")
      (node (ref "J2") (pin "8") (pinfunction "8_8") (pintype "passive"))
    )
    (net (code "217") (name "unconnected-(J2-Pad10)") (class "Default")
      (node (ref "J2") (pin "10") (pinfunction "10_10") (pintype "passive"))
    )
    (net (code "218") (name "unconnected-(J2-Pad13)") (class "Default")
      (node (ref "J2") (pin "13") (pinfunction "13_13") (pintype "passive"))
    )
    (net (code "219") (name "unconnected-(J2-Pad15)") (class "Default")
      (node (ref "J2") (pin "15") (pinfunction "15_15") (pintype "passive"))
    )
    (net (code "220") (name "unconnected-(J2-Pad16)") (class "Default")
      (node (ref "J2") (pin "16") (pinfunction "16_16") (pintype "passive"))
    )
    (net (code "221") (name "unconnected-(J2-Pad18)") (class "Default")
      (node (ref "J2") (pin "18") (pinfunction "18_18") (pintype "passive"))
    )
    (net (code "222") (name "unconnected-(J2-Pad22)") (class "Default")
      (node (ref "J2") (pin "22") (pinfunction "22_22") (pintype "passive"))
    )
    (net (code "223") (name "unconnected-(J2-Pad26)") (class "Default")
      (node (ref "J2") (pin "26") (pinfunction "26_26") (pintype "passive"))
    )
    (net (code "224") (name "unconnected-(J2-Pad27)") (class "Default")
      (node (ref "J2") (pin "27") (pinfunction "27_27") (pintype "passive"))
    )
    (net (code "225") (name "unconnected-(J2-Pad28)") (class "Default")
      (node (ref "J2") (pin "28") (pinfunction "28_28") (pintype "passive"))
    )
    (net (code "226") (name "unconnected-(J2-Pad29)") (class "Default")
      (node (ref "J2") (pin "29") (pinfunction "29_29") (pintype "passive"))
    )
    (net (code "227") (name "unconnected-(J2-Pad31)") (class "Default")
      (node (ref "J2") (pin "31") (pinfunction "31_31") (pintype "passive"))
    )
    (net (code "228") (name "unconnected-(J2-Pad33)") (class "Default")
      (node (ref "J2") (pin "33") (pinfunction "33_33") (pintype "passive"))
    )
    (net (code "229") (name "unconnected-(J2-Pad35)") (class "Default")
      (node (ref "J2") (pin "35") (pinfunction "35_35") (pintype "passive"))
    )
    (net (code "230") (name "unconnected-(J2-Pad37)") (class "Default")
      (node (ref "J2") (pin "37") (pinfunction "37_37") (pintype "passive"))
    )
    (net (code "231") (name "unconnected-(P5-Pad6)") (class "Default")
      (node (ref "P5") (pin "6") (pinfunction "6_6") (pintype "passive"))
    )
    (net (code "232") (name "unconnected-(U1-32KHZ-Pad1)") (class "Default")
      (node (ref "U1") (pin "1") (pinfunction "32KHZ_1") (pintype "passive"))
    )
  )
)
